# Avalon2.net
KiCad netlist of a schematic drawn in Altium Designer
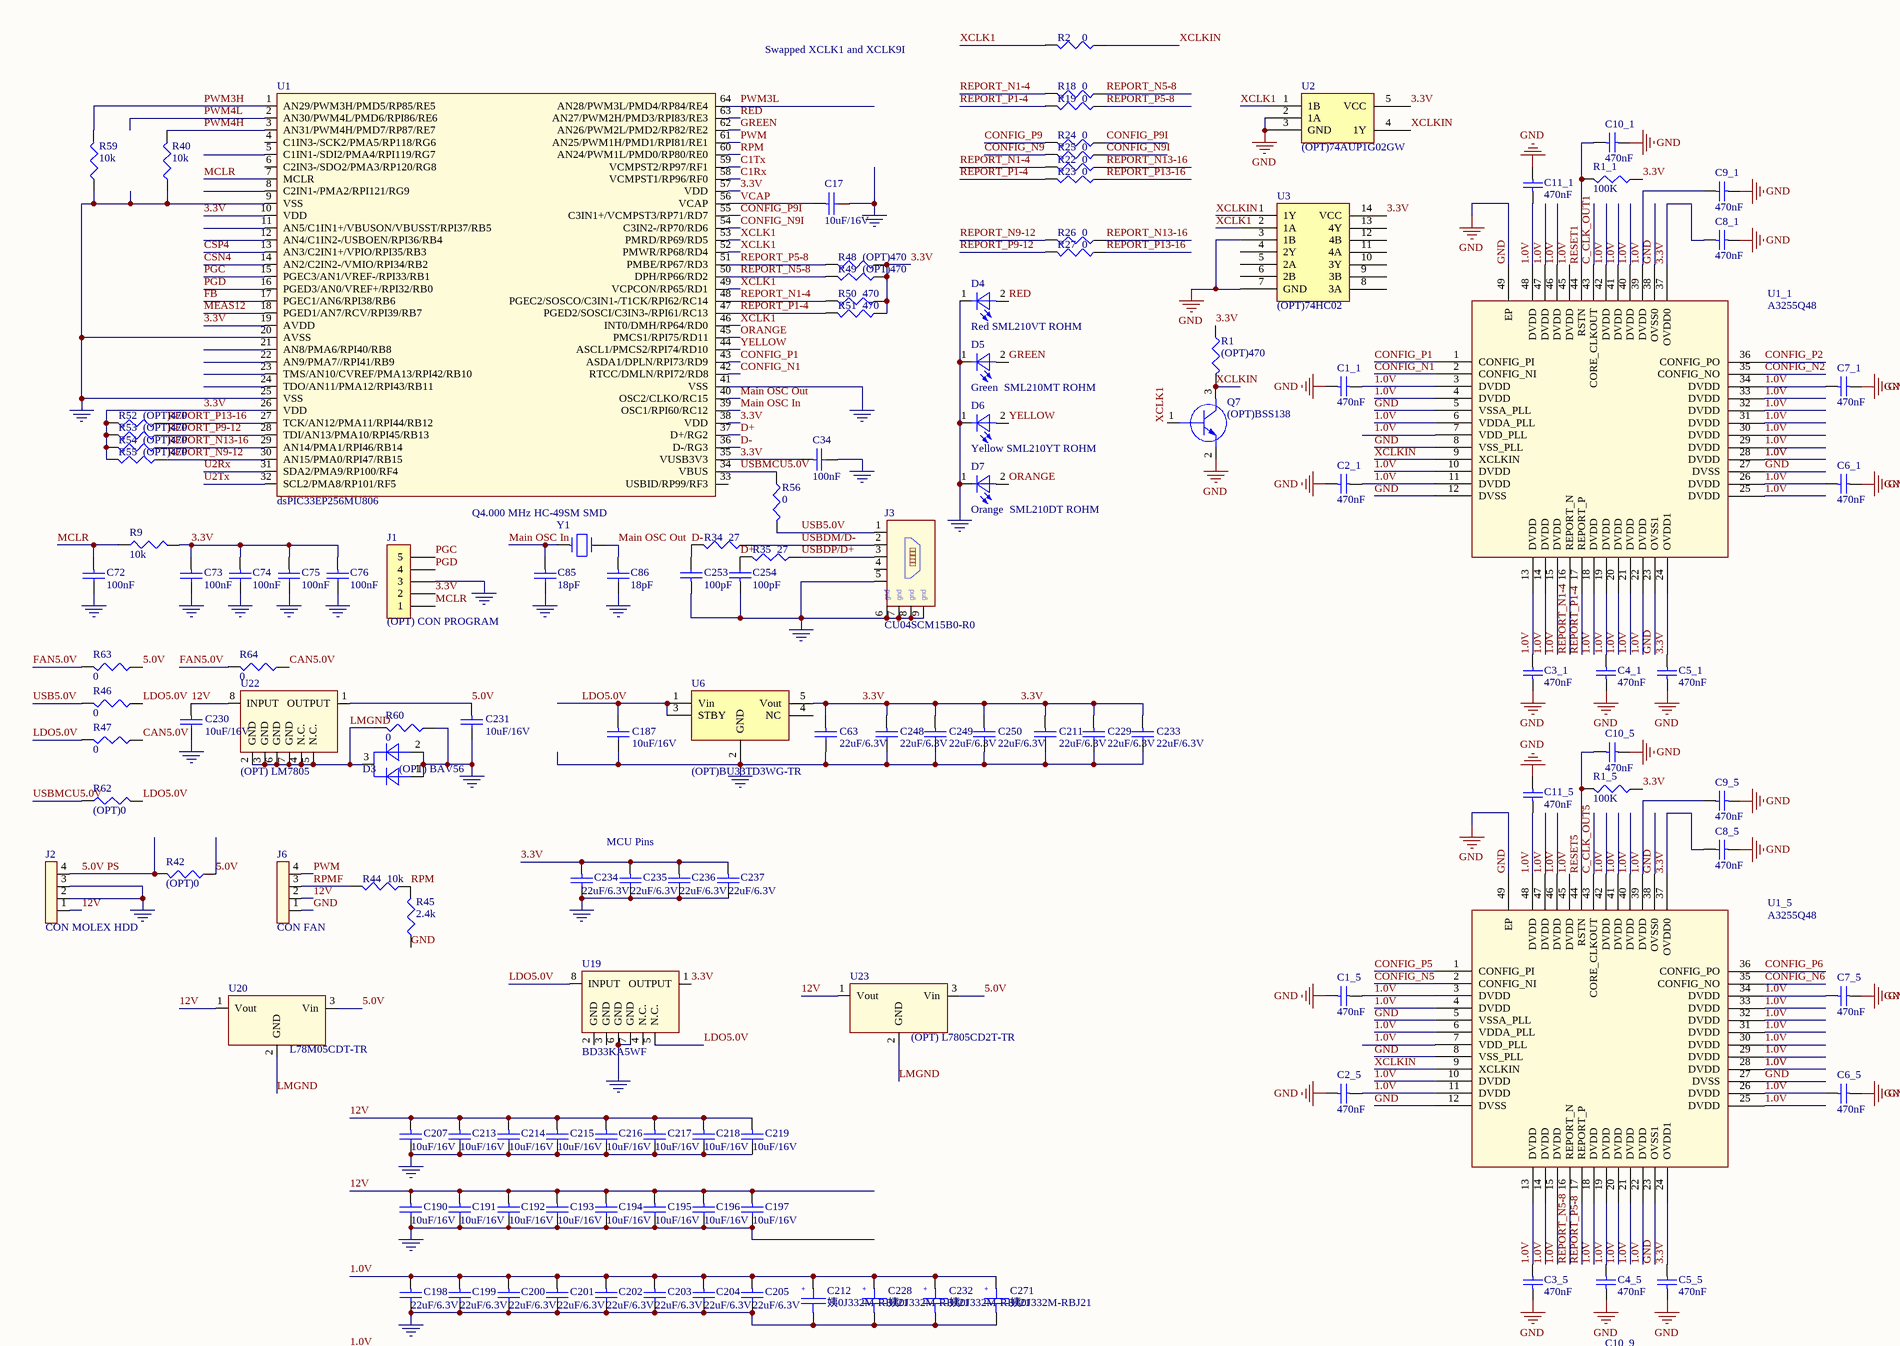
[diagram p0: Avalon2.SchDoc, top left]
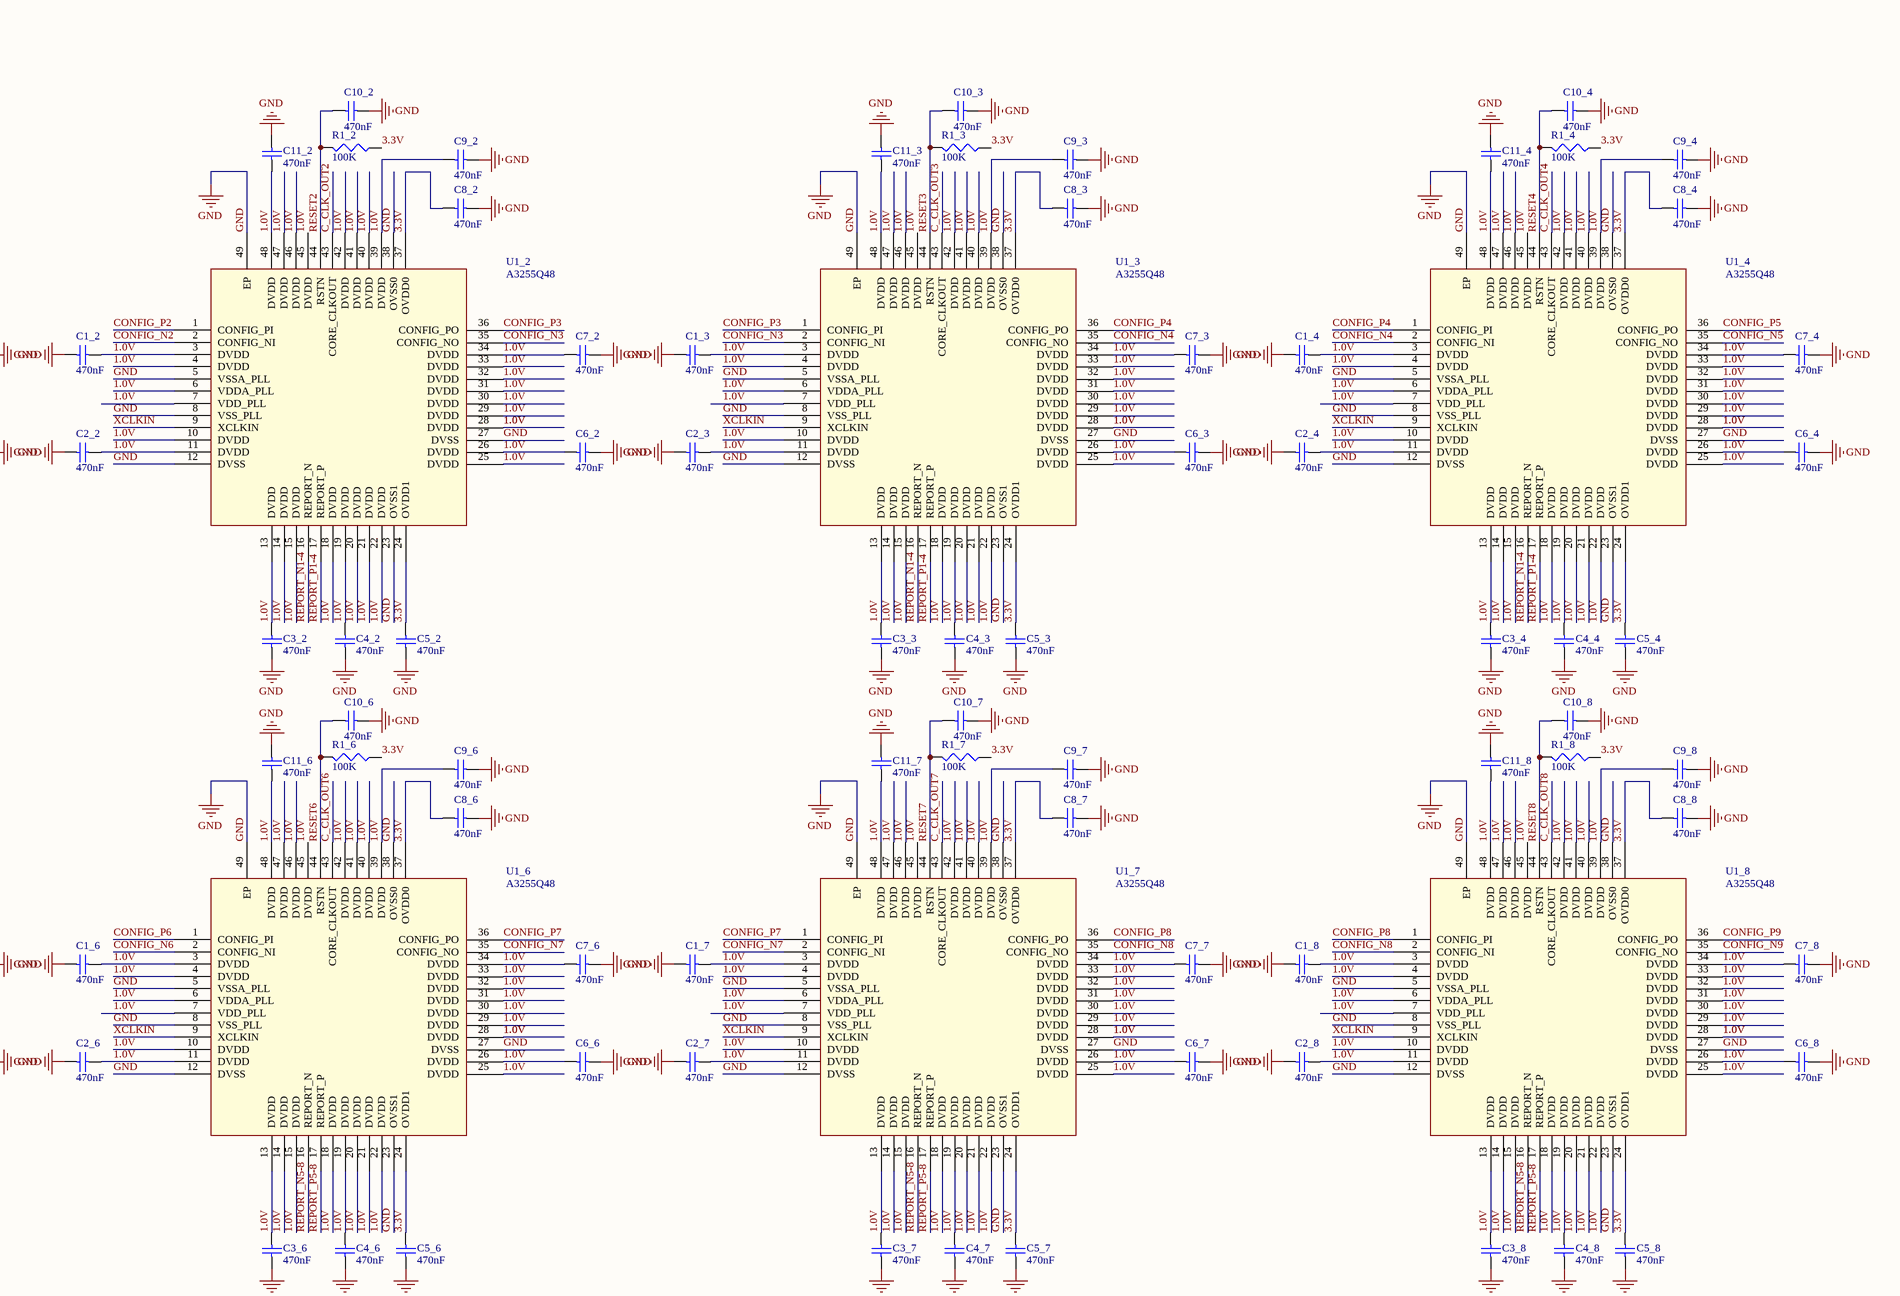
[diagram p1: Avalon2.SchDoc, top right]
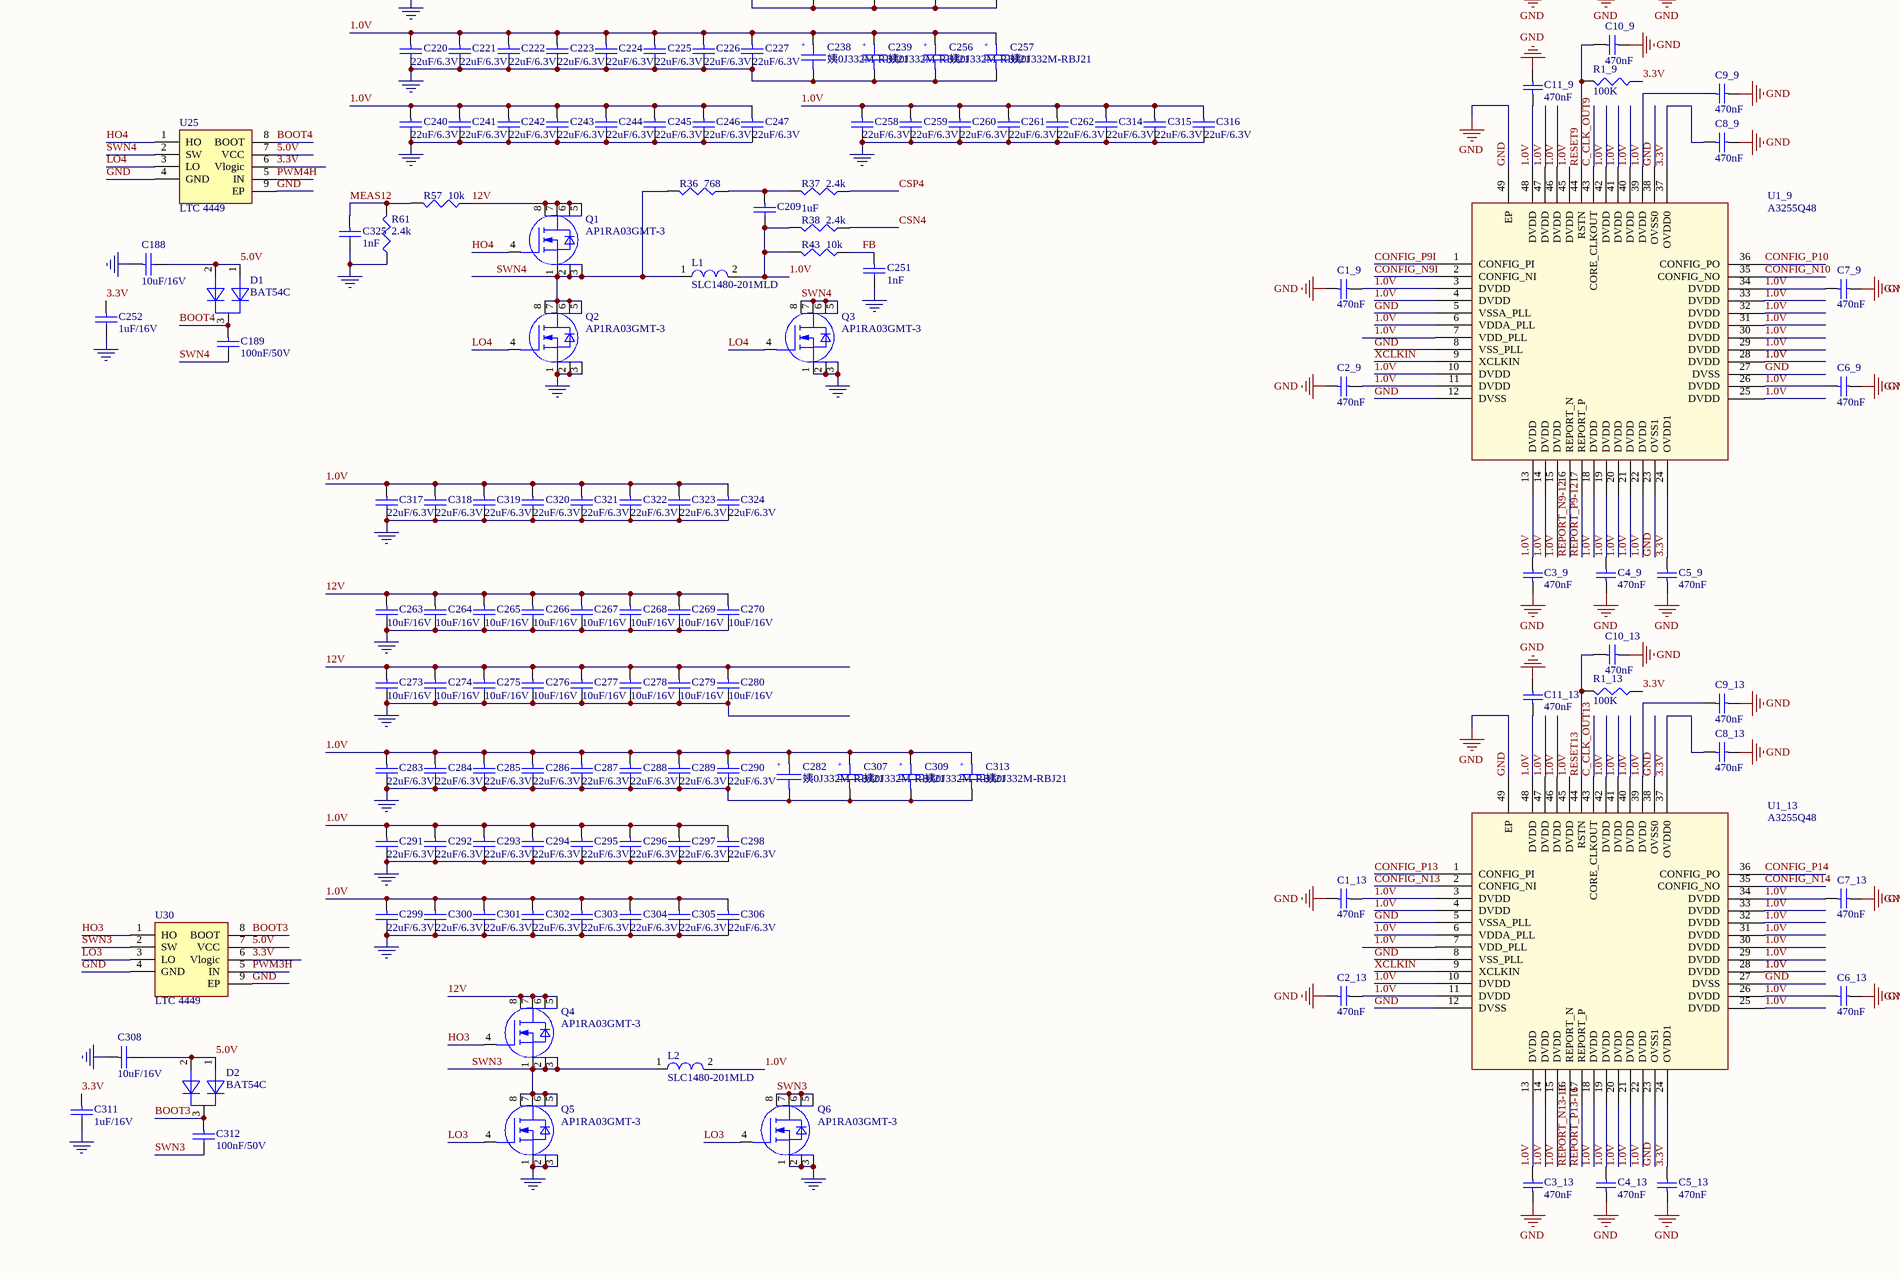
[diagram p2: Avalon2.SchDoc, bottom left]
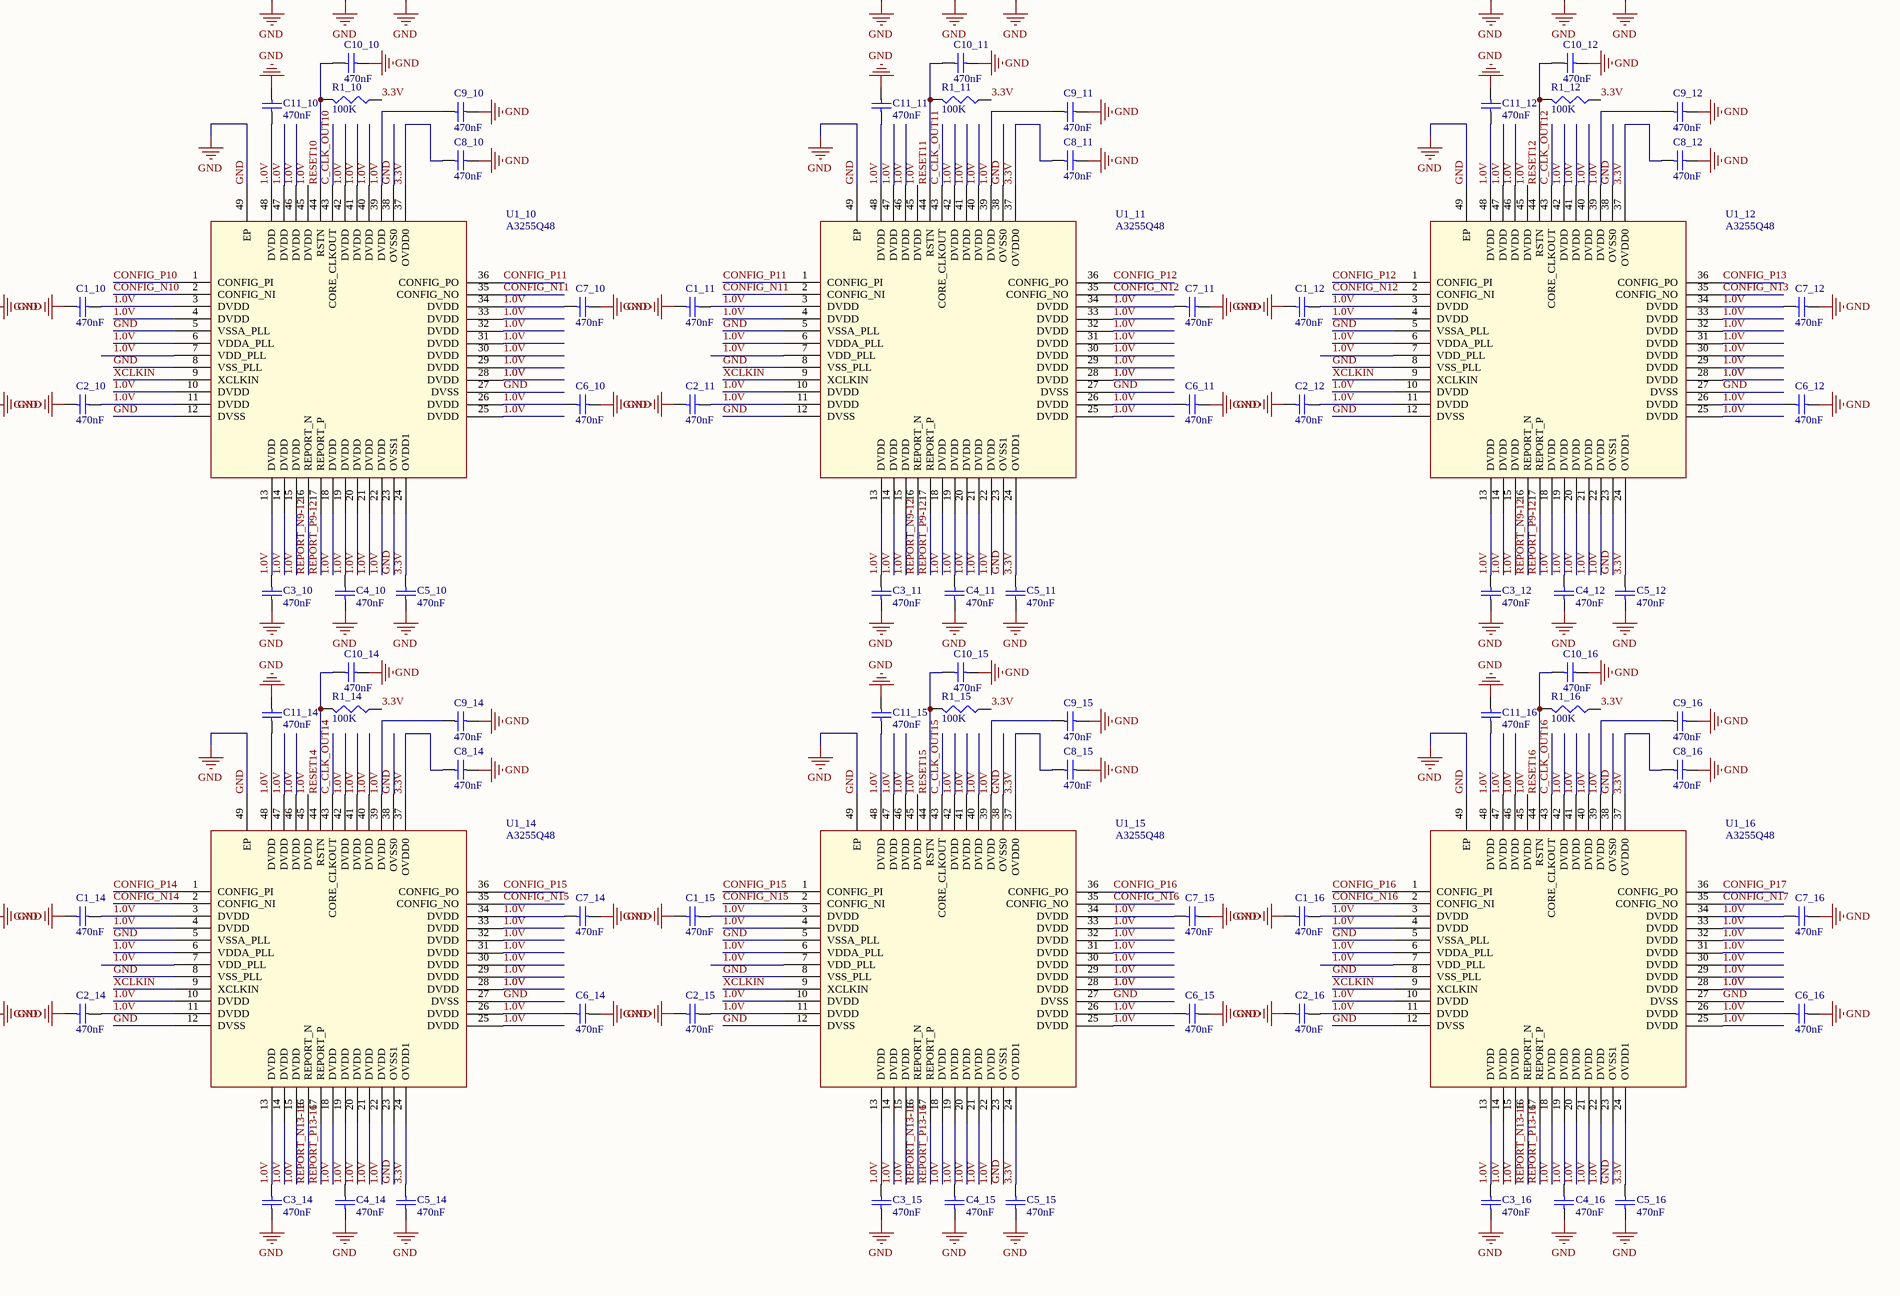
[diagram p3: Avalon2.SchDoc, bottom right]

(export (version "E")
  (design (tool "Eeschema 10.0.6"))
  (components
    (comp (ref "C1_1")
      (value "470nF")
      (footprint "SMD_0603_CAPC1608X80N")
      (description "Capacitor (Semiconductor SIM Model)")
      (fields (field (name "PUBLISHER") "Altium Limited"))
      (libsource (lib "Miscellaneous Devices") (part "Cap Semi"))
    )
    (comp (ref "C1_2")
      (value "470nF")
      (footprint "SMD_0603_CAPC1608X80N")
      (description "Capacitor (Semiconductor SIM Model)")
      (fields (field (name "PUBLISHER") "Altium Limited"))
      (libsource (lib "Miscellaneous Devices") (part "Cap Semi"))
    )
    (comp (ref "C1_3")
      (value "470nF")
      (footprint "SMD_0603_CAPC1608X80N")
      (description "Capacitor (Semiconductor SIM Model)")
      (fields (field (name "PUBLISHER") "Altium Limited"))
      (libsource (lib "Miscellaneous Devices") (part "Cap Semi"))
    )
    (comp (ref "C1_4")
      (value "470nF")
      (footprint "SMD_0603_CAPC1608X80N")
      (description "Capacitor (Semiconductor SIM Model)")
      (fields (field (name "PUBLISHER") "Altium Limited"))
      (libsource (lib "Miscellaneous Devices") (part "Cap Semi"))
    )
    (comp (ref "C1_5")
      (value "470nF")
      (footprint "SMD_0603_CAPC1608X80N")
      (description "Capacitor (Semiconductor SIM Model)")
      (fields (field (name "PUBLISHER") "Altium Limited"))
      (libsource (lib "Miscellaneous Devices") (part "Cap Semi"))
    )
    (comp (ref "C1_6")
      (value "470nF")
      (footprint "SMD_0603_CAPC1608X80N")
      (description "Capacitor (Semiconductor SIM Model)")
      (fields (field (name "PUBLISHER") "Altium Limited"))
      (libsource (lib "Miscellaneous Devices") (part "Cap Semi"))
    )
    (comp (ref "C1_7")
      (value "470nF")
      (footprint "SMD_0603_CAPC1608X80N")
      (description "Capacitor (Semiconductor SIM Model)")
      (fields (field (name "PUBLISHER") "Altium Limited"))
      (libsource (lib "Miscellaneous Devices") (part "Cap Semi"))
    )
    (comp (ref "C1_8")
      (value "470nF")
      (footprint "SMD_0603_CAPC1608X80N")
      (description "Capacitor (Semiconductor SIM Model)")
      (fields (field (name "PUBLISHER") "Altium Limited"))
      (libsource (lib "Miscellaneous Devices") (part "Cap Semi"))
    )
    (comp (ref "C1_9")
      (value "470nF")
      (footprint "SMD_0603_CAPC1608X80N")
      (description "Capacitor (Semiconductor SIM Model)")
      (fields (field (name "PUBLISHER") "Altium Limited"))
      (libsource (lib "Miscellaneous Devices") (part "Cap Semi"))
    )
    (comp (ref "C1_10")
      (value "470nF")
      (footprint "SMD_0603_CAPC1608X80N")
      (description "Capacitor (Semiconductor SIM Model)")
      (fields (field (name "PUBLISHER") "Altium Limited"))
      (libsource (lib "Miscellaneous Devices") (part "Cap Semi"))
    )
    (comp (ref "C1_11")
      (value "470nF")
      (footprint "SMD_0603_CAPC1608X80N")
      (description "Capacitor (Semiconductor SIM Model)")
      (fields (field (name "PUBLISHER") "Altium Limited"))
      (libsource (lib "Miscellaneous Devices") (part "Cap Semi"))
    )
    (comp (ref "C1_12")
      (value "470nF")
      (footprint "SMD_0603_CAPC1608X80N")
      (description "Capacitor (Semiconductor SIM Model)")
      (fields (field (name "PUBLISHER") "Altium Limited"))
      (libsource (lib "Miscellaneous Devices") (part "Cap Semi"))
    )
    (comp (ref "C1_13")
      (value "470nF")
      (footprint "SMD_0603_CAPC1608X80N")
      (description "Capacitor (Semiconductor SIM Model)")
      (fields (field (name "PUBLISHER") "Altium Limited"))
      (libsource (lib "Miscellaneous Devices") (part "Cap Semi"))
    )
    (comp (ref "C1_14")
      (value "470nF")
      (footprint "SMD_0603_CAPC1608X80N")
      (description "Capacitor (Semiconductor SIM Model)")
      (fields (field (name "PUBLISHER") "Altium Limited"))
      (libsource (lib "Miscellaneous Devices") (part "Cap Semi"))
    )
    (comp (ref "C1_15")
      (value "470nF")
      (footprint "SMD_0603_CAPC1608X80N")
      (description "Capacitor (Semiconductor SIM Model)")
      (fields (field (name "PUBLISHER") "Altium Limited"))
      (libsource (lib "Miscellaneous Devices") (part "Cap Semi"))
    )
    (comp (ref "C1_16")
      (value "470nF")
      (footprint "SMD_0603_CAPC1608X80N")
      (description "Capacitor (Semiconductor SIM Model)")
      (fields (field (name "PUBLISHER") "Altium Limited"))
      (libsource (lib "Miscellaneous Devices") (part "Cap Semi"))
    )
    (comp (ref "C2_1")
      (value "470nF")
      (footprint "SMD_0603_CAPC1608X80N")
      (description "Capacitor (Semiconductor SIM Model)")
      (fields (field (name "PUBLISHER") "Altium Limited"))
      (libsource (lib "Miscellaneous Devices") (part "Cap Semi"))
    )
    (comp (ref "C2_2")
      (value "470nF")
      (footprint "SMD_0603_CAPC1608X80N")
      (description "Capacitor (Semiconductor SIM Model)")
      (fields (field (name "PUBLISHER") "Altium Limited"))
      (libsource (lib "Miscellaneous Devices") (part "Cap Semi"))
    )
    (comp (ref "C2_3")
      (value "470nF")
      (footprint "SMD_0603_CAPC1608X80N")
      (description "Capacitor (Semiconductor SIM Model)")
      (fields (field (name "PUBLISHER") "Altium Limited"))
      (libsource (lib "Miscellaneous Devices") (part "Cap Semi"))
    )
    (comp (ref "C2_4")
      (value "470nF")
      (footprint "SMD_0603_CAPC1608X80N")
      (description "Capacitor (Semiconductor SIM Model)")
      (fields (field (name "PUBLISHER") "Altium Limited"))
      (libsource (lib "Miscellaneous Devices") (part "Cap Semi"))
    )
    (comp (ref "C2_5")
      (value "470nF")
      (footprint "SMD_0603_CAPC1608X80N")
      (description "Capacitor (Semiconductor SIM Model)")
      (fields (field (name "PUBLISHER") "Altium Limited"))
      (libsource (lib "Miscellaneous Devices") (part "Cap Semi"))
    )
    (comp (ref "C2_6")
      (value "470nF")
      (footprint "SMD_0603_CAPC1608X80N")
      (description "Capacitor (Semiconductor SIM Model)")
      (fields (field (name "PUBLISHER") "Altium Limited"))
      (libsource (lib "Miscellaneous Devices") (part "Cap Semi"))
    )
    (comp (ref "C2_7")
      (value "470nF")
      (footprint "SMD_0603_CAPC1608X80N")
      (description "Capacitor (Semiconductor SIM Model)")
      (fields (field (name "PUBLISHER") "Altium Limited"))
      (libsource (lib "Miscellaneous Devices") (part "Cap Semi"))
    )
    (comp (ref "C2_8")
      (value "470nF")
      (footprint "SMD_0603_CAPC1608X80N")
      (description "Capacitor (Semiconductor SIM Model)")
      (fields (field (name "PUBLISHER") "Altium Limited"))
      (libsource (lib "Miscellaneous Devices") (part "Cap Semi"))
    )
    (comp (ref "C2_9")
      (value "470nF")
      (footprint "SMD_0603_CAPC1608X80N")
      (description "Capacitor (Semiconductor SIM Model)")
      (fields (field (name "PUBLISHER") "Altium Limited"))
      (libsource (lib "Miscellaneous Devices") (part "Cap Semi"))
    )
    (comp (ref "C2_10")
      (value "470nF")
      (footprint "SMD_0603_CAPC1608X80N")
      (description "Capacitor (Semiconductor SIM Model)")
      (fields (field (name "PUBLISHER") "Altium Limited"))
      (libsource (lib "Miscellaneous Devices") (part "Cap Semi"))
    )
    (comp (ref "C2_11")
      (value "470nF")
      (footprint "SMD_0603_CAPC1608X80N")
      (description "Capacitor (Semiconductor SIM Model)")
      (fields (field (name "PUBLISHER") "Altium Limited"))
      (libsource (lib "Miscellaneous Devices") (part "Cap Semi"))
    )
    (comp (ref "C2_12")
      (value "470nF")
      (footprint "SMD_0603_CAPC1608X80N")
      (description "Capacitor (Semiconductor SIM Model)")
      (fields (field (name "PUBLISHER") "Altium Limited"))
      (libsource (lib "Miscellaneous Devices") (part "Cap Semi"))
    )
    (comp (ref "C2_13")
      (value "470nF")
      (footprint "SMD_0603_CAPC1608X80N")
      (description "Capacitor (Semiconductor SIM Model)")
      (fields (field (name "PUBLISHER") "Altium Limited"))
      (libsource (lib "Miscellaneous Devices") (part "Cap Semi"))
    )
    (comp (ref "C2_14")
      (value "470nF")
      (footprint "SMD_0603_CAPC1608X80N")
      (description "Capacitor (Semiconductor SIM Model)")
      (fields (field (name "PUBLISHER") "Altium Limited"))
      (libsource (lib "Miscellaneous Devices") (part "Cap Semi"))
    )
    (comp (ref "C2_15")
      (value "470nF")
      (footprint "SMD_0603_CAPC1608X80N")
      (description "Capacitor (Semiconductor SIM Model)")
      (fields (field (name "PUBLISHER") "Altium Limited"))
      (libsource (lib "Miscellaneous Devices") (part "Cap Semi"))
    )
    (comp (ref "C2_16")
      (value "470nF")
      (footprint "SMD_0603_CAPC1608X80N")
      (description "Capacitor (Semiconductor SIM Model)")
      (fields (field (name "PUBLISHER") "Altium Limited"))
      (libsource (lib "Miscellaneous Devices") (part "Cap Semi"))
    )
    (comp (ref "C3_1")
      (value "470nF")
      (footprint "SMD_0603_CAPC1608X80N")
      (description "Capacitor (Semiconductor SIM Model)")
      (fields (field (name "PUBLISHER") "Altium Limited"))
      (libsource (lib "Miscellaneous Devices") (part "Cap Semi"))
    )
    (comp (ref "C3_2")
      (value "470nF")
      (footprint "SMD_0603_CAPC1608X80N")
      (description "Capacitor (Semiconductor SIM Model)")
      (fields (field (name "PUBLISHER") "Altium Limited"))
      (libsource (lib "Miscellaneous Devices") (part "Cap Semi"))
    )
    (comp (ref "C3_3")
      (value "470nF")
      (footprint "SMD_0603_CAPC1608X80N")
      (description "Capacitor (Semiconductor SIM Model)")
      (fields (field (name "PUBLISHER") "Altium Limited"))
      (libsource (lib "Miscellaneous Devices") (part "Cap Semi"))
    )
    (comp (ref "C3_4")
      (value "470nF")
      (footprint "SMD_0603_CAPC1608X80N")
      (description "Capacitor (Semiconductor SIM Model)")
      (fields (field (name "PUBLISHER") "Altium Limited"))
      (libsource (lib "Miscellaneous Devices") (part "Cap Semi"))
    )
    (comp (ref "C3_5")
      (value "470nF")
      (footprint "SMD_0603_CAPC1608X80N")
      (description "Capacitor (Semiconductor SIM Model)")
      (fields (field (name "PUBLISHER") "Altium Limited"))
      (libsource (lib "Miscellaneous Devices") (part "Cap Semi"))
    )
    (comp (ref "C3_6")
      (value "470nF")
      (footprint "SMD_0603_CAPC1608X80N")
      (description "Capacitor (Semiconductor SIM Model)")
      (fields (field (name "PUBLISHER") "Altium Limited"))
      (libsource (lib "Miscellaneous Devices") (part "Cap Semi"))
    )
    (comp (ref "C3_7")
      (value "470nF")
      (footprint "SMD_0603_CAPC1608X80N")
      (description "Capacitor (Semiconductor SIM Model)")
      (fields (field (name "PUBLISHER") "Altium Limited"))
      (libsource (lib "Miscellaneous Devices") (part "Cap Semi"))
    )
    (comp (ref "C3_8")
      (value "470nF")
      (footprint "SMD_0603_CAPC1608X80N")
      (description "Capacitor (Semiconductor SIM Model)")
      (fields (field (name "PUBLISHER") "Altium Limited"))
      (libsource (lib "Miscellaneous Devices") (part "Cap Semi"))
    )
    (comp (ref "C3_9")
      (value "470nF")
      (footprint "SMD_0603_CAPC1608X80N")
      (description "Capacitor (Semiconductor SIM Model)")
      (fields (field (name "PUBLISHER") "Altium Limited"))
      (libsource (lib "Miscellaneous Devices") (part "Cap Semi"))
    )
    (comp (ref "C3_10")
      (value "470nF")
      (footprint "SMD_0603_CAPC1608X80N")
      (description "Capacitor (Semiconductor SIM Model)")
      (fields (field (name "PUBLISHER") "Altium Limited"))
      (libsource (lib "Miscellaneous Devices") (part "Cap Semi"))
    )
    (comp (ref "C3_11")
      (value "470nF")
      (footprint "SMD_0603_CAPC1608X80N")
      (description "Capacitor (Semiconductor SIM Model)")
      (fields (field (name "PUBLISHER") "Altium Limited"))
      (libsource (lib "Miscellaneous Devices") (part "Cap Semi"))
    )
    (comp (ref "C3_12")
      (value "470nF")
      (footprint "SMD_0603_CAPC1608X80N")
      (description "Capacitor (Semiconductor SIM Model)")
      (fields (field (name "PUBLISHER") "Altium Limited"))
      (libsource (lib "Miscellaneous Devices") (part "Cap Semi"))
    )
    (comp (ref "C3_13")
      (value "470nF")
      (footprint "SMD_0603_CAPC1608X80N")
      (description "Capacitor (Semiconductor SIM Model)")
      (fields (field (name "PUBLISHER") "Altium Limited"))
      (libsource (lib "Miscellaneous Devices") (part "Cap Semi"))
    )
    (comp (ref "C3_14")
      (value "470nF")
      (footprint "SMD_0603_CAPC1608X80N")
      (description "Capacitor (Semiconductor SIM Model)")
      (fields (field (name "PUBLISHER") "Altium Limited"))
      (libsource (lib "Miscellaneous Devices") (part "Cap Semi"))
    )
    (comp (ref "C3_15")
      (value "470nF")
      (footprint "SMD_0603_CAPC1608X80N")
      (description "Capacitor (Semiconductor SIM Model)")
      (fields (field (name "PUBLISHER") "Altium Limited"))
      (libsource (lib "Miscellaneous Devices") (part "Cap Semi"))
    )
    (comp (ref "C3_16")
      (value "470nF")
      (footprint "SMD_0603_CAPC1608X80N")
      (description "Capacitor (Semiconductor SIM Model)")
      (fields (field (name "PUBLISHER") "Altium Limited"))
      (libsource (lib "Miscellaneous Devices") (part "Cap Semi"))
    )
    (comp (ref "C4_1")
      (value "470nF")
      (footprint "SMD_0603_CAPC1608X80N")
      (description "Capacitor (Semiconductor SIM Model)")
      (fields (field (name "PUBLISHER") "Altium Limited"))
      (libsource (lib "Miscellaneous Devices") (part "Cap Semi"))
    )
    (comp (ref "C4_2")
      (value "470nF")
      (footprint "SMD_0603_CAPC1608X80N")
      (description "Capacitor (Semiconductor SIM Model)")
      (fields (field (name "PUBLISHER") "Altium Limited"))
      (libsource (lib "Miscellaneous Devices") (part "Cap Semi"))
    )
    (comp (ref "C4_3")
      (value "470nF")
      (footprint "SMD_0603_CAPC1608X80N")
      (description "Capacitor (Semiconductor SIM Model)")
      (fields (field (name "PUBLISHER") "Altium Limited"))
      (libsource (lib "Miscellaneous Devices") (part "Cap Semi"))
    )
    (comp (ref "C4_4")
      (value "470nF")
      (footprint "SMD_0603_CAPC1608X80N")
      (description "Capacitor (Semiconductor SIM Model)")
      (fields (field (name "PUBLISHER") "Altium Limited"))
      (libsource (lib "Miscellaneous Devices") (part "Cap Semi"))
    )
    (comp (ref "C4_5")
      (value "470nF")
      (footprint "SMD_0603_CAPC1608X80N")
      (description "Capacitor (Semiconductor SIM Model)")
      (fields (field (name "PUBLISHER") "Altium Limited"))
      (libsource (lib "Miscellaneous Devices") (part "Cap Semi"))
    )
    (comp (ref "C4_6")
      (value "470nF")
      (footprint "SMD_0603_CAPC1608X80N")
      (description "Capacitor (Semiconductor SIM Model)")
      (fields (field (name "PUBLISHER") "Altium Limited"))
      (libsource (lib "Miscellaneous Devices") (part "Cap Semi"))
    )
    (comp (ref "C4_7")
      (value "470nF")
      (footprint "SMD_0603_CAPC1608X80N")
      (description "Capacitor (Semiconductor SIM Model)")
      (fields (field (name "PUBLISHER") "Altium Limited"))
      (libsource (lib "Miscellaneous Devices") (part "Cap Semi"))
    )
    (comp (ref "C4_8")
      (value "470nF")
      (footprint "SMD_0603_CAPC1608X80N")
      (description "Capacitor (Semiconductor SIM Model)")
      (fields (field (name "PUBLISHER") "Altium Limited"))
      (libsource (lib "Miscellaneous Devices") (part "Cap Semi"))
    )
    (comp (ref "C4_9")
      (value "470nF")
      (footprint "SMD_0603_CAPC1608X80N")
      (description "Capacitor (Semiconductor SIM Model)")
      (fields (field (name "PUBLISHER") "Altium Limited"))
      (libsource (lib "Miscellaneous Devices") (part "Cap Semi"))
    )
    (comp (ref "C4_10")
      (value "470nF")
      (footprint "SMD_0603_CAPC1608X80N")
      (description "Capacitor (Semiconductor SIM Model)")
      (fields (field (name "PUBLISHER") "Altium Limited"))
      (libsource (lib "Miscellaneous Devices") (part "Cap Semi"))
    )
    (comp (ref "C4_11")
      (value "470nF")
      (footprint "SMD_0603_CAPC1608X80N")
      (description "Capacitor (Semiconductor SIM Model)")
      (fields (field (name "PUBLISHER") "Altium Limited"))
      (libsource (lib "Miscellaneous Devices") (part "Cap Semi"))
    )
    (comp (ref "C4_12")
      (value "470nF")
      (footprint "SMD_0603_CAPC1608X80N")
      (description "Capacitor (Semiconductor SIM Model)")
      (fields (field (name "PUBLISHER") "Altium Limited"))
      (libsource (lib "Miscellaneous Devices") (part "Cap Semi"))
    )
    (comp (ref "C4_13")
      (value "470nF")
      (footprint "SMD_0603_CAPC1608X80N")
      (description "Capacitor (Semiconductor SIM Model)")
      (fields (field (name "PUBLISHER") "Altium Limited"))
      (libsource (lib "Miscellaneous Devices") (part "Cap Semi"))
    )
    (comp (ref "C4_14")
      (value "470nF")
      (footprint "SMD_0603_CAPC1608X80N")
      (description "Capacitor (Semiconductor SIM Model)")
      (fields (field (name "PUBLISHER") "Altium Limited"))
      (libsource (lib "Miscellaneous Devices") (part "Cap Semi"))
    )
    (comp (ref "C4_15")
      (value "470nF")
      (footprint "SMD_0603_CAPC1608X80N")
      (description "Capacitor (Semiconductor SIM Model)")
      (fields (field (name "PUBLISHER") "Altium Limited"))
      (libsource (lib "Miscellaneous Devices") (part "Cap Semi"))
    )
    (comp (ref "C4_16")
      (value "470nF")
      (footprint "SMD_0603_CAPC1608X80N")
      (description "Capacitor (Semiconductor SIM Model)")
      (fields (field (name "PUBLISHER") "Altium Limited"))
      (libsource (lib "Miscellaneous Devices") (part "Cap Semi"))
    )
    (comp (ref "C5_1")
      (value "470nF")
      (footprint "SMD_0603_CAPC1608X80N")
      (description "Capacitor (Semiconductor SIM Model)")
      (fields (field (name "PUBLISHER") "Altium Limited"))
      (libsource (lib "Miscellaneous Devices") (part "Cap Semi"))
    )
    (comp (ref "C5_2")
      (value "470nF")
      (footprint "SMD_0603_CAPC1608X80N")
      (description "Capacitor (Semiconductor SIM Model)")
      (fields (field (name "PUBLISHER") "Altium Limited"))
      (libsource (lib "Miscellaneous Devices") (part "Cap Semi"))
    )
    (comp (ref "C5_3")
      (value "470nF")
      (footprint "SMD_0603_CAPC1608X80N")
      (description "Capacitor (Semiconductor SIM Model)")
      (fields (field (name "PUBLISHER") "Altium Limited"))
      (libsource (lib "Miscellaneous Devices") (part "Cap Semi"))
    )
    (comp (ref "C5_4")
      (value "470nF")
      (footprint "SMD_0603_CAPC1608X80N")
      (description "Capacitor (Semiconductor SIM Model)")
      (fields (field (name "PUBLISHER") "Altium Limited"))
      (libsource (lib "Miscellaneous Devices") (part "Cap Semi"))
    )
    (comp (ref "C5_5")
      (value "470nF")
      (footprint "SMD_0603_CAPC1608X80N")
      (description "Capacitor (Semiconductor SIM Model)")
      (fields (field (name "PUBLISHER") "Altium Limited"))
      (libsource (lib "Miscellaneous Devices") (part "Cap Semi"))
    )
    (comp (ref "C5_6")
      (value "470nF")
      (footprint "SMD_0603_CAPC1608X80N")
      (description "Capacitor (Semiconductor SIM Model)")
      (fields (field (name "PUBLISHER") "Altium Limited"))
      (libsource (lib "Miscellaneous Devices") (part "Cap Semi"))
    )
    (comp (ref "C5_7")
      (value "470nF")
      (footprint "SMD_0603_CAPC1608X80N")
      (description "Capacitor (Semiconductor SIM Model)")
      (fields (field (name "PUBLISHER") "Altium Limited"))
      (libsource (lib "Miscellaneous Devices") (part "Cap Semi"))
    )
    (comp (ref "C5_8")
      (value "470nF")
      (footprint "SMD_0603_CAPC1608X80N")
      (description "Capacitor (Semiconductor SIM Model)")
      (fields (field (name "PUBLISHER") "Altium Limited"))
      (libsource (lib "Miscellaneous Devices") (part "Cap Semi"))
    )
    (comp (ref "C5_9")
      (value "470nF")
      (footprint "SMD_0603_CAPC1608X80N")
      (description "Capacitor (Semiconductor SIM Model)")
      (fields (field (name "PUBLISHER") "Altium Limited"))
      (libsource (lib "Miscellaneous Devices") (part "Cap Semi"))
    )
    (comp (ref "C5_10")
      (value "470nF")
      (footprint "SMD_0603_CAPC1608X80N")
      (description "Capacitor (Semiconductor SIM Model)")
      (fields (field (name "PUBLISHER") "Altium Limited"))
      (libsource (lib "Miscellaneous Devices") (part "Cap Semi"))
    )
    (comp (ref "C5_11")
      (value "470nF")
      (footprint "SMD_0603_CAPC1608X80N")
      (description "Capacitor (Semiconductor SIM Model)")
      (fields (field (name "PUBLISHER") "Altium Limited"))
      (libsource (lib "Miscellaneous Devices") (part "Cap Semi"))
    )
    (comp (ref "C5_12")
      (value "470nF")
      (footprint "SMD_0603_CAPC1608X80N")
      (description "Capacitor (Semiconductor SIM Model)")
      (fields (field (name "PUBLISHER") "Altium Limited"))
      (libsource (lib "Miscellaneous Devices") (part "Cap Semi"))
    )
    (comp (ref "C5_13")
      (value "470nF")
      (footprint "SMD_0603_CAPC1608X80N")
      (description "Capacitor (Semiconductor SIM Model)")
      (fields (field (name "PUBLISHER") "Altium Limited"))
      (libsource (lib "Miscellaneous Devices") (part "Cap Semi"))
    )
    (comp (ref "C5_14")
      (value "470nF")
      (footprint "SMD_0603_CAPC1608X80N")
      (description "Capacitor (Semiconductor SIM Model)")
      (fields (field (name "PUBLISHER") "Altium Limited"))
      (libsource (lib "Miscellaneous Devices") (part "Cap Semi"))
    )
    (comp (ref "C5_15")
      (value "470nF")
      (footprint "SMD_0603_CAPC1608X80N")
      (description "Capacitor (Semiconductor SIM Model)")
      (fields (field (name "PUBLISHER") "Altium Limited"))
      (libsource (lib "Miscellaneous Devices") (part "Cap Semi"))
    )
    (comp (ref "C5_16")
      (value "470nF")
      (footprint "SMD_0603_CAPC1608X80N")
      (description "Capacitor (Semiconductor SIM Model)")
      (fields (field (name "PUBLISHER") "Altium Limited"))
      (libsource (lib "Miscellaneous Devices") (part "Cap Semi"))
    )
    (comp (ref "C6_1")
      (value "470nF")
      (footprint "SMD_0603_CAPC1608X80N")
      (description "Capacitor (Semiconductor SIM Model)")
      (fields (field (name "PUBLISHER") "Altium Limited"))
      (libsource (lib "Miscellaneous Devices") (part "Cap Semi"))
    )
    (comp (ref "C6_2")
      (value "470nF")
      (footprint "SMD_0603_CAPC1608X80N")
      (description "Capacitor (Semiconductor SIM Model)")
      (fields (field (name "PUBLISHER") "Altium Limited"))
      (libsource (lib "Miscellaneous Devices") (part "Cap Semi"))
    )
    (comp (ref "C6_3")
      (value "470nF")
      (footprint "SMD_0603_CAPC1608X80N")
      (description "Capacitor (Semiconductor SIM Model)")
      (fields (field (name "PUBLISHER") "Altium Limited"))
      (libsource (lib "Miscellaneous Devices") (part "Cap Semi"))
    )
    (comp (ref "C6_4")
      (value "470nF")
      (footprint "SMD_0603_CAPC1608X80N")
      (description "Capacitor (Semiconductor SIM Model)")
      (fields (field (name "PUBLISHER") "Altium Limited"))
      (libsource (lib "Miscellaneous Devices") (part "Cap Semi"))
    )
    (comp (ref "C6_5")
      (value "470nF")
      (footprint "SMD_0603_CAPC1608X80N")
      (description "Capacitor (Semiconductor SIM Model)")
      (fields (field (name "PUBLISHER") "Altium Limited"))
      (libsource (lib "Miscellaneous Devices") (part "Cap Semi"))
    )
    (comp (ref "C6_6")
      (value "470nF")
      (footprint "SMD_0603_CAPC1608X80N")
      (description "Capacitor (Semiconductor SIM Model)")
      (fields (field (name "PUBLISHER") "Altium Limited"))
      (libsource (lib "Miscellaneous Devices") (part "Cap Semi"))
    )
    (comp (ref "C6_7")
      (value "470nF")
      (footprint "SMD_0603_CAPC1608X80N")
      (description "Capacitor (Semiconductor SIM Model)")
      (fields (field (name "PUBLISHER") "Altium Limited"))
      (libsource (lib "Miscellaneous Devices") (part "Cap Semi"))
    )
    (comp (ref "C6_8")
      (value "470nF")
      (footprint "SMD_0603_CAPC1608X80N")
      (description "Capacitor (Semiconductor SIM Model)")
      (fields (field (name "PUBLISHER") "Altium Limited"))
      (libsource (lib "Miscellaneous Devices") (part "Cap Semi"))
    )
    (comp (ref "C6_9")
      (value "470nF")
      (footprint "SMD_0603_CAPC1608X80N")
      (description "Capacitor (Semiconductor SIM Model)")
      (fields (field (name "PUBLISHER") "Altium Limited"))
      (libsource (lib "Miscellaneous Devices") (part "Cap Semi"))
    )
    (comp (ref "C6_10")
      (value "470nF")
      (footprint "SMD_0603_CAPC1608X80N")
      (description "Capacitor (Semiconductor SIM Model)")
      (fields (field (name "PUBLISHER") "Altium Limited"))
      (libsource (lib "Miscellaneous Devices") (part "Cap Semi"))
    )
    (comp (ref "C6_11")
      (value "470nF")
      (footprint "SMD_0603_CAPC1608X80N")
      (description "Capacitor (Semiconductor SIM Model)")
      (fields (field (name "PUBLISHER") "Altium Limited"))
      (libsource (lib "Miscellaneous Devices") (part "Cap Semi"))
    )
    (comp (ref "C6_12")
      (value "470nF")
      (footprint "SMD_0603_CAPC1608X80N")
      (description "Capacitor (Semiconductor SIM Model)")
      (fields (field (name "PUBLISHER") "Altium Limited"))
      (libsource (lib "Miscellaneous Devices") (part "Cap Semi"))
    )
    (comp (ref "C6_13")
      (value "470nF")
      (footprint "SMD_0603_CAPC1608X80N")
      (description "Capacitor (Semiconductor SIM Model)")
      (fields (field (name "PUBLISHER") "Altium Limited"))
      (libsource (lib "Miscellaneous Devices") (part "Cap Semi"))
    )
    (comp (ref "C6_14")
      (value "470nF")
      (footprint "SMD_0603_CAPC1608X80N")
      (description "Capacitor (Semiconductor SIM Model)")
      (fields (field (name "PUBLISHER") "Altium Limited"))
      (libsource (lib "Miscellaneous Devices") (part "Cap Semi"))
    )
    (comp (ref "C6_15")
      (value "470nF")
      (footprint "SMD_0603_CAPC1608X80N")
      (description "Capacitor (Semiconductor SIM Model)")
      (fields (field (name "PUBLISHER") "Altium Limited"))
      (libsource (lib "Miscellaneous Devices") (part "Cap Semi"))
    )
    (comp (ref "C6_16")
      (value "470nF")
      (footprint "SMD_0603_CAPC1608X80N")
      (description "Capacitor (Semiconductor SIM Model)")
      (fields (field (name "PUBLISHER") "Altium Limited"))
      (libsource (lib "Miscellaneous Devices") (part "Cap Semi"))
    )
    (comp (ref "C7_1")
      (value "470nF")
      (footprint "SMD_0603_CAPC1608X80N")
      (description "Capacitor (Semiconductor SIM Model)")
      (fields (field (name "PUBLISHER") "Altium Limited"))
      (libsource (lib "Miscellaneous Devices") (part "Cap Semi"))
    )
    (comp (ref "C7_2")
      (value "470nF")
      (footprint "SMD_0603_CAPC1608X80N")
      (description "Capacitor (Semiconductor SIM Model)")
      (fields (field (name "PUBLISHER") "Altium Limited"))
      (libsource (lib "Miscellaneous Devices") (part "Cap Semi"))
    )
    (comp (ref "C7_3")
      (value "470nF")
      (footprint "SMD_0603_CAPC1608X80N")
      (description "Capacitor (Semiconductor SIM Model)")
      (fields (field (name "PUBLISHER") "Altium Limited"))
      (libsource (lib "Miscellaneous Devices") (part "Cap Semi"))
    )
    (comp (ref "C7_4")
      (value "470nF")
      (footprint "SMD_0603_CAPC1608X80N")
      (description "Capacitor (Semiconductor SIM Model)")
      (fields (field (name "PUBLISHER") "Altium Limited"))
      (libsource (lib "Miscellaneous Devices") (part "Cap Semi"))
    )
    (comp (ref "C7_5")
      (value "470nF")
      (footprint "SMD_0603_CAPC1608X80N")
      (description "Capacitor (Semiconductor SIM Model)")
      (fields (field (name "PUBLISHER") "Altium Limited"))
      (libsource (lib "Miscellaneous Devices") (part "Cap Semi"))
    )
    (comp (ref "C7_6")
      (value "470nF")
      (footprint "SMD_0603_CAPC1608X80N")
      (description "Capacitor (Semiconductor SIM Model)")
      (fields (field (name "PUBLISHER") "Altium Limited"))
      (libsource (lib "Miscellaneous Devices") (part "Cap Semi"))
    )
    (comp (ref "C7_7")
      (value "470nF")
      (footprint "SMD_0603_CAPC1608X80N")
      (description "Capacitor (Semiconductor SIM Model)")
      (fields (field (name "PUBLISHER") "Altium Limited"))
      (libsource (lib "Miscellaneous Devices") (part "Cap Semi"))
    )
    (comp (ref "C7_8")
      (value "470nF")
      (footprint "SMD_0603_CAPC1608X80N")
      (description "Capacitor (Semiconductor SIM Model)")
      (fields (field (name "PUBLISHER") "Altium Limited"))
      (libsource (lib "Miscellaneous Devices") (part "Cap Semi"))
    )
    (comp (ref "C7_9")
      (value "470nF")
      (footprint "SMD_0603_CAPC1608X80N")
      (description "Capacitor (Semiconductor SIM Model)")
      (fields (field (name "PUBLISHER") "Altium Limited"))
      (libsource (lib "Miscellaneous Devices") (part "Cap Semi"))
    )
    (comp (ref "C7_10")
      (value "470nF")
      (footprint "SMD_0603_CAPC1608X80N")
      (description "Capacitor (Semiconductor SIM Model)")
      (fields (field (name "PUBLISHER") "Altium Limited"))
      (libsource (lib "Miscellaneous Devices") (part "Cap Semi"))
    )
    (comp (ref "C7_11")
      (value "470nF")
      (footprint "SMD_0603_CAPC1608X80N")
      (description "Capacitor (Semiconductor SIM Model)")
      (fields (field (name "PUBLISHER") "Altium Limited"))
      (libsource (lib "Miscellaneous Devices") (part "Cap Semi"))
    )
    (comp (ref "C7_12")
      (value "470nF")
      (footprint "SMD_0603_CAPC1608X80N")
      (description "Capacitor (Semiconductor SIM Model)")
      (fields (field (name "PUBLISHER") "Altium Limited"))
      (libsource (lib "Miscellaneous Devices") (part "Cap Semi"))
    )
    (comp (ref "C7_13")
      (value "470nF")
      (footprint "SMD_0603_CAPC1608X80N")
      (description "Capacitor (Semiconductor SIM Model)")
      (fields (field (name "PUBLISHER") "Altium Limited"))
      (libsource (lib "Miscellaneous Devices") (part "Cap Semi"))
    )
    (comp (ref "C7_14")
      (value "470nF")
      (footprint "SMD_0603_CAPC1608X80N")
      (description "Capacitor (Semiconductor SIM Model)")
      (fields (field (name "PUBLISHER") "Altium Limited"))
      (libsource (lib "Miscellaneous Devices") (part "Cap Semi"))
    )
    (comp (ref "C7_15")
      (value "470nF")
      (footprint "SMD_0603_CAPC1608X80N")
      (description "Capacitor (Semiconductor SIM Model)")
      (fields (field (name "PUBLISHER") "Altium Limited"))
      (libsource (lib "Miscellaneous Devices") (part "Cap Semi"))
    )
    (comp (ref "C7_16")
      (value "470nF")
      (footprint "SMD_0603_CAPC1608X80N")
      (description "Capacitor (Semiconductor SIM Model)")
      (fields (field (name "PUBLISHER") "Altium Limited"))
      (libsource (lib "Miscellaneous Devices") (part "Cap Semi"))
    )
    (comp (ref "C8_1")
      (value "470nF")
      (footprint "SMD_0603_CAPC1608X80N")
      (description "Capacitor (Semiconductor SIM Model)")
      (fields (field (name "PUBLISHER") "Altium Limited"))
      (libsource (lib "Miscellaneous Devices") (part "Cap Semi"))
    )
    (comp (ref "C8_2")
      (value "470nF")
      (footprint "SMD_0603_CAPC1608X80N")
      (description "Capacitor (Semiconductor SIM Model)")
      (fields (field (name "PUBLISHER") "Altium Limited"))
      (libsource (lib "Miscellaneous Devices") (part "Cap Semi"))
    )
    (comp (ref "C8_3")
      (value "470nF")
      (footprint "SMD_0603_CAPC1608X80N")
      (description "Capacitor (Semiconductor SIM Model)")
      (fields (field (name "PUBLISHER") "Altium Limited"))
      (libsource (lib "Miscellaneous Devices") (part "Cap Semi"))
    )
    (comp (ref "C8_4")
      (value "470nF")
      (footprint "SMD_0603_CAPC1608X80N")
      (description "Capacitor (Semiconductor SIM Model)")
      (fields (field (name "PUBLISHER") "Altium Limited"))
      (libsource (lib "Miscellaneous Devices") (part "Cap Semi"))
    )
    (comp (ref "C8_5")
      (value "470nF")
      (footprint "SMD_0603_CAPC1608X80N")
      (description "Capacitor (Semiconductor SIM Model)")
      (fields (field (name "PUBLISHER") "Altium Limited"))
      (libsource (lib "Miscellaneous Devices") (part "Cap Semi"))
    )
    (comp (ref "C8_6")
      (value "470nF")
      (footprint "SMD_0603_CAPC1608X80N")
      (description "Capacitor (Semiconductor SIM Model)")
      (fields (field (name "PUBLISHER") "Altium Limited"))
      (libsource (lib "Miscellaneous Devices") (part "Cap Semi"))
    )
    (comp (ref "C8_7")
      (value "470nF")
      (footprint "SMD_0603_CAPC1608X80N")
      (description "Capacitor (Semiconductor SIM Model)")
      (fields (field (name "PUBLISHER") "Altium Limited"))
      (libsource (lib "Miscellaneous Devices") (part "Cap Semi"))
    )
    (comp (ref "C8_8")
      (value "470nF")
      (footprint "SMD_0603_CAPC1608X80N")
      (description "Capacitor (Semiconductor SIM Model)")
      (fields (field (name "PUBLISHER") "Altium Limited"))
      (libsource (lib "Miscellaneous Devices") (part "Cap Semi"))
    )
    (comp (ref "C8_9")
      (value "470nF")
      (footprint "SMD_0603_CAPC1608X80N")
      (description "Capacitor (Semiconductor SIM Model)")
      (fields (field (name "PUBLISHER") "Altium Limited"))
      (libsource (lib "Miscellaneous Devices") (part "Cap Semi"))
    )
    (comp (ref "C8_10")
      (value "470nF")
      (footprint "SMD_0603_CAPC1608X80N")
      (description "Capacitor (Semiconductor SIM Model)")
      (fields (field (name "PUBLISHER") "Altium Limited"))
      (libsource (lib "Miscellaneous Devices") (part "Cap Semi"))
    )
    (comp (ref "C8_11")
      (value "470nF")
      (footprint "SMD_0603_CAPC1608X80N")
      (description "Capacitor (Semiconductor SIM Model)")
      (fields (field (name "PUBLISHER") "Altium Limited"))
      (libsource (lib "Miscellaneous Devices") (part "Cap Semi"))
    )
    (comp (ref "C8_12")
      (value "470nF")
      (footprint "SMD_0603_CAPC1608X80N")
      (description "Capacitor (Semiconductor SIM Model)")
      (fields (field (name "PUBLISHER") "Altium Limited"))
      (libsource (lib "Miscellaneous Devices") (part "Cap Semi"))
    )
    (comp (ref "C8_13")
      (value "470nF")
      (footprint "SMD_0603_CAPC1608X80N")
      (description "Capacitor (Semiconductor SIM Model)")
      (fields (field (name "PUBLISHER") "Altium Limited"))
      (libsource (lib "Miscellaneous Devices") (part "Cap Semi"))
    )
    (comp (ref "C8_14")
      (value "470nF")
      (footprint "SMD_0603_CAPC1608X80N")
      (description "Capacitor (Semiconductor SIM Model)")
      (fields (field (name "PUBLISHER") "Altium Limited"))
      (libsource (lib "Miscellaneous Devices") (part "Cap Semi"))
    )
    (comp (ref "C8_15")
      (value "470nF")
      (footprint "SMD_0603_CAPC1608X80N")
      (description "Capacitor (Semiconductor SIM Model)")
      (fields (field (name "PUBLISHER") "Altium Limited"))
      (libsource (lib "Miscellaneous Devices") (part "Cap Semi"))
    )
    (comp (ref "C8_16")
      (value "470nF")
      (footprint "SMD_0603_CAPC1608X80N")
      (description "Capacitor (Semiconductor SIM Model)")
      (fields (field (name "PUBLISHER") "Altium Limited"))
      (libsource (lib "Miscellaneous Devices") (part "Cap Semi"))
    )
    (comp (ref "C9_1")
      (value "470nF")
      (footprint "SMD_0603_CAPC1608X80N")
      (description "Capacitor (Semiconductor SIM Model)")
      (fields (field (name "PUBLISHER") "Altium Limited"))
      (libsource (lib "Miscellaneous Devices") (part "Cap Semi"))
    )
    (comp (ref "C9_2")
      (value "470nF")
      (footprint "SMD_0603_CAPC1608X80N")
      (description "Capacitor (Semiconductor SIM Model)")
      (fields (field (name "PUBLISHER") "Altium Limited"))
      (libsource (lib "Miscellaneous Devices") (part "Cap Semi"))
    )
    (comp (ref "C9_3")
      (value "470nF")
      (footprint "SMD_0603_CAPC1608X80N")
      (description "Capacitor (Semiconductor SIM Model)")
      (fields (field (name "PUBLISHER") "Altium Limited"))
      (libsource (lib "Miscellaneous Devices") (part "Cap Semi"))
    )
    (comp (ref "C9_4")
      (value "470nF")
      (footprint "SMD_0603_CAPC1608X80N")
      (description "Capacitor (Semiconductor SIM Model)")
      (fields (field (name "PUBLISHER") "Altium Limited"))
      (libsource (lib "Miscellaneous Devices") (part "Cap Semi"))
    )
    (comp (ref "C9_5")
      (value "470nF")
      (footprint "SMD_0603_CAPC1608X80N")
      (description "Capacitor (Semiconductor SIM Model)")
      (fields (field (name "PUBLISHER") "Altium Limited"))
      (libsource (lib "Miscellaneous Devices") (part "Cap Semi"))
    )
    (comp (ref "C9_6")
      (value "470nF")
      (footprint "SMD_0603_CAPC1608X80N")
      (description "Capacitor (Semiconductor SIM Model)")
      (fields (field (name "PUBLISHER") "Altium Limited"))
      (libsource (lib "Miscellaneous Devices") (part "Cap Semi"))
    )
    (comp (ref "C9_7")
      (value "470nF")
      (footprint "SMD_0603_CAPC1608X80N")
      (description "Capacitor (Semiconductor SIM Model)")
      (fields (field (name "PUBLISHER") "Altium Limited"))
      (libsource (lib "Miscellaneous Devices") (part "Cap Semi"))
    )
    (comp (ref "C9_8")
      (value "470nF")
      (footprint "SMD_0603_CAPC1608X80N")
      (description "Capacitor (Semiconductor SIM Model)")
      (fields (field (name "PUBLISHER") "Altium Limited"))
      (libsource (lib "Miscellaneous Devices") (part "Cap Semi"))
    )
    (comp (ref "C9_9")
      (value "470nF")
      (footprint "SMD_0603_CAPC1608X80N")
      (description "Capacitor (Semiconductor SIM Model)")
      (fields (field (name "PUBLISHER") "Altium Limited"))
      (libsource (lib "Miscellaneous Devices") (part "Cap Semi"))
    )
    (comp (ref "C9_10")
      (value "470nF")
      (footprint "SMD_0603_CAPC1608X80N")
      (description "Capacitor (Semiconductor SIM Model)")
      (fields (field (name "PUBLISHER") "Altium Limited"))
      (libsource (lib "Miscellaneous Devices") (part "Cap Semi"))
    )
    (comp (ref "C9_11")
      (value "470nF")
      (footprint "SMD_0603_CAPC1608X80N")
      (description "Capacitor (Semiconductor SIM Model)")
      (fields (field (name "PUBLISHER") "Altium Limited"))
      (libsource (lib "Miscellaneous Devices") (part "Cap Semi"))
    )
    (comp (ref "C9_12")
      (value "470nF")
      (footprint "SMD_0603_CAPC1608X80N")
      (description "Capacitor (Semiconductor SIM Model)")
      (fields (field (name "PUBLISHER") "Altium Limited"))
      (libsource (lib "Miscellaneous Devices") (part "Cap Semi"))
    )
    (comp (ref "C9_13")
      (value "470nF")
      (footprint "SMD_0603_CAPC1608X80N")
      (description "Capacitor (Semiconductor SIM Model)")
      (fields (field (name "PUBLISHER") "Altium Limited"))
      (libsource (lib "Miscellaneous Devices") (part "Cap Semi"))
    )
    (comp (ref "C9_14")
      (value "470nF")
      (footprint "SMD_0603_CAPC1608X80N")
      (description "Capacitor (Semiconductor SIM Model)")
      (fields (field (name "PUBLISHER") "Altium Limited"))
      (libsource (lib "Miscellaneous Devices") (part "Cap Semi"))
    )
    (comp (ref "C9_15")
      (value "470nF")
      (footprint "SMD_0603_CAPC1608X80N")
      (description "Capacitor (Semiconductor SIM Model)")
      (fields (field (name "PUBLISHER") "Altium Limited"))
      (libsource (lib "Miscellaneous Devices") (part "Cap Semi"))
    )
    (comp (ref "C9_16")
      (value "470nF")
      (footprint "SMD_0603_CAPC1608X80N")
      (description "Capacitor (Semiconductor SIM Model)")
      (fields (field (name "PUBLISHER") "Altium Limited"))
      (libsource (lib "Miscellaneous Devices") (part "Cap Semi"))
    )
    (comp (ref "C10_1")
      (value "470nF")
      (footprint "SMD_0603_CAPC1608X80N")
      (description "Capacitor (Semiconductor SIM Model)")
      (fields (field (name "PUBLISHER") "Altium Limited"))
      (libsource (lib "Miscellaneous Devices") (part "Cap Semi"))
    )
    (comp (ref "C10_2")
      (value "470nF")
      (footprint "SMD_0603_CAPC1608X80N")
      (description "Capacitor (Semiconductor SIM Model)")
      (fields (field (name "PUBLISHER") "Altium Limited"))
      (libsource (lib "Miscellaneous Devices") (part "Cap Semi"))
    )
    (comp (ref "C10_3")
      (value "470nF")
      (footprint "SMD_0603_CAPC1608X80N")
      (description "Capacitor (Semiconductor SIM Model)")
      (fields (field (name "PUBLISHER") "Altium Limited"))
      (libsource (lib "Miscellaneous Devices") (part "Cap Semi"))
    )
    (comp (ref "C10_4")
      (value "470nF")
      (footprint "SMD_0603_CAPC1608X80N")
      (description "Capacitor (Semiconductor SIM Model)")
      (fields (field (name "PUBLISHER") "Altium Limited"))
      (libsource (lib "Miscellaneous Devices") (part "Cap Semi"))
    )
    (comp (ref "C10_5")
      (value "470nF")
      (footprint "SMD_0603_CAPC1608X80N")
      (description "Capacitor (Semiconductor SIM Model)")
      (fields (field (name "PUBLISHER") "Altium Limited"))
      (libsource (lib "Miscellaneous Devices") (part "Cap Semi"))
    )
    (comp (ref "C10_6")
      (value "470nF")
      (footprint "SMD_0603_CAPC1608X80N")
      (description "Capacitor (Semiconductor SIM Model)")
      (fields (field (name "PUBLISHER") "Altium Limited"))
      (libsource (lib "Miscellaneous Devices") (part "Cap Semi"))
    )
    (comp (ref "C10_7")
      (value "470nF")
      (footprint "SMD_0603_CAPC1608X80N")
      (description "Capacitor (Semiconductor SIM Model)")
      (fields (field (name "PUBLISHER") "Altium Limited"))
      (libsource (lib "Miscellaneous Devices") (part "Cap Semi"))
    )
    (comp (ref "C10_8")
      (value "470nF")
      (footprint "SMD_0603_CAPC1608X80N")
      (description "Capacitor (Semiconductor SIM Model)")
      (fields (field (name "PUBLISHER") "Altium Limited"))
      (libsource (lib "Miscellaneous Devices") (part "Cap Semi"))
    )
    (comp (ref "C10_9")
      (value "470nF")
      (footprint "SMD_0603_CAPC1608X80N")
      (description "Capacitor (Semiconductor SIM Model)")
      (fields (field (name "PUBLISHER") "Altium Limited"))
      (libsource (lib "Miscellaneous Devices") (part "Cap Semi"))
    )
    (comp (ref "C10_10")
      (value "470nF")
      (footprint "SMD_0603_CAPC1608X80N")
      (description "Capacitor (Semiconductor SIM Model)")
      (fields (field (name "PUBLISHER") "Altium Limited"))
      (libsource (lib "Miscellaneous Devices") (part "Cap Semi"))
    )
    (comp (ref "C10_11")
      (value "470nF")
      (footprint "SMD_0603_CAPC1608X80N")
      (description "Capacitor (Semiconductor SIM Model)")
      (fields (field (name "PUBLISHER") "Altium Limited"))
      (libsource (lib "Miscellaneous Devices") (part "Cap Semi"))
    )
    (comp (ref "C10_12")
      (value "470nF")
      (footprint "SMD_0603_CAPC1608X80N")
      (description "Capacitor (Semiconductor SIM Model)")
      (fields (field (name "PUBLISHER") "Altium Limited"))
      (libsource (lib "Miscellaneous Devices") (part "Cap Semi"))
    )
    (comp (ref "C10_13")
      (value "470nF")
      (footprint "SMD_0603_CAPC1608X80N")
      (description "Capacitor (Semiconductor SIM Model)")
      (fields (field (name "PUBLISHER") "Altium Limited"))
      (libsource (lib "Miscellaneous Devices") (part "Cap Semi"))
    )
    (comp (ref "C10_14")
      (value "470nF")
      (footprint "SMD_0603_CAPC1608X80N")
      (description "Capacitor (Semiconductor SIM Model)")
      (fields (field (name "PUBLISHER") "Altium Limited"))
      (libsource (lib "Miscellaneous Devices") (part "Cap Semi"))
    )
    (comp (ref "C10_15")
      (value "470nF")
      (footprint "SMD_0603_CAPC1608X80N")
      (description "Capacitor (Semiconductor SIM Model)")
      (fields (field (name "PUBLISHER") "Altium Limited"))
      (libsource (lib "Miscellaneous Devices") (part "Cap Semi"))
    )
    (comp (ref "C10_16")
      (value "470nF")
      (footprint "SMD_0603_CAPC1608X80N")
      (description "Capacitor (Semiconductor SIM Model)")
      (fields (field (name "PUBLISHER") "Altium Limited"))
      (libsource (lib "Miscellaneous Devices") (part "Cap Semi"))
    )
    (comp (ref "C11_1")
      (value "470nF")
      (footprint "SMD_0603_CAPC1608X80N")
      (description "Capacitor (Semiconductor SIM Model)")
      (fields (field (name "PUBLISHER") "Altium Limited"))
      (libsource (lib "Miscellaneous Devices") (part "Cap Semi"))
    )
    (comp (ref "C11_2")
      (value "470nF")
      (footprint "SMD_0603_CAPC1608X80N")
      (description "Capacitor (Semiconductor SIM Model)")
      (fields (field (name "PUBLISHER") "Altium Limited"))
      (libsource (lib "Miscellaneous Devices") (part "Cap Semi"))
    )
    (comp (ref "C11_3")
      (value "470nF")
      (footprint "SMD_0603_CAPC1608X80N")
      (description "Capacitor (Semiconductor SIM Model)")
      (fields (field (name "PUBLISHER") "Altium Limited"))
      (libsource (lib "Miscellaneous Devices") (part "Cap Semi"))
    )
    (comp (ref "C11_4")
      (value "470nF")
      (footprint "SMD_0603_CAPC1608X80N")
      (description "Capacitor (Semiconductor SIM Model)")
      (fields (field (name "PUBLISHER") "Altium Limited"))
      (libsource (lib "Miscellaneous Devices") (part "Cap Semi"))
    )
    (comp (ref "C11_5")
      (value "470nF")
      (footprint "SMD_0603_CAPC1608X80N")
      (description "Capacitor (Semiconductor SIM Model)")
      (fields (field (name "PUBLISHER") "Altium Limited"))
      (libsource (lib "Miscellaneous Devices") (part "Cap Semi"))
    )
    (comp (ref "C11_6")
      (value "470nF")
      (footprint "SMD_0603_CAPC1608X80N")
      (description "Capacitor (Semiconductor SIM Model)")
      (fields (field (name "PUBLISHER") "Altium Limited"))
      (libsource (lib "Miscellaneous Devices") (part "Cap Semi"))
    )
    (comp (ref "C11_7")
      (value "470nF")
      (footprint "SMD_0603_CAPC1608X80N")
      (description "Capacitor (Semiconductor SIM Model)")
      (fields (field (name "PUBLISHER") "Altium Limited"))
      (libsource (lib "Miscellaneous Devices") (part "Cap Semi"))
    )
    (comp (ref "C11_8")
      (value "470nF")
      (footprint "SMD_0603_CAPC1608X80N")
      (description "Capacitor (Semiconductor SIM Model)")
      (fields (field (name "PUBLISHER") "Altium Limited"))
      (libsource (lib "Miscellaneous Devices") (part "Cap Semi"))
    )
    (comp (ref "C11_9")
      (value "470nF")
      (footprint "SMD_0603_CAPC1608X80N")
      (description "Capacitor (Semiconductor SIM Model)")
      (fields (field (name "PUBLISHER") "Altium Limited"))
      (libsource (lib "Miscellaneous Devices") (part "Cap Semi"))
    )
    (comp (ref "C11_10")
      (value "470nF")
      (footprint "SMD_0603_CAPC1608X80N")
      (description "Capacitor (Semiconductor SIM Model)")
      (fields (field (name "PUBLISHER") "Altium Limited"))
      (libsource (lib "Miscellaneous Devices") (part "Cap Semi"))
    )
    (comp (ref "C11_11")
      (value "470nF")
      (footprint "SMD_0603_CAPC1608X80N")
      (description "Capacitor (Semiconductor SIM Model)")
      (fields (field (name "PUBLISHER") "Altium Limited"))
      (libsource (lib "Miscellaneous Devices") (part "Cap Semi"))
    )
    (comp (ref "C11_12")
      (value "470nF")
      (footprint "SMD_0603_CAPC1608X80N")
      (description "Capacitor (Semiconductor SIM Model)")
      (fields (field (name "PUBLISHER") "Altium Limited"))
      (libsource (lib "Miscellaneous Devices") (part "Cap Semi"))
    )
    (comp (ref "C11_13")
      (value "470nF")
      (footprint "SMD_0603_CAPC1608X80N")
      (description "Capacitor (Semiconductor SIM Model)")
      (fields (field (name "PUBLISHER") "Altium Limited"))
      (libsource (lib "Miscellaneous Devices") (part "Cap Semi"))
    )
    (comp (ref "C11_14")
      (value "470nF")
      (footprint "SMD_0603_CAPC1608X80N")
      (description "Capacitor (Semiconductor SIM Model)")
      (fields (field (name "PUBLISHER") "Altium Limited"))
      (libsource (lib "Miscellaneous Devices") (part "Cap Semi"))
    )
    (comp (ref "C11_15")
      (value "470nF")
      (footprint "SMD_0603_CAPC1608X80N")
      (description "Capacitor (Semiconductor SIM Model)")
      (fields (field (name "PUBLISHER") "Altium Limited"))
      (libsource (lib "Miscellaneous Devices") (part "Cap Semi"))
    )
    (comp (ref "C11_16")
      (value "470nF")
      (footprint "SMD_0603_CAPC1608X80N")
      (description "Capacitor (Semiconductor SIM Model)")
      (fields (field (name "PUBLISHER") "Altium Limited"))
      (libsource (lib "Miscellaneous Devices") (part "Cap Semi"))
    )
    (comp (ref "C17")
      (value "10uF/16V")
      (footprint "SMD_0805_CAPC2012X145N")
      (description "Capacitor")
      (libsource (lib "*") (part "CAP"))
    )
    (comp (ref "C34")
      (value "100nF")
      (footprint "SMD_0603_CAPC1608X80N")
      (description "Capacitor")
      (libsource (lib "*") (part "CAP"))
    )
    (comp (ref "C63")
      (value "22uF/6.3V")
      (footprint "SMD_0805_CAPC2012X145N")
      (description "Capacitor")
      (libsource (lib "*") (part "CAP"))
    )
    (comp (ref "C72")
      (value "100nF")
      (footprint "SMD_0603_CAPC1608X80N")
      (description "Capacitor")
      (libsource (lib "*") (part "CAP"))
    )
    (comp (ref "C73")
      (value "100nF")
      (footprint "SMD_0603_CAPC1608X80N")
      (description "Capacitor")
      (libsource (lib "*") (part "CAP"))
    )
    (comp (ref "C74")
      (value "100nF")
      (footprint "SMD_0603_CAPC1608X80N")
      (description "Capacitor")
      (libsource (lib "*") (part "CAP"))
    )
    (comp (ref "C75")
      (value "100nF")
      (footprint "SMD_0603_CAPC1608X80N")
      (description "Capacitor")
      (libsource (lib "*") (part "CAP"))
    )
    (comp (ref "C76")
      (value "100nF")
      (footprint "SMD_0603_CAPC1608X80N")
      (description "Capacitor")
      (libsource (lib "*") (part "CAP"))
    )
    (comp (ref "C85")
      (value "18pF")
      (footprint "SMD_0603_CAPC1608X80N")
      (description "Capacitor")
      (libsource (lib "*") (part "CAP"))
    )
    (comp (ref "C86")
      (value "18pF")
      (footprint "SMD_0603_CAPC1608X80N")
      (description "Capacitor")
      (libsource (lib "*") (part "CAP"))
    )
    (comp (ref "C187")
      (value "10uF/16V")
      (footprint "SMD_0805_CAPC2012X145N")
      (description "Capacitor")
      (libsource (lib "*") (part "CAP"))
    )
    (comp (ref "C188")
      (value "10uF/16V")
      (footprint "SMD_0805_CAPC2012X145N")
      (description "Capacitor")
      (libsource (lib "*") (part "CAP"))
    )
    (comp (ref "C189")
      (value "100nF/50V")
      (footprint "SMD_0805_CAPC2012X145N")
      (description "Capacitor")
      (libsource (lib "*") (part "CAP"))
    )
    (comp (ref "C190")
      (value "10uF/16V")
      (footprint "SMD_0805_CAPC2012X145N")
      (description "Capacitor")
      (libsource (lib "*") (part "CAP"))
    )
    (comp (ref "C191")
      (value "10uF/16V")
      (footprint "SMD_0805_CAPC2012X145N")
      (description "Capacitor")
      (libsource (lib "*") (part "CAP"))
    )
    (comp (ref "C192")
      (value "10uF/16V")
      (footprint "SMD_0805_CAPC2012X145N")
      (description "Capacitor")
      (libsource (lib "*") (part "CAP"))
    )
    (comp (ref "C193")
      (value "10uF/16V")
      (footprint "SMD_0805_CAPC2012X145N")
      (description "Capacitor")
      (libsource (lib "*") (part "CAP"))
    )
    (comp (ref "C194")
      (value "10uF/16V")
      (footprint "SMD_0805_CAPC2012X145N")
      (description "Capacitor")
      (libsource (lib "*") (part "CAP"))
    )
    (comp (ref "C195")
      (value "10uF/16V")
      (footprint "SMD_0805_CAPC2012X145N")
      (description "Capacitor")
      (libsource (lib "*") (part "CAP"))
    )
    (comp (ref "C196")
      (value "10uF/16V")
      (footprint "SMD_0805_CAPC2012X145N")
      (description "Capacitor")
      (libsource (lib "*") (part "CAP"))
    )
    (comp (ref "C197")
      (value "10uF/16V")
      (footprint "SMD_0805_CAPC2012X145N")
      (description "Capacitor")
      (libsource (lib "*") (part "CAP"))
    )
    (comp (ref "C198")
      (value "22uF/6.3V")
      (footprint "SMD_0805_CAPC2012X145N")
      (description "Capacitor")
      (libsource (lib "*") (part "CAP"))
    )
    (comp (ref "C199")
      (value "22uF/6.3V")
      (footprint "SMD_0805_CAPC2012X145N")
      (description "Capacitor")
      (libsource (lib "*") (part "CAP"))
    )
    (comp (ref "C200")
      (value "22uF/6.3V")
      (footprint "SMD_0805_CAPC2012X145N")
      (description "Capacitor")
      (libsource (lib "*") (part "CAP"))
    )
    (comp (ref "C201")
      (value "22uF/6.3V")
      (footprint "SMD_0805_CAPC2012X145N")
      (description "Capacitor")
      (libsource (lib "*") (part "CAP"))
    )
    (comp (ref "C202")
      (value "22uF/6.3V")
      (footprint "SMD_0805_CAPC2012X145N")
      (description "Capacitor")
      (libsource (lib "*") (part "CAP"))
    )
    (comp (ref "C203")
      (value "22uF/6.3V")
      (footprint "SMD_0805_CAPC2012X145N")
      (description "Capacitor")
      (libsource (lib "*") (part "CAP"))
    )
    (comp (ref "C204")
      (value "22uF/6.3V")
      (footprint "SMD_0805_CAPC2012X145N")
      (description "Capacitor")
      (libsource (lib "*") (part "CAP"))
    )
    (comp (ref "C205")
      (value "22uF/6.3V")
      (footprint "SMD_0805_CAPC2012X145N")
      (description "Capacitor")
      (libsource (lib "*") (part "CAP"))
    )
    (comp (ref "C207")
      (value "10uF/16V")
      (footprint "SMD_0805_CAPC2012X145N")
      (description "Capacitor")
      (libsource (lib "*") (part "CAP"))
    )
    (comp (ref "C209")
      (value "1uF")
      (footprint "SMD_0805_CAPC2012X145N")
      (description "Capacitor")
      (libsource (lib "*") (part "CAP"))
    )
    (comp (ref "C211")
      (value "22uF/6.3V")
      (footprint "SMD_0805_CAPC2012X145N")
      (description "Capacitor")
      (libsource (lib "*") (part "CAP"))
    )
    (comp (ref "C212")
      (value "姨0J332M-RBJ21")
      (footprint "PTH_CAPPR500-1300X2250")
      (libsource (lib "EPIQ_DND_CIS_Library") (part "C_POL"))
    )
    (comp (ref "C213")
      (value "10uF/16V")
      (footprint "SMD_0805_CAPC2012X145N")
      (description "Capacitor")
      (libsource (lib "*") (part "CAP"))
    )
    (comp (ref "C214")
      (value "10uF/16V")
      (footprint "SMD_0805_CAPC2012X145N")
      (description "Capacitor")
      (libsource (lib "*") (part "CAP"))
    )
    (comp (ref "C215")
      (value "10uF/16V")
      (footprint "SMD_0805_CAPC2012X145N")
      (description "Capacitor")
      (libsource (lib "*") (part "CAP"))
    )
    (comp (ref "C216")
      (value "10uF/16V")
      (footprint "SMD_0805_CAPC2012X145N")
      (description "Capacitor")
      (libsource (lib "*") (part "CAP"))
    )
    (comp (ref "C217")
      (value "10uF/16V")
      (footprint "SMD_0805_CAPC2012X145N")
      (description "Capacitor")
      (libsource (lib "*") (part "CAP"))
    )
    (comp (ref "C218")
      (value "10uF/16V")
      (footprint "SMD_0805_CAPC2012X145N")
      (description "Capacitor")
      (libsource (lib "*") (part "CAP"))
    )
    (comp (ref "C219")
      (value "10uF/16V")
      (footprint "SMD_0805_CAPC2012X145N")
      (description "Capacitor")
      (libsource (lib "*") (part "CAP"))
    )
    (comp (ref "C220")
      (value "22uF/6.3V")
      (footprint "SMD_0805_CAPC2012X145N")
      (description "Capacitor")
      (libsource (lib "*") (part "CAP"))
    )
    (comp (ref "C221")
      (value "22uF/6.3V")
      (footprint "SMD_0805_CAPC2012X145N")
      (description "Capacitor")
      (libsource (lib "*") (part "CAP"))
    )
    (comp (ref "C222")
      (value "22uF/6.3V")
      (footprint "SMD_0805_CAPC2012X145N")
      (description "Capacitor")
      (libsource (lib "*") (part "CAP"))
    )
    (comp (ref "C223")
      (value "22uF/6.3V")
      (footprint "SMD_0805_CAPC2012X145N")
      (description "Capacitor")
      (libsource (lib "*") (part "CAP"))
    )
    (comp (ref "C224")
      (value "22uF/6.3V")
      (footprint "SMD_0805_CAPC2012X145N")
      (description "Capacitor")
      (libsource (lib "*") (part "CAP"))
    )
    (comp (ref "C225")
      (value "22uF/6.3V")
      (footprint "SMD_0805_CAPC2012X145N")
      (description "Capacitor")
      (libsource (lib "*") (part "CAP"))
    )
    (comp (ref "C226")
      (value "22uF/6.3V")
      (footprint "SMD_0805_CAPC2012X145N")
      (description "Capacitor")
      (libsource (lib "*") (part "CAP"))
    )
    (comp (ref "C227")
      (value "22uF/6.3V")
      (footprint "SMD_0805_CAPC2012X145N")
      (description "Capacitor")
      (libsource (lib "*") (part "CAP"))
    )
    (comp (ref "C228")
      (value "姨0J332M-RBJ21")
      (footprint "PTH_CAPPR500-1300X2250")
      (libsource (lib "EPIQ_DND_CIS_Library") (part "C_POL"))
    )
    (comp (ref "C229")
      (value "22uF/6.3V")
      (footprint "SMD_0805_CAPC2012X145N")
      (description "Capacitor")
      (libsource (lib "*") (part "CAP"))
    )
    (comp (ref "C230")
      (value "10uF/16V")
      (footprint "SMD_0805_CAPC2012X145N")
      (description "Capacitor")
      (libsource (lib "*") (part "CAP"))
    )
    (comp (ref "C231")
      (value "10uF/16V")
      (footprint "SMD_0805_CAPC2012X145N")
      (description "Capacitor")
      (libsource (lib "*") (part "CAP"))
    )
    (comp (ref "C232")
      (value "姨0J332M-RBJ21")
      (footprint "PTH_CAPPR500-1300X2250")
      (libsource (lib "EPIQ_DND_CIS_Library") (part "C_POL"))
    )
    (comp (ref "C233")
      (value "22uF/6.3V")
      (footprint "SMD_0805_CAPC2012X145N")
      (description "Capacitor")
      (libsource (lib "*") (part "CAP"))
    )
    (comp (ref "C234")
      (value "22uF/6.3V")
      (footprint "SMD_0805_CAPC2012X145N")
      (description "Capacitor")
      (libsource (lib "*") (part "CAP"))
    )
    (comp (ref "C235")
      (value "22uF/6.3V")
      (footprint "SMD_0805_CAPC2012X145N")
      (description "Capacitor")
      (libsource (lib "*") (part "CAP"))
    )
    (comp (ref "C236")
      (value "22uF/6.3V")
      (footprint "SMD_0805_CAPC2012X145N")
      (description "Capacitor")
      (libsource (lib "*") (part "CAP"))
    )
    (comp (ref "C237")
      (value "22uF/6.3V")
      (footprint "SMD_0805_CAPC2012X145N")
      (description "Capacitor")
      (libsource (lib "*") (part "CAP"))
    )
    (comp (ref "C238")
      (value "姨0J332M-RBJ21")
      (footprint "PTH_CAPPR500-1300X2250")
      (libsource (lib "EPIQ_DND_CIS_Library") (part "C_POL"))
    )
    (comp (ref "C239")
      (value "姨0J332M-RBJ21")
      (footprint "PTH_CAPPR500-1300X2250")
      (libsource (lib "EPIQ_DND_CIS_Library") (part "C_POL"))
    )
    (comp (ref "C240")
      (value "22uF/6.3V")
      (footprint "SMD_0805_CAPC2012X145N")
      (description "Capacitor")
      (libsource (lib "*") (part "CAP"))
    )
    (comp (ref "C241")
      (value "22uF/6.3V")
      (footprint "SMD_0805_CAPC2012X145N")
      (description "Capacitor")
      (libsource (lib "*") (part "CAP"))
    )
    (comp (ref "C242")
      (value "22uF/6.3V")
      (footprint "SMD_0805_CAPC2012X145N")
      (description "Capacitor")
      (libsource (lib "*") (part "CAP"))
    )
    (comp (ref "C243")
      (value "22uF/6.3V")
      (footprint "SMD_0805_CAPC2012X145N")
      (description "Capacitor")
      (libsource (lib "*") (part "CAP"))
    )
    (comp (ref "C244")
      (value "22uF/6.3V")
      (footprint "SMD_0805_CAPC2012X145N")
      (description "Capacitor")
      (libsource (lib "*") (part "CAP"))
    )
    (comp (ref "C245")
      (value "22uF/6.3V")
      (footprint "SMD_0805_CAPC2012X145N")
      (description "Capacitor")
      (libsource (lib "*") (part "CAP"))
    )
    (comp (ref "C246")
      (value "22uF/6.3V")
      (footprint "SMD_0805_CAPC2012X145N")
      (description "Capacitor")
      (libsource (lib "*") (part "CAP"))
    )
    (comp (ref "C247")
      (value "22uF/6.3V")
      (footprint "SMD_0805_CAPC2012X145N")
      (description "Capacitor")
      (libsource (lib "*") (part "CAP"))
    )
    (comp (ref "C248")
      (value "22uF/6.3V")
      (footprint "SMD_0805_CAPC2012X145N")
      (description "Capacitor")
      (libsource (lib "*") (part "CAP"))
    )
    (comp (ref "C249")
      (value "22uF/6.3V")
      (footprint "SMD_0805_CAPC2012X145N")
      (description "Capacitor")
      (libsource (lib "*") (part "CAP"))
    )
    (comp (ref "C250")
      (value "22uF/6.3V")
      (footprint "SMD_0805_CAPC2012X145N")
      (description "Capacitor")
      (libsource (lib "*") (part "CAP"))
    )
    (comp (ref "C251")
      (value "1nF")
      (footprint "SMD_0603_CAPC1608X80N")
      (description "Capacitor")
      (libsource (lib "*") (part "CAP"))
    )
    (comp (ref "C252")
      (value "1uF/16V")
      (footprint "SMD_0805_CAPC2012X145N")
      (description "Capacitor")
      (libsource (lib "*") (part "CAP"))
    )
    (comp (ref "C253")
      (value "100pF")
      (footprint "SMD_0603_CAPC1608X80N")
      (description "Capacitor")
      (libsource (lib "*") (part "CAP"))
    )
    (comp (ref "C254")
      (value "100pF")
      (footprint "SMD_0603_CAPC1608X80N")
      (description "Capacitor")
      (libsource (lib "*") (part "CAP"))
    )
    (comp (ref "C256")
      (value "姨0J332M-RBJ21")
      (footprint "PTH_CAPPR500-1300X2250")
      (libsource (lib "EPIQ_DND_CIS_Library") (part "C_POL"))
    )
    (comp (ref "C257")
      (value "姨0J332M-RBJ21")
      (footprint "PTH_CAPPR500-1300X2250")
      (libsource (lib "EPIQ_DND_CIS_Library") (part "C_POL"))
    )
    (comp (ref "C258")
      (value "22uF/6.3V")
      (footprint "SMD_0805_CAPC2012X145N")
      (description "Capacitor")
      (libsource (lib "*") (part "CAP"))
    )
    (comp (ref "C259")
      (value "22uF/6.3V")
      (footprint "SMD_0805_CAPC2012X145N")
      (description "Capacitor")
      (libsource (lib "*") (part "CAP"))
    )
    (comp (ref "C260")
      (value "22uF/6.3V")
      (footprint "SMD_0805_CAPC2012X145N")
      (description "Capacitor")
      (libsource (lib "*") (part "CAP"))
    )
    (comp (ref "C261")
      (value "22uF/6.3V")
      (footprint "SMD_0805_CAPC2012X145N")
      (description "Capacitor")
      (libsource (lib "*") (part "CAP"))
    )
    (comp (ref "C262")
      (value "22uF/6.3V")
      (footprint "SMD_0805_CAPC2012X145N")
      (description "Capacitor")
      (libsource (lib "*") (part "CAP"))
    )
    (comp (ref "C263")
      (value "10uF/16V")
      (footprint "SMD_0805_CAPC2012X145N")
      (description "Capacitor")
      (libsource (lib "*") (part "CAP"))
    )
    (comp (ref "C264")
      (value "10uF/16V")
      (footprint "SMD_0805_CAPC2012X145N")
      (description "Capacitor")
      (libsource (lib "*") (part "CAP"))
    )
    (comp (ref "C265")
      (value "10uF/16V")
      (footprint "SMD_0805_CAPC2012X145N")
      (description "Capacitor")
      (libsource (lib "*") (part "CAP"))
    )
    (comp (ref "C266")
      (value "10uF/16V")
      (footprint "SMD_0805_CAPC2012X145N")
      (description "Capacitor")
      (libsource (lib "*") (part "CAP"))
    )
    (comp (ref "C267")
      (value "10uF/16V")
      (footprint "SMD_0805_CAPC2012X145N")
      (description "Capacitor")
      (libsource (lib "*") (part "CAP"))
    )
    (comp (ref "C268")
      (value "10uF/16V")
      (footprint "SMD_0805_CAPC2012X145N")
      (description "Capacitor")
      (libsource (lib "*") (part "CAP"))
    )
    (comp (ref "C269")
      (value "10uF/16V")
      (footprint "SMD_0805_CAPC2012X145N")
      (description "Capacitor")
      (libsource (lib "*") (part "CAP"))
    )
    (comp (ref "C270")
      (value "10uF/16V")
      (footprint "SMD_0805_CAPC2012X145N")
      (description "Capacitor")
      (libsource (lib "*") (part "CAP"))
    )
    (comp (ref "C271")
      (value "姨0J332M-RBJ21")
      (footprint "PTH_CAPPR500-1300X2250")
      (libsource (lib "EPIQ_DND_CIS_Library") (part "C_POL"))
    )
    (comp (ref "C273")
      (value "10uF/16V")
      (footprint "SMD_0805_CAPC2012X145N")
      (description "Capacitor")
      (libsource (lib "*") (part "CAP"))
    )
    (comp (ref "C274")
      (value "10uF/16V")
      (footprint "SMD_0805_CAPC2012X145N")
      (description "Capacitor")
      (libsource (lib "*") (part "CAP"))
    )
    (comp (ref "C275")
      (value "10uF/16V")
      (footprint "SMD_0805_CAPC2012X145N")
      (description "Capacitor")
      (libsource (lib "*") (part "CAP"))
    )
    (comp (ref "C276")
      (value "10uF/16V")
      (footprint "SMD_0805_CAPC2012X145N")
      (description "Capacitor")
      (libsource (lib "*") (part "CAP"))
    )
    (comp (ref "C277")
      (value "10uF/16V")
      (footprint "SMD_0805_CAPC2012X145N")
      (description "Capacitor")
      (libsource (lib "*") (part "CAP"))
    )
    (comp (ref "C278")
      (value "10uF/16V")
      (footprint "SMD_0805_CAPC2012X145N")
      (description "Capacitor")
      (libsource (lib "*") (part "CAP"))
    )
    (comp (ref "C279")
      (value "10uF/16V")
      (footprint "SMD_0805_CAPC2012X145N")
      (description "Capacitor")
      (libsource (lib "*") (part "CAP"))
    )
    (comp (ref "C280")
      (value "10uF/16V")
      (footprint "SMD_0805_CAPC2012X145N")
      (description "Capacitor")
      (libsource (lib "*") (part "CAP"))
    )
    (comp (ref "C282")
      (value "姨0J332M-RBJ21")
      (footprint "PTH_CAPPR500-1300X2250")
      (libsource (lib "EPIQ_DND_CIS_Library") (part "C_POL"))
    )
    (comp (ref "C283")
      (value "22uF/6.3V")
      (footprint "SMD_0805_CAPC2012X145N")
      (description "Capacitor")
      (libsource (lib "*") (part "CAP"))
    )
    (comp (ref "C284")
      (value "22uF/6.3V")
      (footprint "SMD_0805_CAPC2012X145N")
      (description "Capacitor")
      (libsource (lib "*") (part "CAP"))
    )
    (comp (ref "C285")
      (value "22uF/6.3V")
      (footprint "SMD_0805_CAPC2012X145N")
      (description "Capacitor")
      (libsource (lib "*") (part "CAP"))
    )
    (comp (ref "C286")
      (value "22uF/6.3V")
      (footprint "SMD_0805_CAPC2012X145N")
      (description "Capacitor")
      (libsource (lib "*") (part "CAP"))
    )
    (comp (ref "C287")
      (value "22uF/6.3V")
      (footprint "SMD_0805_CAPC2012X145N")
      (description "Capacitor")
      (libsource (lib "*") (part "CAP"))
    )
    (comp (ref "C288")
      (value "22uF/6.3V")
      (footprint "SMD_0805_CAPC2012X145N")
      (description "Capacitor")
      (libsource (lib "*") (part "CAP"))
    )
    (comp (ref "C289")
      (value "22uF/6.3V")
      (footprint "SMD_0805_CAPC2012X145N")
      (description "Capacitor")
      (libsource (lib "*") (part "CAP"))
    )
    (comp (ref "C290")
      (value "22uF/6.3V")
      (footprint "SMD_0805_CAPC2012X145N")
      (description "Capacitor")
      (libsource (lib "*") (part "CAP"))
    )
    (comp (ref "C291")
      (value "22uF/6.3V")
      (footprint "SMD_0805_CAPC2012X145N")
      (description "Capacitor")
      (libsource (lib "*") (part "CAP"))
    )
    (comp (ref "C292")
      (value "22uF/6.3V")
      (footprint "SMD_0805_CAPC2012X145N")
      (description "Capacitor")
      (libsource (lib "*") (part "CAP"))
    )
    (comp (ref "C293")
      (value "22uF/6.3V")
      (footprint "SMD_0805_CAPC2012X145N")
      (description "Capacitor")
      (libsource (lib "*") (part "CAP"))
    )
    (comp (ref "C294")
      (value "22uF/6.3V")
      (footprint "SMD_0805_CAPC2012X145N")
      (description "Capacitor")
      (libsource (lib "*") (part "CAP"))
    )
    (comp (ref "C295")
      (value "22uF/6.3V")
      (footprint "SMD_0805_CAPC2012X145N")
      (description "Capacitor")
      (libsource (lib "*") (part "CAP"))
    )
    (comp (ref "C296")
      (value "22uF/6.3V")
      (footprint "SMD_0805_CAPC2012X145N")
      (description "Capacitor")
      (libsource (lib "*") (part "CAP"))
    )
    (comp (ref "C297")
      (value "22uF/6.3V")
      (footprint "SMD_0805_CAPC2012X145N")
      (description "Capacitor")
      (libsource (lib "*") (part "CAP"))
    )
    (comp (ref "C298")
      (value "22uF/6.3V")
      (footprint "SMD_0805_CAPC2012X145N")
      (description "Capacitor")
      (libsource (lib "*") (part "CAP"))
    )
    (comp (ref "C299")
      (value "22uF/6.3V")
      (footprint "SMD_0805_CAPC2012X145N")
      (description "Capacitor")
      (libsource (lib "*") (part "CAP"))
    )
    (comp (ref "C300")
      (value "22uF/6.3V")
      (footprint "SMD_0805_CAPC2012X145N")
      (description "Capacitor")
      (libsource (lib "*") (part "CAP"))
    )
    (comp (ref "C301")
      (value "22uF/6.3V")
      (footprint "SMD_0805_CAPC2012X145N")
      (description "Capacitor")
      (libsource (lib "*") (part "CAP"))
    )
    (comp (ref "C302")
      (value "22uF/6.3V")
      (footprint "SMD_0805_CAPC2012X145N")
      (description "Capacitor")
      (libsource (lib "*") (part "CAP"))
    )
    (comp (ref "C303")
      (value "22uF/6.3V")
      (footprint "SMD_0805_CAPC2012X145N")
      (description "Capacitor")
      (libsource (lib "*") (part "CAP"))
    )
    (comp (ref "C304")
      (value "22uF/6.3V")
      (footprint "SMD_0805_CAPC2012X145N")
      (description "Capacitor")
      (libsource (lib "*") (part "CAP"))
    )
    (comp (ref "C305")
      (value "22uF/6.3V")
      (footprint "SMD_0805_CAPC2012X145N")
      (description "Capacitor")
      (libsource (lib "*") (part "CAP"))
    )
    (comp (ref "C306")
      (value "22uF/6.3V")
      (footprint "SMD_0805_CAPC2012X145N")
      (description "Capacitor")
      (libsource (lib "*") (part "CAP"))
    )
    (comp (ref "C307")
      (value "姨0J332M-RBJ21")
      (footprint "PTH_CAPPR500-1300X2250")
      (libsource (lib "EPIQ_DND_CIS_Library") (part "C_POL"))
    )
    (comp (ref "C308")
      (value "10uF/16V")
      (footprint "SMD_0805_CAPC2012X145N")
      (description "Capacitor")
      (libsource (lib "*") (part "CAP"))
    )
    (comp (ref "C309")
      (value "姨0J332M-RBJ21")
      (footprint "PTH_CAPPR500-1300X2250")
      (libsource (lib "EPIQ_DND_CIS_Library") (part "C_POL"))
    )
    (comp (ref "C311")
      (value "1uF/16V")
      (footprint "SMD_0805_CAPC2012X145N")
      (description "Capacitor")
      (libsource (lib "*") (part "CAP"))
    )
    (comp (ref "C312")
      (value "100nF/50V")
      (footprint "SMD_0805_CAPC2012X145N")
      (description "Capacitor")
      (libsource (lib "*") (part "CAP"))
    )
    (comp (ref "C313")
      (value "姨0J332M-RBJ21")
      (footprint "PTH_CAPPR500-1300X2250")
      (libsource (lib "EPIQ_DND_CIS_Library") (part "C_POL"))
    )
    (comp (ref "C314")
      (value "22uF/6.3V")
      (footprint "SMD_0805_CAPC2012X145N")
      (description "Capacitor")
      (libsource (lib "*") (part "CAP"))
    )
    (comp (ref "C315")
      (value "22uF/6.3V")
      (footprint "SMD_0805_CAPC2012X145N")
      (description "Capacitor")
      (libsource (lib "*") (part "CAP"))
    )
    (comp (ref "C316")
      (value "22uF/6.3V")
      (footprint "SMD_0805_CAPC2012X145N")
      (description "Capacitor")
      (libsource (lib "*") (part "CAP"))
    )
    (comp (ref "C317")
      (value "22uF/6.3V")
      (footprint "SMD_0805_CAPC2012X145N")
      (description "Capacitor")
      (libsource (lib "*") (part "CAP"))
    )
    (comp (ref "C318")
      (value "22uF/6.3V")
      (footprint "SMD_0805_CAPC2012X145N")
      (description "Capacitor")
      (libsource (lib "*") (part "CAP"))
    )
    (comp (ref "C319")
      (value "22uF/6.3V")
      (footprint "SMD_0805_CAPC2012X145N")
      (description "Capacitor")
      (libsource (lib "*") (part "CAP"))
    )
    (comp (ref "C320")
      (value "22uF/6.3V")
      (footprint "SMD_0805_CAPC2012X145N")
      (description "Capacitor")
      (libsource (lib "*") (part "CAP"))
    )
    (comp (ref "C321")
      (value "22uF/6.3V")
      (footprint "SMD_0805_CAPC2012X145N")
      (description "Capacitor")
      (libsource (lib "*") (part "CAP"))
    )
    (comp (ref "C322")
      (value "22uF/6.3V")
      (footprint "SMD_0805_CAPC2012X145N")
      (description "Capacitor")
      (libsource (lib "*") (part "CAP"))
    )
    (comp (ref "C323")
      (value "22uF/6.3V")
      (footprint "SMD_0805_CAPC2012X145N")
      (description "Capacitor")
      (libsource (lib "*") (part "CAP"))
    )
    (comp (ref "C324")
      (value "22uF/6.3V")
      (footprint "SMD_0805_CAPC2012X145N")
      (description "Capacitor")
      (libsource (lib "*") (part "CAP"))
    )
    (comp (ref "C325")
      (value "1nF")
      (footprint "SMD_0603_CAPC1608X80N")
      (description "Capacitor")
      (libsource (lib "*") (part "CAP"))
    )
    (comp (ref "D1")
      (value "BAT54C")
      (footprint "SMD_SOT23_SOT95P240X120-3N")
      (libsource (lib "EPIQ_DND_CIS_Library") (part "D_DUAL_A1A2CC3"))
    )
    (comp (ref "D2")
      (value "BAT54C")
      (footprint "SMD_SOT23_SOT95P240X120-3N")
      (libsource (lib "EPIQ_DND_CIS_Library") (part "D_DUAL_A1A2CC3"))
    )
    (comp (ref "D3")
      (value "(OPT) BAV56")
      (footprint "SMD_SOT23_SOT95P240X120-3N")
      (libsource (lib "EPIQ_DND_CIS_Library") (part "D_DUAL_A1A2CC3"))
    )
    (comp (ref "D4")
      (value "Red SML210VT ROHM")
      (footprint "SMD_0805_LED2012X100N")
      (libsource (lib "EPIQ_DND_CIS_Library") (part "LED_2"))
    )
    (comp (ref "D5")
      (value "Green 	SML210MT ROHM")
      (footprint "SMD_0805_LED2012X100N")
      (libsource (lib "EPIQ_DND_CIS_Library") (part "LED_2"))
    )
    (comp (ref "D6")
      (value "Yellow SML210YT ROHM")
      (footprint "SMD_0805_LED2012X100N")
      (libsource (lib "EPIQ_DND_CIS_Library") (part "LED_2"))
    )
    (comp (ref "D7")
      (value "Orange 	SML210DT ROHM")
      (footprint "SMD_0805_LED2012X100N")
      (libsource (lib "EPIQ_DND_CIS_Library") (part "LED_2"))
    )
    (comp (ref "J1")
      (value "(OPT) CON PROGRAM")
      (footprint "SIP5 PGM TOP")
      (description "Connector")
      (libsource (lib "Miscellaneous Devices") (part "CON5"))
    )
    (comp (ref "J2")
      (value "CON MOLEX HDD")
      (footprint "MOLEX_PWR_4P - AVALON")
      (libsource (lib "EPIQ_DND_CIS_Library") (part "CON_4PINS"))
    )
    (comp (ref "J3")
      (value "CU04SCM15B0-R0")
      (footprint "SMD_CON-CVILUX-CU04-SCM15B0")
      (libsource (lib "EPIQ_DND_CIS_Library") (part "CON_USB_MINI_1"))
    )
    (comp (ref "J6")
      (value "CON FAN")
      (footprint "PTH_CON_PANCON-MPSS100-04D")
      (libsource (lib "EPIQ_DND_CIS_Library") (part "CON_4PINS"))
    )
    (comp (ref "L1")
      (value "SLC1480-201MLD")
      (footprint "SMD_INDM12501250X800A - Coilcraft SLC1480")
      (libsource (lib "EPIQ_DND_CIS_Library") (part "L"))
    )
    (comp (ref "L2")
      (value "SLC1480-201MLD")
      (footprint "SMD_INDM12501250X800A - Coilcraft SLC1480")
      (libsource (lib "EPIQ_DND_CIS_Library") (part "L"))
    )
    (comp (ref "Q1")
      (value "AP1RA03GMT-3")
      (footprint "SMD_SON127P615X520X100-8N")
      (libsource (lib "EPIQ_DND_CIS_Library") (part "MOS_N_D1_S1S2S3G4D5D6D7D8"))
    )
    (comp (ref "Q2")
      (value "AP1RA03GMT-3")
      (footprint "SMD_SON127P615X520X100-8N")
      (libsource (lib "EPIQ_DND_CIS_Library") (part "MOS_N_D1_S1S2S3G4D5D6D7D8"))
    )
    (comp (ref "Q3")
      (value "AP1RA03GMT-3")
      (footprint "SMD_SON127P615X520X100-8N")
      (libsource (lib "EPIQ_DND_CIS_Library") (part "MOS_N_D1_S1S2S3G4D5D6D7D8"))
    )
    (comp (ref "Q4")
      (value "AP1RA03GMT-3")
      (footprint "SMD_SON127P615X520X100-8N")
      (libsource (lib "EPIQ_DND_CIS_Library") (part "MOS_N_D1_S1S2S3G4D5D6D7D8"))
    )
    (comp (ref "Q5")
      (value "AP1RA03GMT-3")
      (footprint "SMD_SON127P615X520X100-8N")
      (libsource (lib "EPIQ_DND_CIS_Library") (part "MOS_N_D1_S1S2S3G4D5D6D7D8"))
    )
    (comp (ref "Q6")
      (value "AP1RA03GMT-3")
      (footprint "SMD_SON127P615X520X100-8N")
      (libsource (lib "EPIQ_DND_CIS_Library") (part "MOS_N_D1_S1S2S3G4D5D6D7D8"))
    )
    (comp (ref "Q7")
      (value "(OPT)BSS138")
      (footprint "SMD_SOT23_SOT95P240X120-3N")
      (libsource (lib "EPIQ_DND_CIS_Library") (part "BJT_NPN_B1E2C3"))
    )
    (comp (ref "R1")
      (value "(OPT)470")
      (footprint "SMD_0603_RESC1608X55N")
      (description "Resistor")
      (fields (field (name "PUBLISHER") "Altium Limited"))
      (libsource (lib "Miscellaneous Devices") (part "Res3"))
    )
    (comp (ref "R1_1")
      (value "100K")
      (footprint "SMD_0603_RESC1608X55N")
      (description "Resistor")
      (fields (field (name "PUBLISHER") "Altium Limited"))
      (libsource (lib "Miscellaneous Devices") (part "Res3"))
    )
    (comp (ref "R1_2")
      (value "100K")
      (footprint "SMD_0603_RESC1608X55N")
      (description "Resistor")
      (fields (field (name "PUBLISHER") "Altium Limited"))
      (libsource (lib "Miscellaneous Devices") (part "Res3"))
    )
    (comp (ref "R1_3")
      (value "100K")
      (footprint "SMD_0603_RESC1608X55N")
      (description "Resistor")
      (fields (field (name "PUBLISHER") "Altium Limited"))
      (libsource (lib "Miscellaneous Devices") (part "Res3"))
    )
    (comp (ref "R1_4")
      (value "100K")
      (footprint "SMD_0603_RESC1608X55N")
      (description "Resistor")
      (fields (field (name "PUBLISHER") "Altium Limited"))
      (libsource (lib "Miscellaneous Devices") (part "Res3"))
    )
    (comp (ref "R1_5")
      (value "100K")
      (footprint "SMD_0603_RESC1608X55N")
      (description "Resistor")
      (fields (field (name "PUBLISHER") "Altium Limited"))
      (libsource (lib "Miscellaneous Devices") (part "Res3"))
    )
    (comp (ref "R1_6")
      (value "100K")
      (footprint "SMD_0603_RESC1608X55N")
      (description "Resistor")
      (fields (field (name "PUBLISHER") "Altium Limited"))
      (libsource (lib "Miscellaneous Devices") (part "Res3"))
    )
    (comp (ref "R1_7")
      (value "100K")
      (footprint "SMD_0603_RESC1608X55N")
      (description "Resistor")
      (fields (field (name "PUBLISHER") "Altium Limited"))
      (libsource (lib "Miscellaneous Devices") (part "Res3"))
    )
    (comp (ref "R1_8")
      (value "100K")
      (footprint "SMD_0603_RESC1608X55N")
      (description "Resistor")
      (fields (field (name "PUBLISHER") "Altium Limited"))
      (libsource (lib "Miscellaneous Devices") (part "Res3"))
    )
    (comp (ref "R1_9")
      (value "100K")
      (footprint "SMD_0603_RESC1608X55N")
      (description "Resistor")
      (fields (field (name "PUBLISHER") "Altium Limited"))
      (libsource (lib "Miscellaneous Devices") (part "Res3"))
    )
    (comp (ref "R1_10")
      (value "100K")
      (footprint "SMD_0603_RESC1608X55N")
      (description "Resistor")
      (fields (field (name "PUBLISHER") "Altium Limited"))
      (libsource (lib "Miscellaneous Devices") (part "Res3"))
    )
    (comp (ref "R1_11")
      (value "100K")
      (footprint "SMD_0603_RESC1608X55N")
      (description "Resistor")
      (fields (field (name "PUBLISHER") "Altium Limited"))
      (libsource (lib "Miscellaneous Devices") (part "Res3"))
    )
    (comp (ref "R1_12")
      (value "100K")
      (footprint "SMD_0603_RESC1608X55N")
      (description "Resistor")
      (fields (field (name "PUBLISHER") "Altium Limited"))
      (libsource (lib "Miscellaneous Devices") (part "Res3"))
    )
    (comp (ref "R1_13")
      (value "100K")
      (footprint "SMD_0603_RESC1608X55N")
      (description "Resistor")
      (fields (field (name "PUBLISHER") "Altium Limited"))
      (libsource (lib "Miscellaneous Devices") (part "Res3"))
    )
    (comp (ref "R1_14")
      (value "100K")
      (footprint "SMD_0603_RESC1608X55N")
      (description "Resistor")
      (fields (field (name "PUBLISHER") "Altium Limited"))
      (libsource (lib "Miscellaneous Devices") (part "Res3"))
    )
    (comp (ref "R1_15")
      (value "100K")
      (footprint "SMD_0603_RESC1608X55N")
      (description "Resistor")
      (fields (field (name "PUBLISHER") "Altium Limited"))
      (libsource (lib "Miscellaneous Devices") (part "Res3"))
    )
    (comp (ref "R1_16")
      (value "100K")
      (footprint "SMD_0603_RESC1608X55N")
      (description "Resistor")
      (fields (field (name "PUBLISHER") "Altium Limited"))
      (libsource (lib "Miscellaneous Devices") (part "Res3"))
    )
    (comp (ref "R2")
      (value "0")
      (footprint "SMD_0603_RESC1608X55N")
      (description "Resistor")
      (fields (field (name "PUBLISHER") "Altium Limited"))
      (libsource (lib "Miscellaneous Devices") (part "Res3"))
    )
    (comp (ref "R9")
      (value "10k")
      (footprint "SMD_0603_RESC1608X55N")
      (description "Resistor")
      (fields (field (name "PUBLISHER") "Altium Limited"))
      (libsource (lib "Miscellaneous Devices") (part "Res3"))
    )
    (comp (ref "R18")
      (value "0")
      (footprint "SMD_0603_RESC1608X55N")
      (description "Resistor")
      (fields (field (name "PUBLISHER") "Altium Limited"))
      (libsource (lib "Miscellaneous Devices") (part "Res3"))
    )
    (comp (ref "R19")
      (value "0")
      (footprint "SMD_0603_RESC1608X55N")
      (description "Resistor")
      (fields (field (name "PUBLISHER") "Altium Limited"))
      (libsource (lib "Miscellaneous Devices") (part "Res3"))
    )
    (comp (ref "R22")
      (value "0")
      (footprint "SMD_0603_RESC1608X55N")
      (description "Resistor")
      (fields (field (name "PUBLISHER") "Altium Limited"))
      (libsource (lib "Miscellaneous Devices") (part "Res3"))
    )
    (comp (ref "R23")
      (value "0")
      (footprint "SMD_0603_RESC1608X55N")
      (description "Resistor")
      (fields (field (name "PUBLISHER") "Altium Limited"))
      (libsource (lib "Miscellaneous Devices") (part "Res3"))
    )
    (comp (ref "R24")
      (value "0")
      (footprint "SMD_0603_RESC1608X55N")
      (description "Resistor")
      (fields (field (name "PUBLISHER") "Altium Limited"))
      (libsource (lib "Miscellaneous Devices") (part "Res3"))
    )
    (comp (ref "R25")
      (value "0")
      (footprint "SMD_0603_RESC1608X55N")
      (description "Resistor")
      (fields (field (name "PUBLISHER") "Altium Limited"))
      (libsource (lib "Miscellaneous Devices") (part "Res3"))
    )
    (comp (ref "R26")
      (value "0")
      (footprint "SMD_0603_RESC1608X55N")
      (description "Resistor")
      (fields (field (name "PUBLISHER") "Altium Limited"))
      (libsource (lib "Miscellaneous Devices") (part "Res3"))
    )
    (comp (ref "R27")
      (value "0")
      (footprint "SMD_0603_RESC1608X55N")
      (description "Resistor")
      (fields (field (name "PUBLISHER") "Altium Limited"))
      (libsource (lib "Miscellaneous Devices") (part "Res3"))
    )
    (comp (ref "R34")
      (value "27")
      (footprint "SMD_0603_RESC1608X55N")
      (description "Resistor")
      (fields (field (name "PUBLISHER") "Altium Limited"))
      (libsource (lib "Miscellaneous Devices") (part "Res3"))
    )
    (comp (ref "R35")
      (value "27")
      (footprint "SMD_0603_RESC1608X55N")
      (description "Resistor")
      (fields (field (name "PUBLISHER") "Altium Limited"))
      (libsource (lib "Miscellaneous Devices") (part "Res3"))
    )
    (comp (ref "R36")
      (value "768")
      (footprint "SMD_0603_RESC1608X55N")
      (description "Resistor")
      (fields (field (name "PUBLISHER") "Altium Limited"))
      (libsource (lib "Miscellaneous Devices") (part "Res3"))
    )
    (comp (ref "R37")
      (value "2.4k")
      (footprint "SMD_0603_RESC1608X55N")
      (description "Resistor")
      (fields (field (name "PUBLISHER") "Altium Limited"))
      (libsource (lib "Miscellaneous Devices") (part "Res3"))
    )
    (comp (ref "R38")
      (value "2.4k")
      (footprint "SMD_0603_RESC1608X55N")
      (description "Resistor")
      (fields (field (name "PUBLISHER") "Altium Limited"))
      (libsource (lib "Miscellaneous Devices") (part "Res3"))
    )
    (comp (ref "R40")
      (value "10k")
      (footprint "SMD_0603_RESC1608X55N")
      (description "Resistor")
      (fields (field (name "PUBLISHER") "Altium Limited"))
      (libsource (lib "Miscellaneous Devices") (part "Res3"))
    )
    (comp (ref "R42")
      (value "(OPT)0")
      (footprint "SMD_0603_RESC1608X55N")
      (description "Resistor")
      (fields (field (name "PUBLISHER") "Altium Limited"))
      (libsource (lib "Miscellaneous Devices") (part "Res3"))
    )
    (comp (ref "R43")
      (value "10k")
      (footprint "SMD_0603_RESC1608X55N")
      (description "Resistor")
      (fields (field (name "PUBLISHER") "Altium Limited"))
      (libsource (lib "Miscellaneous Devices") (part "Res3"))
    )
    (comp (ref "R44")
      (value "10k")
      (footprint "SMD_0603_RESC1608X55N")
      (description "Resistor")
      (fields (field (name "PUBLISHER") "Altium Limited"))
      (libsource (lib "Miscellaneous Devices") (part "Res3"))
    )
    (comp (ref "R45")
      (value "2.4k")
      (footprint "SMD_0603_RESC1608X55N")
      (description "Resistor")
      (fields (field (name "PUBLISHER") "Altium Limited"))
      (libsource (lib "Miscellaneous Devices") (part "Res3"))
    )
    (comp (ref "R46")
      (value "0")
      (footprint "SMD_1206_RESC3216X180N")
      (description "Resistor")
      (fields (field (name "PUBLISHER") "Altium Limited"))
      (libsource (lib "Miscellaneous Devices") (part "Res3"))
    )
    (comp (ref "R47")
      (value "0")
      (footprint "SMD_1206_RESC3216X180N")
      (description "Resistor")
      (fields (field (name "PUBLISHER") "Altium Limited"))
      (libsource (lib "Miscellaneous Devices") (part "Res3"))
    )
    (comp (ref "R48")
      (value "(OPT)470")
      (footprint "SMD_0603_RESC1608X55N")
      (description "Resistor")
      (fields (field (name "PUBLISHER") "Altium Limited"))
      (libsource (lib "Miscellaneous Devices") (part "Res3"))
    )
    (comp (ref "R49")
      (value "(OPT)470")
      (footprint "SMD_0603_RESC1608X55N")
      (description "Resistor")
      (fields (field (name "PUBLISHER") "Altium Limited"))
      (libsource (lib "Miscellaneous Devices") (part "Res3"))
    )
    (comp (ref "R50")
      (value "470")
      (footprint "SMD_0603_RESC1608X55N")
      (description "Resistor")
      (fields (field (name "PUBLISHER") "Altium Limited"))
      (libsource (lib "Miscellaneous Devices") (part "Res3"))
    )
    (comp (ref "R51")
      (value "470")
      (footprint "SMD_0603_RESC1608X55N")
      (description "Resistor")
      (fields (field (name "PUBLISHER") "Altium Limited"))
      (libsource (lib "Miscellaneous Devices") (part "Res3"))
    )
    (comp (ref "R52")
      (value "(OPT)470")
      (footprint "SMD_0603_RESC1608X55N")
      (description "Resistor")
      (fields (field (name "PUBLISHER") "Altium Limited"))
      (libsource (lib "Miscellaneous Devices") (part "Res3"))
    )
    (comp (ref "R53")
      (value "(OPT)470")
      (footprint "SMD_0603_RESC1608X55N")
      (description "Resistor")
      (fields (field (name "PUBLISHER") "Altium Limited"))
      (libsource (lib "Miscellaneous Devices") (part "Res3"))
    )
    (comp (ref "R54")
      (value "(OPT)470")
      (footprint "SMD_0603_RESC1608X55N")
      (description "Resistor")
      (fields (field (name "PUBLISHER") "Altium Limited"))
      (libsource (lib "Miscellaneous Devices") (part "Res3"))
    )
    (comp (ref "R55")
      (value "(OPT)470")
      (footprint "SMD_0603_RESC1608X55N")
      (description "Resistor")
      (fields (field (name "PUBLISHER") "Altium Limited"))
      (libsource (lib "Miscellaneous Devices") (part "Res3"))
    )
    (comp (ref "R56")
      (value "0")
      (footprint "SMD_0603_RESC1608X55N")
      (description "Resistor")
      (fields (field (name "PUBLISHER") "Altium Limited"))
      (libsource (lib "Miscellaneous Devices") (part "Res3"))
    )
    (comp (ref "R57")
      (value "10k")
      (footprint "SMD_0603_RESC1608X55N")
      (description "Resistor")
      (fields (field (name "PUBLISHER") "Altium Limited"))
      (libsource (lib "Miscellaneous Devices") (part "Res3"))
    )
    (comp (ref "R59")
      (value "10k")
      (footprint "SMD_0603_RESC1608X55N")
      (description "Resistor")
      (fields (field (name "PUBLISHER") "Altium Limited"))
      (libsource (lib "Miscellaneous Devices") (part "Res3"))
    )
    (comp (ref "R60")
      (value "0")
      (footprint "SMD_1206_RESC3216X180N")
      (description "Resistor")
      (fields (field (name "PUBLISHER") "Altium Limited"))
      (libsource (lib "Miscellaneous Devices") (part "Res3"))
    )
    (comp (ref "R61")
      (value "2.4k")
      (footprint "SMD_0603_RESC1608X55N")
      (description "Resistor")
      (fields (field (name "PUBLISHER") "Altium Limited"))
      (libsource (lib "Miscellaneous Devices") (part "Res3"))
    )
    (comp (ref "R62")
      (value "(OPT)0")
      (footprint "SMD_0603_RESC1608X55N")
      (description "Resistor")
      (fields (field (name "PUBLISHER") "Altium Limited"))
      (libsource (lib "Miscellaneous Devices") (part "Res3"))
    )
    (comp (ref "R63")
      (value "0")
      (footprint "SMD_0603_RESC1608X55N")
      (description "Resistor")
      (fields (field (name "PUBLISHER") "Altium Limited"))
      (libsource (lib "Miscellaneous Devices") (part "Res3"))
    )
    (comp (ref "R64")
      (value "0")
      (footprint "SMD_0603_RESC1608X55N")
      (description "Resistor")
      (fields (field (name "PUBLISHER") "Altium Limited"))
      (libsource (lib "Miscellaneous Devices") (part "Res3"))
    )
    (comp (ref "U1")
      (value "dsPIC33EP256MU806")
      (footprint "SMD_QFP50P1200X1200X120-64N")
      (libsource (lib "MCU") (part "dsPIC33EP256MU806"))
    )
    (comp (ref "U1_1")
      (value "A3255Q48")
      (footprint "SMD_QFN50P700X700X90-49N")
      (description "Avalon2 SHA256")
      (libsource (lib "DevicesA10") (part "A3255Q48"))
    )
    (comp (ref "U1_2")
      (value "A3255Q48")
      (footprint "SMD_QFN50P700X700X90-49N")
      (description "Avalon2 SHA256")
      (libsource (lib "DevicesA10") (part "A3255Q48"))
    )
    (comp (ref "U1_3")
      (value "A3255Q48")
      (footprint "SMD_QFN50P700X700X90-49N")
      (description "Avalon2 SHA256")
      (libsource (lib "DevicesA10") (part "A3255Q48"))
    )
    (comp (ref "U1_4")
      (value "A3255Q48")
      (footprint "SMD_QFN50P700X700X90-49N")
      (description "Avalon2 SHA256")
      (libsource (lib "DevicesA10") (part "A3255Q48"))
    )
    (comp (ref "U1_5")
      (value "A3255Q48")
      (footprint "SMD_QFN50P700X700X90-49N")
      (description "Avalon2 SHA256")
      (libsource (lib "DevicesA10") (part "A3255Q48"))
    )
    (comp (ref "U1_6")
      (value "A3255Q48")
      (footprint "SMD_QFN50P700X700X90-49N")
      (description "Avalon2 SHA256")
      (libsource (lib "DevicesA10") (part "A3255Q48"))
    )
    (comp (ref "U1_7")
      (value "A3255Q48")
      (footprint "SMD_QFN50P700X700X90-49N")
      (description "Avalon2 SHA256")
      (libsource (lib "DevicesA10") (part "A3255Q48"))
    )
    (comp (ref "U1_8")
      (value "A3255Q48")
      (footprint "SMD_QFN50P700X700X90-49N")
      (description "Avalon2 SHA256")
      (libsource (lib "DevicesA10") (part "A3255Q48"))
    )
    (comp (ref "U1_9")
      (value "A3255Q48")
      (footprint "SMD_QFN50P700X700X90-49N")
      (description "Avalon2 SHA256")
      (libsource (lib "DevicesA10") (part "A3255Q48"))
    )
    (comp (ref "U1_10")
      (value "A3255Q48")
      (footprint "SMD_QFN50P700X700X90-49N")
      (description "Avalon2 SHA256")
      (libsource (lib "DevicesA10") (part "A3255Q48"))
    )
    (comp (ref "U1_11")
      (value "A3255Q48")
      (footprint "SMD_QFN50P700X700X90-49N")
      (description "Avalon2 SHA256")
      (libsource (lib "DevicesA10") (part "A3255Q48"))
    )
    (comp (ref "U1_12")
      (value "A3255Q48")
      (footprint "SMD_QFN50P700X700X90-49N")
      (description "Avalon2 SHA256")
      (libsource (lib "DevicesA10") (part "A3255Q48"))
    )
    (comp (ref "U1_13")
      (value "A3255Q48")
      (footprint "SMD_QFN50P700X700X90-49N")
      (description "Avalon2 SHA256")
      (libsource (lib "DevicesA10") (part "A3255Q48"))
    )
    (comp (ref "U1_14")
      (value "A3255Q48")
      (footprint "SMD_QFN50P700X700X90-49N")
      (description "Avalon2 SHA256")
      (libsource (lib "DevicesA10") (part "A3255Q48"))
    )
    (comp (ref "U1_15")
      (value "A3255Q48")
      (footprint "SMD_QFN50P700X700X90-49N")
      (description "Avalon2 SHA256")
      (libsource (lib "DevicesA10") (part "A3255Q48"))
    )
    (comp (ref "U1_16")
      (value "A3255Q48")
      (footprint "SMD_QFN50P700X700X90-49N")
      (description "Avalon2 SHA256")
      (libsource (lib "DevicesA10") (part "A3255Q48"))
    )
    (comp (ref "U2")
      (value "(OPT)74AUP1G02GW")
      (footprint "SMD_SOT353_SOT65P210X110-5AN")
      (libsource (lib "Devices") (part "74AUP1G02GW"))
    )
    (comp (ref "U3")
      (value "(OPT)74HC02")
      (footprint "SMD_SOIC127P600X175-14N")
      (libsource (lib "Devices") (part "74HC02"))
    )
    (comp (ref "U6")
      (value "(OPT)BU33TD3WG-TR")
      (footprint "SMD_SOT26_SOT95P285X140-5N - DLV")
      (libsource (lib "Miscellaneous Devices") (part "VOLTREG LDO"))
    )
    (comp (ref "U19")
      (value "BD33KA5WF")
      (footprint "SMD_SOIC127P602X173-8N")
      (libsource (lib "EPIQ_DND_CIS_Library") (part "IC_LM2931AD-5.0R2G_SO-8"))
    )
    (comp (ref "U20")
      (value "L78M05CDT-TR")
      (footprint "SMD_TO229P991X239-4AN_DPAK")
      (libsource (lib "EPIQ_DND_CIS_Library") (part "IC_Vout1GND2Vin3"))
    )
    (comp (ref "U22")
      (value "(OPT) LM7805")
      (footprint "SMD_SOIC127P602X173-8N")
      (libsource (lib "EPIQ_DND_CIS_Library") (part "IC_LM2931AD-5.0R2G_SO-8"))
    )
    (comp (ref "U23")
      (value "(OPT) L7805CD2T-TR")
      (footprint "SMD_TO254P1524X483-3_4N_D2PAK + DPAK")
      (libsource (lib "EPIQ_DND_CIS_Library") (part "IC_Vout1GND2Vin3"))
    )
    (comp (ref "U25")
      (value "LTC 4449")
      (footprint "SMD_SOP65P490X110-9N - DUAL")
      (description "Mosfet 12V Dual Bootstrapped PWM Sync Buck Optimised")
      (libsource (lib "Devices") (part "DRVFET_LTC4442"))
    )
    (comp (ref "U30")
      (value "LTC 4449")
      (footprint "SMD_SOP65P490X110-9N - DUAL")
      (description "Mosfet 12V Dual Bootstrapped PWM Sync Buck Optimised")
      (libsource (lib "Devices") (part "DRVFET_LTC4442"))
    )
    (comp (ref "Y1")
      (value "Q4.000 MHz HC-49SM SMD")
      (footprint "SMD_HC49_XTAL1140X480X420N")
      (description "Crystal")
      (libsource (lib "*") (part "CRYSTAL"))
    )
  )
  (nets
    (net (code "1") (name "/1.0V") (class "Default")
      (node (ref "C11_1") (pin "1") (pinfunction "1_1") (pintype "passive"))
      (node (ref "C11_10") (pin "1") (pinfunction "1_1") (pintype "passive"))
      (node (ref "C11_11") (pin "1") (pinfunction "1_1") (pintype "passive"))
      (node (ref "C11_12") (pin "1") (pinfunction "1_1") (pintype "passive"))
      (node (ref "C11_13") (pin "1") (pinfunction "1_1") (pintype "passive"))
      (node (ref "C11_14") (pin "1") (pinfunction "1_1") (pintype "passive"))
      (node (ref "C11_15") (pin "1") (pinfunction "1_1") (pintype "passive"))
      (node (ref "C11_16") (pin "1") (pinfunction "1_1") (pintype "passive"))
      (node (ref "C11_2") (pin "1") (pinfunction "1_1") (pintype "passive"))
      (node (ref "C11_3") (pin "1") (pinfunction "1_1") (pintype "passive"))
      (node (ref "C11_4") (pin "1") (pinfunction "1_1") (pintype "passive"))
      (node (ref "C11_5") (pin "1") (pinfunction "1_1") (pintype "passive"))
      (node (ref "C11_6") (pin "1") (pinfunction "1_1") (pintype "passive"))
      (node (ref "C11_7") (pin "1") (pinfunction "1_1") (pintype "passive"))
      (node (ref "C11_8") (pin "1") (pinfunction "1_1") (pintype "passive"))
      (node (ref "C11_9") (pin "1") (pinfunction "1_1") (pintype "passive"))
      (node (ref "C198") (pin "1") (pinfunction "1_1") (pintype "passive"))
      (node (ref "C199") (pin "1") (pinfunction "1_1") (pintype "passive"))
      (node (ref "C1_1") (pin "1") (pinfunction "1_1") (pintype "passive"))
      (node (ref "C1_10") (pin "1") (pinfunction "1_1") (pintype "passive"))
      (node (ref "C1_11") (pin "1") (pinfunction "1_1") (pintype "passive"))
      (node (ref "C1_12") (pin "1") (pinfunction "1_1") (pintype "passive"))
      (node (ref "C1_13") (pin "1") (pinfunction "1_1") (pintype "passive"))
      (node (ref "C1_14") (pin "1") (pinfunction "1_1") (pintype "passive"))
      (node (ref "C1_15") (pin "1") (pinfunction "1_1") (pintype "passive"))
      (node (ref "C1_16") (pin "1") (pinfunction "1_1") (pintype "passive"))
      (node (ref "C1_2") (pin "1") (pinfunction "1_1") (pintype "passive"))
      (node (ref "C1_3") (pin "1") (pinfunction "1_1") (pintype "passive"))
      (node (ref "C1_4") (pin "1") (pinfunction "1_1") (pintype "passive"))
      (node (ref "C1_5") (pin "1") (pinfunction "1_1") (pintype "passive"))
      (node (ref "C1_6") (pin "1") (pinfunction "1_1") (pintype "passive"))
      (node (ref "C1_7") (pin "1") (pinfunction "1_1") (pintype "passive"))
      (node (ref "C1_8") (pin "1") (pinfunction "1_1") (pintype "passive"))
      (node (ref "C1_9") (pin "1") (pinfunction "1_1") (pintype "passive"))
      (node (ref "C200") (pin "1") (pinfunction "1_1") (pintype "passive"))
      (node (ref "C201") (pin "1") (pinfunction "1_1") (pintype "passive"))
      (node (ref "C202") (pin "1") (pinfunction "1_1") (pintype "passive"))
      (node (ref "C203") (pin "1") (pinfunction "1_1") (pintype "passive"))
      (node (ref "C204") (pin "1") (pinfunction "1_1") (pintype "passive"))
      (node (ref "C205") (pin "1") (pinfunction "1_1") (pintype "passive"))
      (node (ref "C209") (pin "2") (pinfunction "2_2") (pintype "passive"))
      (node (ref "C212") (pin "1") (pinfunction "1_1") (pintype "passive"))
      (node (ref "C220") (pin "1") (pinfunction "1_1") (pintype "passive"))
      (node (ref "C221") (pin "1") (pinfunction "1_1") (pintype "passive"))
      (node (ref "C222") (pin "1") (pinfunction "1_1") (pintype "passive"))
      (node (ref "C223") (pin "1") (pinfunction "1_1") (pintype "passive"))
      (node (ref "C224") (pin "1") (pinfunction "1_1") (pintype "passive"))
      (node (ref "C225") (pin "1") (pinfunction "1_1") (pintype "passive"))
      (node (ref "C226") (pin "1") (pinfunction "1_1") (pintype "passive"))
      (node (ref "C227") (pin "1") (pinfunction "1_1") (pintype "passive"))
      (node (ref "C228") (pin "1") (pinfunction "1_1") (pintype "passive"))
      (node (ref "C232") (pin "1") (pinfunction "1_1") (pintype "passive"))
      (node (ref "C238") (pin "1") (pinfunction "1_1") (pintype "passive"))
      (node (ref "C239") (pin "1") (pinfunction "1_1") (pintype "passive"))
      (node (ref "C240") (pin "1") (pinfunction "1_1") (pintype "passive"))
      (node (ref "C241") (pin "1") (pinfunction "1_1") (pintype "passive"))
      (node (ref "C242") (pin "1") (pinfunction "1_1") (pintype "passive"))
      (node (ref "C243") (pin "1") (pinfunction "1_1") (pintype "passive"))
      (node (ref "C244") (pin "1") (pinfunction "1_1") (pintype "passive"))
      (node (ref "C245") (pin "1") (pinfunction "1_1") (pintype "passive"))
      (node (ref "C246") (pin "1") (pinfunction "1_1") (pintype "passive"))
      (node (ref "C247") (pin "1") (pinfunction "1_1") (pintype "passive"))
      (node (ref "C256") (pin "1") (pinfunction "1_1") (pintype "passive"))
      (node (ref "C257") (pin "1") (pinfunction "1_1") (pintype "passive"))
      (node (ref "C258") (pin "1") (pinfunction "1_1") (pintype "passive"))
      (node (ref "C259") (pin "1") (pinfunction "1_1") (pintype "passive"))
      (node (ref "C260") (pin "1") (pinfunction "1_1") (pintype "passive"))
      (node (ref "C261") (pin "1") (pinfunction "1_1") (pintype "passive"))
      (node (ref "C262") (pin "1") (pinfunction "1_1") (pintype "passive"))
      (node (ref "C271") (pin "1") (pinfunction "1_1") (pintype "passive"))
      (node (ref "C282") (pin "1") (pinfunction "1_1") (pintype "passive"))
      (node (ref "C283") (pin "1") (pinfunction "1_1") (pintype "passive"))
      (node (ref "C284") (pin "1") (pinfunction "1_1") (pintype "passive"))
      (node (ref "C285") (pin "1") (pinfunction "1_1") (pintype "passive"))
      (node (ref "C286") (pin "1") (pinfunction "1_1") (pintype "passive"))
      (node (ref "C287") (pin "1") (pinfunction "1_1") (pintype "passive"))
      (node (ref "C288") (pin "1") (pinfunction "1_1") (pintype "passive"))
      (node (ref "C289") (pin "1") (pinfunction "1_1") (pintype "passive"))
      (node (ref "C290") (pin "1") (pinfunction "1_1") (pintype "passive"))
      (node (ref "C291") (pin "1") (pinfunction "1_1") (pintype "passive"))
      (node (ref "C292") (pin "1") (pinfunction "1_1") (pintype "passive"))
      (node (ref "C293") (pin "1") (pinfunction "1_1") (pintype "passive"))
      (node (ref "C294") (pin "1") (pinfunction "1_1") (pintype "passive"))
      (node (ref "C295") (pin "1") (pinfunction "1_1") (pintype "passive"))
      (node (ref "C296") (pin "1") (pinfunction "1_1") (pintype "passive"))
      (node (ref "C297") (pin "1") (pinfunction "1_1") (pintype "passive"))
      (node (ref "C298") (pin "1") (pinfunction "1_1") (pintype "passive"))
      (node (ref "C299") (pin "1") (pinfunction "1_1") (pintype "passive"))
      (node (ref "C2_1") (pin "1") (pinfunction "1_1") (pintype "passive"))
      (node (ref "C2_10") (pin "1") (pinfunction "1_1") (pintype "passive"))
      (node (ref "C2_11") (pin "1") (pinfunction "1_1") (pintype "passive"))
      (node (ref "C2_12") (pin "1") (pinfunction "1_1") (pintype "passive"))
      (node (ref "C2_13") (pin "1") (pinfunction "1_1") (pintype "passive"))
      (node (ref "C2_14") (pin "1") (pinfunction "1_1") (pintype "passive"))
      (node (ref "C2_15") (pin "1") (pinfunction "1_1") (pintype "passive"))
      (node (ref "C2_16") (pin "1") (pinfunction "1_1") (pintype "passive"))
      (node (ref "C2_2") (pin "1") (pinfunction "1_1") (pintype "passive"))
      (node (ref "C2_3") (pin "1") (pinfunction "1_1") (pintype "passive"))
      (node (ref "C2_4") (pin "1") (pinfunction "1_1") (pintype "passive"))
      (node (ref "C2_5") (pin "1") (pinfunction "1_1") (pintype "passive"))
      (node (ref "C2_6") (pin "1") (pinfunction "1_1") (pintype "passive"))
      (node (ref "C2_7") (pin "1") (pinfunction "1_1") (pintype "passive"))
      (node (ref "C2_8") (pin "1") (pinfunction "1_1") (pintype "passive"))
      (node (ref "C2_9") (pin "1") (pinfunction "1_1") (pintype "passive"))
      (node (ref "C300") (pin "1") (pinfunction "1_1") (pintype "passive"))
      (node (ref "C301") (pin "1") (pinfunction "1_1") (pintype "passive"))
      (node (ref "C302") (pin "1") (pinfunction "1_1") (pintype "passive"))
      (node (ref "C303") (pin "1") (pinfunction "1_1") (pintype "passive"))
      (node (ref "C304") (pin "1") (pinfunction "1_1") (pintype "passive"))
      (node (ref "C305") (pin "1") (pinfunction "1_1") (pintype "passive"))
      (node (ref "C306") (pin "1") (pinfunction "1_1") (pintype "passive"))
      (node (ref "C307") (pin "1") (pinfunction "1_1") (pintype "passive"))
      (node (ref "C309") (pin "1") (pinfunction "1_1") (pintype "passive"))
      (node (ref "C313") (pin "1") (pinfunction "1_1") (pintype "passive"))
      (node (ref "C314") (pin "1") (pinfunction "1_1") (pintype "passive"))
      (node (ref "C315") (pin "1") (pinfunction "1_1") (pintype "passive"))
      (node (ref "C316") (pin "1") (pinfunction "1_1") (pintype "passive"))
      (node (ref "C317") (pin "1") (pinfunction "1_1") (pintype "passive"))
      (node (ref "C318") (pin "1") (pinfunction "1_1") (pintype "passive"))
      (node (ref "C319") (pin "1") (pinfunction "1_1") (pintype "passive"))
      (node (ref "C320") (pin "1") (pinfunction "1_1") (pintype "passive"))
      (node (ref "C321") (pin "1") (pinfunction "1_1") (pintype "passive"))
      (node (ref "C322") (pin "1") (pinfunction "1_1") (pintype "passive"))
      (node (ref "C323") (pin "1") (pinfunction "1_1") (pintype "passive"))
      (node (ref "C324") (pin "1") (pinfunction "1_1") (pintype "passive"))
      (node (ref "C3_1") (pin "1") (pinfunction "1_1") (pintype "passive"))
      (node (ref "C3_10") (pin "1") (pinfunction "1_1") (pintype "passive"))
      (node (ref "C3_11") (pin "1") (pinfunction "1_1") (pintype "passive"))
      (node (ref "C3_12") (pin "1") (pinfunction "1_1") (pintype "passive"))
      (node (ref "C3_13") (pin "1") (pinfunction "1_1") (pintype "passive"))
      (node (ref "C3_14") (pin "1") (pinfunction "1_1") (pintype "passive"))
      (node (ref "C3_15") (pin "1") (pinfunction "1_1") (pintype "passive"))
      (node (ref "C3_16") (pin "1") (pinfunction "1_1") (pintype "passive"))
      (node (ref "C3_2") (pin "1") (pinfunction "1_1") (pintype "passive"))
      (node (ref "C3_3") (pin "1") (pinfunction "1_1") (pintype "passive"))
      (node (ref "C3_4") (pin "1") (pinfunction "1_1") (pintype "passive"))
      (node (ref "C3_5") (pin "1") (pinfunction "1_1") (pintype "passive"))
      (node (ref "C3_6") (pin "1") (pinfunction "1_1") (pintype "passive"))
      (node (ref "C3_7") (pin "1") (pinfunction "1_1") (pintype "passive"))
      (node (ref "C3_8") (pin "1") (pinfunction "1_1") (pintype "passive"))
      (node (ref "C3_9") (pin "1") (pinfunction "1_1") (pintype "passive"))
      (node (ref "C4_1") (pin "1") (pinfunction "1_1") (pintype "passive"))
      (node (ref "C4_10") (pin "1") (pinfunction "1_1") (pintype "passive"))
      (node (ref "C4_11") (pin "1") (pinfunction "1_1") (pintype "passive"))
      (node (ref "C4_12") (pin "1") (pinfunction "1_1") (pintype "passive"))
      (node (ref "C4_13") (pin "1") (pinfunction "1_1") (pintype "passive"))
      (node (ref "C4_14") (pin "1") (pinfunction "1_1") (pintype "passive"))
      (node (ref "C4_15") (pin "1") (pinfunction "1_1") (pintype "passive"))
      (node (ref "C4_16") (pin "1") (pinfunction "1_1") (pintype "passive"))
      (node (ref "C4_2") (pin "1") (pinfunction "1_1") (pintype "passive"))
      (node (ref "C4_3") (pin "1") (pinfunction "1_1") (pintype "passive"))
      (node (ref "C4_4") (pin "1") (pinfunction "1_1") (pintype "passive"))
      (node (ref "C4_5") (pin "1") (pinfunction "1_1") (pintype "passive"))
      (node (ref "C4_6") (pin "1") (pinfunction "1_1") (pintype "passive"))
      (node (ref "C4_7") (pin "1") (pinfunction "1_1") (pintype "passive"))
      (node (ref "C4_8") (pin "1") (pinfunction "1_1") (pintype "passive"))
      (node (ref "C4_9") (pin "1") (pinfunction "1_1") (pintype "passive"))
      (node (ref "C6_1") (pin "1") (pinfunction "1_1") (pintype "passive"))
      (node (ref "C6_10") (pin "1") (pinfunction "1_1") (pintype "passive"))
      (node (ref "C6_11") (pin "1") (pinfunction "1_1") (pintype "passive"))
      (node (ref "C6_12") (pin "1") (pinfunction "1_1") (pintype "passive"))
      (node (ref "C6_13") (pin "1") (pinfunction "1_1") (pintype "passive"))
      (node (ref "C6_14") (pin "1") (pinfunction "1_1") (pintype "passive"))
      (node (ref "C6_15") (pin "1") (pinfunction "1_1") (pintype "passive"))
      (node (ref "C6_16") (pin "1") (pinfunction "1_1") (pintype "passive"))
      (node (ref "C6_2") (pin "1") (pinfunction "1_1") (pintype "passive"))
      (node (ref "C6_3") (pin "1") (pinfunction "1_1") (pintype "passive"))
      (node (ref "C6_4") (pin "1") (pinfunction "1_1") (pintype "passive"))
      (node (ref "C6_5") (pin "1") (pinfunction "1_1") (pintype "passive"))
      (node (ref "C6_6") (pin "1") (pinfunction "1_1") (pintype "passive"))
      (node (ref "C6_7") (pin "1") (pinfunction "1_1") (pintype "passive"))
      (node (ref "C6_8") (pin "1") (pinfunction "1_1") (pintype "passive"))
      (node (ref "C6_9") (pin "1") (pinfunction "1_1") (pintype "passive"))
      (node (ref "C7_1") (pin "1") (pinfunction "1_1") (pintype "passive"))
      (node (ref "C7_10") (pin "1") (pinfunction "1_1") (pintype "passive"))
      (node (ref "C7_11") (pin "1") (pinfunction "1_1") (pintype "passive"))
      (node (ref "C7_12") (pin "1") (pinfunction "1_1") (pintype "passive"))
      (node (ref "C7_13") (pin "1") (pinfunction "1_1") (pintype "passive"))
      (node (ref "C7_14") (pin "1") (pinfunction "1_1") (pintype "passive"))
      (node (ref "C7_15") (pin "1") (pinfunction "1_1") (pintype "passive"))
      (node (ref "C7_16") (pin "1") (pinfunction "1_1") (pintype "passive"))
      (node (ref "C7_2") (pin "1") (pinfunction "1_1") (pintype "passive"))
      (node (ref "C7_3") (pin "1") (pinfunction "1_1") (pintype "passive"))
      (node (ref "C7_4") (pin "1") (pinfunction "1_1") (pintype "passive"))
      (node (ref "C7_5") (pin "1") (pinfunction "1_1") (pintype "passive"))
      (node (ref "C7_6") (pin "1") (pinfunction "1_1") (pintype "passive"))
      (node (ref "C7_7") (pin "1") (pinfunction "1_1") (pintype "passive"))
      (node (ref "C7_8") (pin "1") (pinfunction "1_1") (pintype "passive"))
      (node (ref "C7_9") (pin "1") (pinfunction "1_1") (pintype "passive"))
      (node (ref "C9_1") (pin "1") (pinfunction "1_1") (pintype "passive"))
      (node (ref "C9_10") (pin "1") (pinfunction "1_1") (pintype "passive"))
      (node (ref "C9_11") (pin "1") (pinfunction "1_1") (pintype "passive"))
      (node (ref "C9_12") (pin "1") (pinfunction "1_1") (pintype "passive"))
      (node (ref "C9_13") (pin "1") (pinfunction "1_1") (pintype "passive"))
      (node (ref "C9_14") (pin "1") (pinfunction "1_1") (pintype "passive"))
      (node (ref "C9_15") (pin "1") (pinfunction "1_1") (pintype "passive"))
      (node (ref "C9_16") (pin "1") (pinfunction "1_1") (pintype "passive"))
      (node (ref "C9_2") (pin "1") (pinfunction "1_1") (pintype "passive"))
      (node (ref "C9_3") (pin "1") (pinfunction "1_1") (pintype "passive"))
      (node (ref "C9_4") (pin "1") (pinfunction "1_1") (pintype "passive"))
      (node (ref "C9_5") (pin "1") (pinfunction "1_1") (pintype "passive"))
      (node (ref "C9_6") (pin "1") (pinfunction "1_1") (pintype "passive"))
      (node (ref "C9_7") (pin "1") (pinfunction "1_1") (pintype "passive"))
      (node (ref "C9_8") (pin "1") (pinfunction "1_1") (pintype "passive"))
      (node (ref "C9_9") (pin "1") (pinfunction "1_1") (pintype "passive"))
      (node (ref "L1") (pin "2") (pinfunction "2_2") (pintype "passive"))
      (node (ref "L2") (pin "2") (pinfunction "2_2") (pintype "passive"))
      (node (ref "R38") (pin "2") (pinfunction "2_2") (pintype "passive"))
      (node (ref "R43") (pin "2") (pinfunction "2_2") (pintype "passive"))
      (node (ref "U1_1") (pin "10") (pinfunction "DVDD_10") (pintype "passive"))
      (node (ref "U1_1") (pin "11") (pinfunction "DVDD_11") (pintype "passive"))
      (node (ref "U1_1") (pin "13") (pinfunction "DVDD_13") (pintype "passive"))
      (node (ref "U1_1") (pin "14") (pinfunction "DVDD_14") (pintype "passive"))
      (node (ref "U1_1") (pin "15") (pinfunction "DVDD_15") (pintype "passive"))
      (node (ref "U1_1") (pin "18") (pinfunction "DVDD_18") (pintype "passive"))
      (node (ref "U1_1") (pin "19") (pinfunction "DVDD_19") (pintype "passive"))
      (node (ref "U1_1") (pin "20") (pinfunction "DVDD_20") (pintype "passive"))
      (node (ref "U1_1") (pin "21") (pinfunction "DVDD_21") (pintype "passive"))
      (node (ref "U1_1") (pin "22") (pinfunction "DVDD_22") (pintype "passive"))
      (node (ref "U1_1") (pin "25") (pinfunction "DVDD_25") (pintype "passive"))
      (node (ref "U1_1") (pin "26") (pinfunction "DVDD_26") (pintype "passive"))
      (node (ref "U1_1") (pin "28") (pinfunction "DVDD_28") (pintype "passive"))
      (node (ref "U1_1") (pin "29") (pinfunction "DVDD_29") (pintype "passive"))
      (node (ref "U1_1") (pin "3") (pinfunction "DVDD_3") (pintype "passive"))
      (node (ref "U1_1") (pin "30") (pinfunction "DVDD_30") (pintype "passive"))
      (node (ref "U1_1") (pin "31") (pinfunction "DVDD_31") (pintype "passive"))
      (node (ref "U1_1") (pin "32") (pinfunction "DVDD_32") (pintype "passive"))
      (node (ref "U1_1") (pin "33") (pinfunction "DVDD_33") (pintype "passive"))
      (node (ref "U1_1") (pin "34") (pinfunction "DVDD_34") (pintype "passive"))
      (node (ref "U1_1") (pin "39") (pinfunction "DVDD_39") (pintype "passive"))
      (node (ref "U1_1") (pin "4") (pinfunction "DVDD_4") (pintype "passive"))
      (node (ref "U1_1") (pin "40") (pinfunction "DVDD_40") (pintype "passive"))
      (node (ref "U1_1") (pin "41") (pinfunction "DVDD_41") (pintype "passive"))
      (node (ref "U1_1") (pin "42") (pinfunction "DVDD_42") (pintype "passive"))
      (node (ref "U1_1") (pin "45") (pinfunction "DVDD_45") (pintype "passive"))
      (node (ref "U1_1") (pin "46") (pinfunction "DVDD_46") (pintype "passive"))
      (node (ref "U1_1") (pin "47") (pinfunction "DVDD_47") (pintype "passive"))
      (node (ref "U1_1") (pin "48") (pinfunction "DVDD_48") (pintype "passive"))
      (node (ref "U1_1") (pin "6") (pinfunction "VDDA_PLL_6") (pintype "passive"))
      (node (ref "U1_1") (pin "7") (pinfunction "VDD_PLL_7") (pintype "passive"))
      (node (ref "U1_10") (pin "10") (pinfunction "DVDD_10") (pintype "passive"))
      (node (ref "U1_10") (pin "11") (pinfunction "DVDD_11") (pintype "passive"))
      (node (ref "U1_10") (pin "13") (pinfunction "DVDD_13") (pintype "passive"))
      (node (ref "U1_10") (pin "14") (pinfunction "DVDD_14") (pintype "passive"))
      (node (ref "U1_10") (pin "15") (pinfunction "DVDD_15") (pintype "passive"))
      (node (ref "U1_10") (pin "18") (pinfunction "DVDD_18") (pintype "passive"))
      (node (ref "U1_10") (pin "19") (pinfunction "DVDD_19") (pintype "passive"))
      (node (ref "U1_10") (pin "20") (pinfunction "DVDD_20") (pintype "passive"))
      (node (ref "U1_10") (pin "21") (pinfunction "DVDD_21") (pintype "passive"))
      (node (ref "U1_10") (pin "22") (pinfunction "DVDD_22") (pintype "passive"))
      (node (ref "U1_10") (pin "25") (pinfunction "DVDD_25") (pintype "passive"))
      (node (ref "U1_10") (pin "26") (pinfunction "DVDD_26") (pintype "passive"))
      (node (ref "U1_10") (pin "28") (pinfunction "DVDD_28") (pintype "passive"))
      (node (ref "U1_10") (pin "29") (pinfunction "DVDD_29") (pintype "passive"))
      (node (ref "U1_10") (pin "3") (pinfunction "DVDD_3") (pintype "passive"))
      (node (ref "U1_10") (pin "30") (pinfunction "DVDD_30") (pintype "passive"))
      (node (ref "U1_10") (pin "31") (pinfunction "DVDD_31") (pintype "passive"))
      (node (ref "U1_10") (pin "32") (pinfunction "DVDD_32") (pintype "passive"))
      (node (ref "U1_10") (pin "33") (pinfunction "DVDD_33") (pintype "passive"))
      (node (ref "U1_10") (pin "34") (pinfunction "DVDD_34") (pintype "passive"))
      (node (ref "U1_10") (pin "39") (pinfunction "DVDD_39") (pintype "passive"))
      (node (ref "U1_10") (pin "4") (pinfunction "DVDD_4") (pintype "passive"))
      (node (ref "U1_10") (pin "40") (pinfunction "DVDD_40") (pintype "passive"))
      (node (ref "U1_10") (pin "41") (pinfunction "DVDD_41") (pintype "passive"))
      (node (ref "U1_10") (pin "42") (pinfunction "DVDD_42") (pintype "passive"))
      (node (ref "U1_10") (pin "45") (pinfunction "DVDD_45") (pintype "passive"))
      (node (ref "U1_10") (pin "46") (pinfunction "DVDD_46") (pintype "passive"))
      (node (ref "U1_10") (pin "47") (pinfunction "DVDD_47") (pintype "passive"))
      (node (ref "U1_10") (pin "48") (pinfunction "DVDD_48") (pintype "passive"))
      (node (ref "U1_10") (pin "6") (pinfunction "VDDA_PLL_6") (pintype "passive"))
      (node (ref "U1_10") (pin "7") (pinfunction "VDD_PLL_7") (pintype "passive"))
      (node (ref "U1_11") (pin "10") (pinfunction "DVDD_10") (pintype "passive"))
      (node (ref "U1_11") (pin "11") (pinfunction "DVDD_11") (pintype "passive"))
      (node (ref "U1_11") (pin "13") (pinfunction "DVDD_13") (pintype "passive"))
      (node (ref "U1_11") (pin "14") (pinfunction "DVDD_14") (pintype "passive"))
      (node (ref "U1_11") (pin "15") (pinfunction "DVDD_15") (pintype "passive"))
      (node (ref "U1_11") (pin "18") (pinfunction "DVDD_18") (pintype "passive"))
      (node (ref "U1_11") (pin "19") (pinfunction "DVDD_19") (pintype "passive"))
      (node (ref "U1_11") (pin "20") (pinfunction "DVDD_20") (pintype "passive"))
      (node (ref "U1_11") (pin "21") (pinfunction "DVDD_21") (pintype "passive"))
      (node (ref "U1_11") (pin "22") (pinfunction "DVDD_22") (pintype "passive"))
      (node (ref "U1_11") (pin "25") (pinfunction "DVDD_25") (pintype "passive"))
      (node (ref "U1_11") (pin "26") (pinfunction "DVDD_26") (pintype "passive"))
      (node (ref "U1_11") (pin "28") (pinfunction "DVDD_28") (pintype "passive"))
      (node (ref "U1_11") (pin "29") (pinfunction "DVDD_29") (pintype "passive"))
      (node (ref "U1_11") (pin "3") (pinfunction "DVDD_3") (pintype "passive"))
      (node (ref "U1_11") (pin "30") (pinfunction "DVDD_30") (pintype "passive"))
      (node (ref "U1_11") (pin "31") (pinfunction "DVDD_31") (pintype "passive"))
      (node (ref "U1_11") (pin "32") (pinfunction "DVDD_32") (pintype "passive"))
      (node (ref "U1_11") (pin "33") (pinfunction "DVDD_33") (pintype "passive"))
      (node (ref "U1_11") (pin "34") (pinfunction "DVDD_34") (pintype "passive"))
      (node (ref "U1_11") (pin "39") (pinfunction "DVDD_39") (pintype "passive"))
      (node (ref "U1_11") (pin "4") (pinfunction "DVDD_4") (pintype "passive"))
      (node (ref "U1_11") (pin "40") (pinfunction "DVDD_40") (pintype "passive"))
      (node (ref "U1_11") (pin "41") (pinfunction "DVDD_41") (pintype "passive"))
      (node (ref "U1_11") (pin "42") (pinfunction "DVDD_42") (pintype "passive"))
      (node (ref "U1_11") (pin "45") (pinfunction "DVDD_45") (pintype "passive"))
      (node (ref "U1_11") (pin "46") (pinfunction "DVDD_46") (pintype "passive"))
      (node (ref "U1_11") (pin "47") (pinfunction "DVDD_47") (pintype "passive"))
      (node (ref "U1_11") (pin "48") (pinfunction "DVDD_48") (pintype "passive"))
      (node (ref "U1_11") (pin "6") (pinfunction "VDDA_PLL_6") (pintype "passive"))
      (node (ref "U1_11") (pin "7") (pinfunction "VDD_PLL_7") (pintype "passive"))
      (node (ref "U1_12") (pin "10") (pinfunction "DVDD_10") (pintype "passive"))
      (node (ref "U1_12") (pin "11") (pinfunction "DVDD_11") (pintype "passive"))
      (node (ref "U1_12") (pin "13") (pinfunction "DVDD_13") (pintype "passive"))
      (node (ref "U1_12") (pin "14") (pinfunction "DVDD_14") (pintype "passive"))
      (node (ref "U1_12") (pin "15") (pinfunction "DVDD_15") (pintype "passive"))
      (node (ref "U1_12") (pin "18") (pinfunction "DVDD_18") (pintype "passive"))
      (node (ref "U1_12") (pin "19") (pinfunction "DVDD_19") (pintype "passive"))
      (node (ref "U1_12") (pin "20") (pinfunction "DVDD_20") (pintype "passive"))
      (node (ref "U1_12") (pin "21") (pinfunction "DVDD_21") (pintype "passive"))
      (node (ref "U1_12") (pin "22") (pinfunction "DVDD_22") (pintype "passive"))
      (node (ref "U1_12") (pin "25") (pinfunction "DVDD_25") (pintype "passive"))
      (node (ref "U1_12") (pin "26") (pinfunction "DVDD_26") (pintype "passive"))
      (node (ref "U1_12") (pin "28") (pinfunction "DVDD_28") (pintype "passive"))
      (node (ref "U1_12") (pin "29") (pinfunction "DVDD_29") (pintype "passive"))
      (node (ref "U1_12") (pin "3") (pinfunction "DVDD_3") (pintype "passive"))
      (node (ref "U1_12") (pin "30") (pinfunction "DVDD_30") (pintype "passive"))
      (node (ref "U1_12") (pin "31") (pinfunction "DVDD_31") (pintype "passive"))
      (node (ref "U1_12") (pin "32") (pinfunction "DVDD_32") (pintype "passive"))
      (node (ref "U1_12") (pin "33") (pinfunction "DVDD_33") (pintype "passive"))
      (node (ref "U1_12") (pin "34") (pinfunction "DVDD_34") (pintype "passive"))
      (node (ref "U1_12") (pin "39") (pinfunction "DVDD_39") (pintype "passive"))
      (node (ref "U1_12") (pin "4") (pinfunction "DVDD_4") (pintype "passive"))
      (node (ref "U1_12") (pin "40") (pinfunction "DVDD_40") (pintype "passive"))
      (node (ref "U1_12") (pin "41") (pinfunction "DVDD_41") (pintype "passive"))
      (node (ref "U1_12") (pin "42") (pinfunction "DVDD_42") (pintype "passive"))
      (node (ref "U1_12") (pin "45") (pinfunction "DVDD_45") (pintype "passive"))
      (node (ref "U1_12") (pin "46") (pinfunction "DVDD_46") (pintype "passive"))
      (node (ref "U1_12") (pin "47") (pinfunction "DVDD_47") (pintype "passive"))
      (node (ref "U1_12") (pin "48") (pinfunction "DVDD_48") (pintype "passive"))
      (node (ref "U1_12") (pin "6") (pinfunction "VDDA_PLL_6") (pintype "passive"))
      (node (ref "U1_12") (pin "7") (pinfunction "VDD_PLL_7") (pintype "passive"))
      (node (ref "U1_13") (pin "10") (pinfunction "DVDD_10") (pintype "passive"))
      (node (ref "U1_13") (pin "11") (pinfunction "DVDD_11") (pintype "passive"))
      (node (ref "U1_13") (pin "13") (pinfunction "DVDD_13") (pintype "passive"))
      (node (ref "U1_13") (pin "14") (pinfunction "DVDD_14") (pintype "passive"))
      (node (ref "U1_13") (pin "15") (pinfunction "DVDD_15") (pintype "passive"))
      (node (ref "U1_13") (pin "18") (pinfunction "DVDD_18") (pintype "passive"))
      (node (ref "U1_13") (pin "19") (pinfunction "DVDD_19") (pintype "passive"))
      (node (ref "U1_13") (pin "20") (pinfunction "DVDD_20") (pintype "passive"))
      (node (ref "U1_13") (pin "21") (pinfunction "DVDD_21") (pintype "passive"))
      (node (ref "U1_13") (pin "22") (pinfunction "DVDD_22") (pintype "passive"))
      (node (ref "U1_13") (pin "25") (pinfunction "DVDD_25") (pintype "passive"))
      (node (ref "U1_13") (pin "26") (pinfunction "DVDD_26") (pintype "passive"))
      (node (ref "U1_13") (pin "28") (pinfunction "DVDD_28") (pintype "passive"))
      (node (ref "U1_13") (pin "29") (pinfunction "DVDD_29") (pintype "passive"))
      (node (ref "U1_13") (pin "3") (pinfunction "DVDD_3") (pintype "passive"))
      (node (ref "U1_13") (pin "30") (pinfunction "DVDD_30") (pintype "passive"))
      (node (ref "U1_13") (pin "31") (pinfunction "DVDD_31") (pintype "passive"))
      (node (ref "U1_13") (pin "32") (pinfunction "DVDD_32") (pintype "passive"))
      (node (ref "U1_13") (pin "33") (pinfunction "DVDD_33") (pintype "passive"))
      (node (ref "U1_13") (pin "34") (pinfunction "DVDD_34") (pintype "passive"))
      (node (ref "U1_13") (pin "39") (pinfunction "DVDD_39") (pintype "passive"))
      (node (ref "U1_13") (pin "4") (pinfunction "DVDD_4") (pintype "passive"))
      (node (ref "U1_13") (pin "40") (pinfunction "DVDD_40") (pintype "passive"))
      (node (ref "U1_13") (pin "41") (pinfunction "DVDD_41") (pintype "passive"))
      (node (ref "U1_13") (pin "42") (pinfunction "DVDD_42") (pintype "passive"))
      (node (ref "U1_13") (pin "45") (pinfunction "DVDD_45") (pintype "passive"))
      (node (ref "U1_13") (pin "46") (pinfunction "DVDD_46") (pintype "passive"))
      (node (ref "U1_13") (pin "47") (pinfunction "DVDD_47") (pintype "passive"))
      (node (ref "U1_13") (pin "48") (pinfunction "DVDD_48") (pintype "passive"))
      (node (ref "U1_13") (pin "6") (pinfunction "VDDA_PLL_6") (pintype "passive"))
      (node (ref "U1_13") (pin "7") (pinfunction "VDD_PLL_7") (pintype "passive"))
      (node (ref "U1_14") (pin "10") (pinfunction "DVDD_10") (pintype "passive"))
      (node (ref "U1_14") (pin "11") (pinfunction "DVDD_11") (pintype "passive"))
      (node (ref "U1_14") (pin "13") (pinfunction "DVDD_13") (pintype "passive"))
      (node (ref "U1_14") (pin "14") (pinfunction "DVDD_14") (pintype "passive"))
      (node (ref "U1_14") (pin "15") (pinfunction "DVDD_15") (pintype "passive"))
      (node (ref "U1_14") (pin "18") (pinfunction "DVDD_18") (pintype "passive"))
      (node (ref "U1_14") (pin "19") (pinfunction "DVDD_19") (pintype "passive"))
      (node (ref "U1_14") (pin "20") (pinfunction "DVDD_20") (pintype "passive"))
      (node (ref "U1_14") (pin "21") (pinfunction "DVDD_21") (pintype "passive"))
      (node (ref "U1_14") (pin "22") (pinfunction "DVDD_22") (pintype "passive"))
      (node (ref "U1_14") (pin "25") (pinfunction "DVDD_25") (pintype "passive"))
      (node (ref "U1_14") (pin "26") (pinfunction "DVDD_26") (pintype "passive"))
      (node (ref "U1_14") (pin "28") (pinfunction "DVDD_28") (pintype "passive"))
      (node (ref "U1_14") (pin "29") (pinfunction "DVDD_29") (pintype "passive"))
      (node (ref "U1_14") (pin "3") (pinfunction "DVDD_3") (pintype "passive"))
      (node (ref "U1_14") (pin "30") (pinfunction "DVDD_30") (pintype "passive"))
      (node (ref "U1_14") (pin "31") (pinfunction "DVDD_31") (pintype "passive"))
      (node (ref "U1_14") (pin "32") (pinfunction "DVDD_32") (pintype "passive"))
      (node (ref "U1_14") (pin "33") (pinfunction "DVDD_33") (pintype "passive"))
      (node (ref "U1_14") (pin "34") (pinfunction "DVDD_34") (pintype "passive"))
      (node (ref "U1_14") (pin "39") (pinfunction "DVDD_39") (pintype "passive"))
      (node (ref "U1_14") (pin "4") (pinfunction "DVDD_4") (pintype "passive"))
      (node (ref "U1_14") (pin "40") (pinfunction "DVDD_40") (pintype "passive"))
      (node (ref "U1_14") (pin "41") (pinfunction "DVDD_41") (pintype "passive"))
      (node (ref "U1_14") (pin "42") (pinfunction "DVDD_42") (pintype "passive"))
      (node (ref "U1_14") (pin "45") (pinfunction "DVDD_45") (pintype "passive"))
      (node (ref "U1_14") (pin "46") (pinfunction "DVDD_46") (pintype "passive"))
      (node (ref "U1_14") (pin "47") (pinfunction "DVDD_47") (pintype "passive"))
      (node (ref "U1_14") (pin "48") (pinfunction "DVDD_48") (pintype "passive"))
      (node (ref "U1_14") (pin "6") (pinfunction "VDDA_PLL_6") (pintype "passive"))
      (node (ref "U1_14") (pin "7") (pinfunction "VDD_PLL_7") (pintype "passive"))
      (node (ref "U1_15") (pin "10") (pinfunction "DVDD_10") (pintype "passive"))
      (node (ref "U1_15") (pin "11") (pinfunction "DVDD_11") (pintype "passive"))
      (node (ref "U1_15") (pin "13") (pinfunction "DVDD_13") (pintype "passive"))
      (node (ref "U1_15") (pin "14") (pinfunction "DVDD_14") (pintype "passive"))
      (node (ref "U1_15") (pin "15") (pinfunction "DVDD_15") (pintype "passive"))
      (node (ref "U1_15") (pin "18") (pinfunction "DVDD_18") (pintype "passive"))
      (node (ref "U1_15") (pin "19") (pinfunction "DVDD_19") (pintype "passive"))
      (node (ref "U1_15") (pin "20") (pinfunction "DVDD_20") (pintype "passive"))
      (node (ref "U1_15") (pin "21") (pinfunction "DVDD_21") (pintype "passive"))
      (node (ref "U1_15") (pin "22") (pinfunction "DVDD_22") (pintype "passive"))
      (node (ref "U1_15") (pin "25") (pinfunction "DVDD_25") (pintype "passive"))
      (node (ref "U1_15") (pin "26") (pinfunction "DVDD_26") (pintype "passive"))
      (node (ref "U1_15") (pin "28") (pinfunction "DVDD_28") (pintype "passive"))
      (node (ref "U1_15") (pin "29") (pinfunction "DVDD_29") (pintype "passive"))
      (node (ref "U1_15") (pin "3") (pinfunction "DVDD_3") (pintype "passive"))
      (node (ref "U1_15") (pin "30") (pinfunction "DVDD_30") (pintype "passive"))
      (node (ref "U1_15") (pin "31") (pinfunction "DVDD_31") (pintype "passive"))
      (node (ref "U1_15") (pin "32") (pinfunction "DVDD_32") (pintype "passive"))
      (node (ref "U1_15") (pin "33") (pinfunction "DVDD_33") (pintype "passive"))
      (node (ref "U1_15") (pin "34") (pinfunction "DVDD_34") (pintype "passive"))
      (node (ref "U1_15") (pin "39") (pinfunction "DVDD_39") (pintype "passive"))
      (node (ref "U1_15") (pin "4") (pinfunction "DVDD_4") (pintype "passive"))
      (node (ref "U1_15") (pin "40") (pinfunction "DVDD_40") (pintype "passive"))
      (node (ref "U1_15") (pin "41") (pinfunction "DVDD_41") (pintype "passive"))
      (node (ref "U1_15") (pin "42") (pinfunction "DVDD_42") (pintype "passive"))
      (node (ref "U1_15") (pin "45") (pinfunction "DVDD_45") (pintype "passive"))
      (node (ref "U1_15") (pin "46") (pinfunction "DVDD_46") (pintype "passive"))
      (node (ref "U1_15") (pin "47") (pinfunction "DVDD_47") (pintype "passive"))
      (node (ref "U1_15") (pin "48") (pinfunction "DVDD_48") (pintype "passive"))
      (node (ref "U1_15") (pin "6") (pinfunction "VDDA_PLL_6") (pintype "passive"))
      (node (ref "U1_15") (pin "7") (pinfunction "VDD_PLL_7") (pintype "passive"))
      (node (ref "U1_16") (pin "10") (pinfunction "DVDD_10") (pintype "passive"))
      (node (ref "U1_16") (pin "11") (pinfunction "DVDD_11") (pintype "passive"))
      (node (ref "U1_16") (pin "13") (pinfunction "DVDD_13") (pintype "passive"))
      (node (ref "U1_16") (pin "14") (pinfunction "DVDD_14") (pintype "passive"))
      (node (ref "U1_16") (pin "15") (pinfunction "DVDD_15") (pintype "passive"))
      (node (ref "U1_16") (pin "18") (pinfunction "DVDD_18") (pintype "passive"))
      (node (ref "U1_16") (pin "19") (pinfunction "DVDD_19") (pintype "passive"))
      (node (ref "U1_16") (pin "20") (pinfunction "DVDD_20") (pintype "passive"))
      (node (ref "U1_16") (pin "21") (pinfunction "DVDD_21") (pintype "passive"))
      (node (ref "U1_16") (pin "22") (pinfunction "DVDD_22") (pintype "passive"))
      (node (ref "U1_16") (pin "25") (pinfunction "DVDD_25") (pintype "passive"))
      (node (ref "U1_16") (pin "26") (pinfunction "DVDD_26") (pintype "passive"))
      (node (ref "U1_16") (pin "28") (pinfunction "DVDD_28") (pintype "passive"))
      (node (ref "U1_16") (pin "29") (pinfunction "DVDD_29") (pintype "passive"))
      (node (ref "U1_16") (pin "3") (pinfunction "DVDD_3") (pintype "passive"))
      (node (ref "U1_16") (pin "30") (pinfunction "DVDD_30") (pintype "passive"))
      (node (ref "U1_16") (pin "31") (pinfunction "DVDD_31") (pintype "passive"))
      (node (ref "U1_16") (pin "32") (pinfunction "DVDD_32") (pintype "passive"))
      (node (ref "U1_16") (pin "33") (pinfunction "DVDD_33") (pintype "passive"))
      (node (ref "U1_16") (pin "34") (pinfunction "DVDD_34") (pintype "passive"))
      (node (ref "U1_16") (pin "39") (pinfunction "DVDD_39") (pintype "passive"))
      (node (ref "U1_16") (pin "4") (pinfunction "DVDD_4") (pintype "passive"))
      (node (ref "U1_16") (pin "40") (pinfunction "DVDD_40") (pintype "passive"))
      (node (ref "U1_16") (pin "41") (pinfunction "DVDD_41") (pintype "passive"))
      (node (ref "U1_16") (pin "42") (pinfunction "DVDD_42") (pintype "passive"))
      (node (ref "U1_16") (pin "45") (pinfunction "DVDD_45") (pintype "passive"))
      (node (ref "U1_16") (pin "46") (pinfunction "DVDD_46") (pintype "passive"))
      (node (ref "U1_16") (pin "47") (pinfunction "DVDD_47") (pintype "passive"))
      (node (ref "U1_16") (pin "48") (pinfunction "DVDD_48") (pintype "passive"))
      (node (ref "U1_16") (pin "6") (pinfunction "VDDA_PLL_6") (pintype "passive"))
      (node (ref "U1_16") (pin "7") (pinfunction "VDD_PLL_7") (pintype "passive"))
      (node (ref "U1_2") (pin "10") (pinfunction "DVDD_10") (pintype "passive"))
      (node (ref "U1_2") (pin "11") (pinfunction "DVDD_11") (pintype "passive"))
      (node (ref "U1_2") (pin "13") (pinfunction "DVDD_13") (pintype "passive"))
      (node (ref "U1_2") (pin "14") (pinfunction "DVDD_14") (pintype "passive"))
      (node (ref "U1_2") (pin "15") (pinfunction "DVDD_15") (pintype "passive"))
      (node (ref "U1_2") (pin "18") (pinfunction "DVDD_18") (pintype "passive"))
      (node (ref "U1_2") (pin "19") (pinfunction "DVDD_19") (pintype "passive"))
      (node (ref "U1_2") (pin "20") (pinfunction "DVDD_20") (pintype "passive"))
      (node (ref "U1_2") (pin "21") (pinfunction "DVDD_21") (pintype "passive"))
      (node (ref "U1_2") (pin "22") (pinfunction "DVDD_22") (pintype "passive"))
      (node (ref "U1_2") (pin "25") (pinfunction "DVDD_25") (pintype "passive"))
      (node (ref "U1_2") (pin "26") (pinfunction "DVDD_26") (pintype "passive"))
      (node (ref "U1_2") (pin "28") (pinfunction "DVDD_28") (pintype "passive"))
      (node (ref "U1_2") (pin "29") (pinfunction "DVDD_29") (pintype "passive"))
      (node (ref "U1_2") (pin "3") (pinfunction "DVDD_3") (pintype "passive"))
      (node (ref "U1_2") (pin "30") (pinfunction "DVDD_30") (pintype "passive"))
      (node (ref "U1_2") (pin "31") (pinfunction "DVDD_31") (pintype "passive"))
      (node (ref "U1_2") (pin "32") (pinfunction "DVDD_32") (pintype "passive"))
      (node (ref "U1_2") (pin "33") (pinfunction "DVDD_33") (pintype "passive"))
      (node (ref "U1_2") (pin "34") (pinfunction "DVDD_34") (pintype "passive"))
      (node (ref "U1_2") (pin "39") (pinfunction "DVDD_39") (pintype "passive"))
      (node (ref "U1_2") (pin "4") (pinfunction "DVDD_4") (pintype "passive"))
      (node (ref "U1_2") (pin "40") (pinfunction "DVDD_40") (pintype "passive"))
      (node (ref "U1_2") (pin "41") (pinfunction "DVDD_41") (pintype "passive"))
      (node (ref "U1_2") (pin "42") (pinfunction "DVDD_42") (pintype "passive"))
      (node (ref "U1_2") (pin "45") (pinfunction "DVDD_45") (pintype "passive"))
      (node (ref "U1_2") (pin "46") (pinfunction "DVDD_46") (pintype "passive"))
      (node (ref "U1_2") (pin "47") (pinfunction "DVDD_47") (pintype "passive"))
      (node (ref "U1_2") (pin "48") (pinfunction "DVDD_48") (pintype "passive"))
      (node (ref "U1_2") (pin "6") (pinfunction "VDDA_PLL_6") (pintype "passive"))
      (node (ref "U1_2") (pin "7") (pinfunction "VDD_PLL_7") (pintype "passive"))
      (node (ref "U1_3") (pin "10") (pinfunction "DVDD_10") (pintype "passive"))
      (node (ref "U1_3") (pin "11") (pinfunction "DVDD_11") (pintype "passive"))
      (node (ref "U1_3") (pin "13") (pinfunction "DVDD_13") (pintype "passive"))
      (node (ref "U1_3") (pin "14") (pinfunction "DVDD_14") (pintype "passive"))
      (node (ref "U1_3") (pin "15") (pinfunction "DVDD_15") (pintype "passive"))
      (node (ref "U1_3") (pin "18") (pinfunction "DVDD_18") (pintype "passive"))
      (node (ref "U1_3") (pin "19") (pinfunction "DVDD_19") (pintype "passive"))
      (node (ref "U1_3") (pin "20") (pinfunction "DVDD_20") (pintype "passive"))
      (node (ref "U1_3") (pin "21") (pinfunction "DVDD_21") (pintype "passive"))
      (node (ref "U1_3") (pin "22") (pinfunction "DVDD_22") (pintype "passive"))
      (node (ref "U1_3") (pin "25") (pinfunction "DVDD_25") (pintype "passive"))
      (node (ref "U1_3") (pin "26") (pinfunction "DVDD_26") (pintype "passive"))
      (node (ref "U1_3") (pin "28") (pinfunction "DVDD_28") (pintype "passive"))
      (node (ref "U1_3") (pin "29") (pinfunction "DVDD_29") (pintype "passive"))
      (node (ref "U1_3") (pin "3") (pinfunction "DVDD_3") (pintype "passive"))
      (node (ref "U1_3") (pin "30") (pinfunction "DVDD_30") (pintype "passive"))
      (node (ref "U1_3") (pin "31") (pinfunction "DVDD_31") (pintype "passive"))
      (node (ref "U1_3") (pin "32") (pinfunction "DVDD_32") (pintype "passive"))
      (node (ref "U1_3") (pin "33") (pinfunction "DVDD_33") (pintype "passive"))
      (node (ref "U1_3") (pin "34") (pinfunction "DVDD_34") (pintype "passive"))
      (node (ref "U1_3") (pin "39") (pinfunction "DVDD_39") (pintype "passive"))
      (node (ref "U1_3") (pin "4") (pinfunction "DVDD_4") (pintype "passive"))
      (node (ref "U1_3") (pin "40") (pinfunction "DVDD_40") (pintype "passive"))
      (node (ref "U1_3") (pin "41") (pinfunction "DVDD_41") (pintype "passive"))
      (node (ref "U1_3") (pin "42") (pinfunction "DVDD_42") (pintype "passive"))
      (node (ref "U1_3") (pin "45") (pinfunction "DVDD_45") (pintype "passive"))
      (node (ref "U1_3") (pin "46") (pinfunction "DVDD_46") (pintype "passive"))
      (node (ref "U1_3") (pin "47") (pinfunction "DVDD_47") (pintype "passive"))
      (node (ref "U1_3") (pin "48") (pinfunction "DVDD_48") (pintype "passive"))
      (node (ref "U1_3") (pin "6") (pinfunction "VDDA_PLL_6") (pintype "passive"))
      (node (ref "U1_3") (pin "7") (pinfunction "VDD_PLL_7") (pintype "passive"))
      (node (ref "U1_4") (pin "10") (pinfunction "DVDD_10") (pintype "passive"))
      (node (ref "U1_4") (pin "11") (pinfunction "DVDD_11") (pintype "passive"))
      (node (ref "U1_4") (pin "13") (pinfunction "DVDD_13") (pintype "passive"))
      (node (ref "U1_4") (pin "14") (pinfunction "DVDD_14") (pintype "passive"))
      (node (ref "U1_4") (pin "15") (pinfunction "DVDD_15") (pintype "passive"))
      (node (ref "U1_4") (pin "18") (pinfunction "DVDD_18") (pintype "passive"))
      (node (ref "U1_4") (pin "19") (pinfunction "DVDD_19") (pintype "passive"))
      (node (ref "U1_4") (pin "20") (pinfunction "DVDD_20") (pintype "passive"))
      (node (ref "U1_4") (pin "21") (pinfunction "DVDD_21") (pintype "passive"))
      (node (ref "U1_4") (pin "22") (pinfunction "DVDD_22") (pintype "passive"))
      (node (ref "U1_4") (pin "25") (pinfunction "DVDD_25") (pintype "passive"))
      (node (ref "U1_4") (pin "26") (pinfunction "DVDD_26") (pintype "passive"))
      (node (ref "U1_4") (pin "28") (pinfunction "DVDD_28") (pintype "passive"))
      (node (ref "U1_4") (pin "29") (pinfunction "DVDD_29") (pintype "passive"))
      (node (ref "U1_4") (pin "3") (pinfunction "DVDD_3") (pintype "passive"))
      (node (ref "U1_4") (pin "30") (pinfunction "DVDD_30") (pintype "passive"))
      (node (ref "U1_4") (pin "31") (pinfunction "DVDD_31") (pintype "passive"))
      (node (ref "U1_4") (pin "32") (pinfunction "DVDD_32") (pintype "passive"))
      (node (ref "U1_4") (pin "33") (pinfunction "DVDD_33") (pintype "passive"))
      (node (ref "U1_4") (pin "34") (pinfunction "DVDD_34") (pintype "passive"))
      (node (ref "U1_4") (pin "39") (pinfunction "DVDD_39") (pintype "passive"))
      (node (ref "U1_4") (pin "4") (pinfunction "DVDD_4") (pintype "passive"))
      (node (ref "U1_4") (pin "40") (pinfunction "DVDD_40") (pintype "passive"))
      (node (ref "U1_4") (pin "41") (pinfunction "DVDD_41") (pintype "passive"))
      (node (ref "U1_4") (pin "42") (pinfunction "DVDD_42") (pintype "passive"))
      (node (ref "U1_4") (pin "45") (pinfunction "DVDD_45") (pintype "passive"))
      (node (ref "U1_4") (pin "46") (pinfunction "DVDD_46") (pintype "passive"))
      (node (ref "U1_4") (pin "47") (pinfunction "DVDD_47") (pintype "passive"))
      (node (ref "U1_4") (pin "48") (pinfunction "DVDD_48") (pintype "passive"))
      (node (ref "U1_4") (pin "6") (pinfunction "VDDA_PLL_6") (pintype "passive"))
      (node (ref "U1_4") (pin "7") (pinfunction "VDD_PLL_7") (pintype "passive"))
      (node (ref "U1_5") (pin "10") (pinfunction "DVDD_10") (pintype "passive"))
      (node (ref "U1_5") (pin "11") (pinfunction "DVDD_11") (pintype "passive"))
      (node (ref "U1_5") (pin "13") (pinfunction "DVDD_13") (pintype "passive"))
      (node (ref "U1_5") (pin "14") (pinfunction "DVDD_14") (pintype "passive"))
      (node (ref "U1_5") (pin "15") (pinfunction "DVDD_15") (pintype "passive"))
      (node (ref "U1_5") (pin "18") (pinfunction "DVDD_18") (pintype "passive"))
      (node (ref "U1_5") (pin "19") (pinfunction "DVDD_19") (pintype "passive"))
      (node (ref "U1_5") (pin "20") (pinfunction "DVDD_20") (pintype "passive"))
      (node (ref "U1_5") (pin "21") (pinfunction "DVDD_21") (pintype "passive"))
      (node (ref "U1_5") (pin "22") (pinfunction "DVDD_22") (pintype "passive"))
      (node (ref "U1_5") (pin "25") (pinfunction "DVDD_25") (pintype "passive"))
      (node (ref "U1_5") (pin "26") (pinfunction "DVDD_26") (pintype "passive"))
      (node (ref "U1_5") (pin "28") (pinfunction "DVDD_28") (pintype "passive"))
      (node (ref "U1_5") (pin "29") (pinfunction "DVDD_29") (pintype "passive"))
      (node (ref "U1_5") (pin "3") (pinfunction "DVDD_3") (pintype "passive"))
      (node (ref "U1_5") (pin "30") (pinfunction "DVDD_30") (pintype "passive"))
      (node (ref "U1_5") (pin "31") (pinfunction "DVDD_31") (pintype "passive"))
      (node (ref "U1_5") (pin "32") (pinfunction "DVDD_32") (pintype "passive"))
      (node (ref "U1_5") (pin "33") (pinfunction "DVDD_33") (pintype "passive"))
      (node (ref "U1_5") (pin "34") (pinfunction "DVDD_34") (pintype "passive"))
      (node (ref "U1_5") (pin "39") (pinfunction "DVDD_39") (pintype "passive"))
      (node (ref "U1_5") (pin "4") (pinfunction "DVDD_4") (pintype "passive"))
      (node (ref "U1_5") (pin "40") (pinfunction "DVDD_40") (pintype "passive"))
      (node (ref "U1_5") (pin "41") (pinfunction "DVDD_41") (pintype "passive"))
      (node (ref "U1_5") (pin "42") (pinfunction "DVDD_42") (pintype "passive"))
      (node (ref "U1_5") (pin "45") (pinfunction "DVDD_45") (pintype "passive"))
      (node (ref "U1_5") (pin "46") (pinfunction "DVDD_46") (pintype "passive"))
      (node (ref "U1_5") (pin "47") (pinfunction "DVDD_47") (pintype "passive"))
      (node (ref "U1_5") (pin "48") (pinfunction "DVDD_48") (pintype "passive"))
      (node (ref "U1_5") (pin "6") (pinfunction "VDDA_PLL_6") (pintype "passive"))
      (node (ref "U1_5") (pin "7") (pinfunction "VDD_PLL_7") (pintype "passive"))
      (node (ref "U1_6") (pin "10") (pinfunction "DVDD_10") (pintype "passive"))
      (node (ref "U1_6") (pin "11") (pinfunction "DVDD_11") (pintype "passive"))
      (node (ref "U1_6") (pin "13") (pinfunction "DVDD_13") (pintype "passive"))
      (node (ref "U1_6") (pin "14") (pinfunction "DVDD_14") (pintype "passive"))
      (node (ref "U1_6") (pin "15") (pinfunction "DVDD_15") (pintype "passive"))
      (node (ref "U1_6") (pin "18") (pinfunction "DVDD_18") (pintype "passive"))
      (node (ref "U1_6") (pin "19") (pinfunction "DVDD_19") (pintype "passive"))
      (node (ref "U1_6") (pin "20") (pinfunction "DVDD_20") (pintype "passive"))
      (node (ref "U1_6") (pin "21") (pinfunction "DVDD_21") (pintype "passive"))
      (node (ref "U1_6") (pin "22") (pinfunction "DVDD_22") (pintype "passive"))
      (node (ref "U1_6") (pin "25") (pinfunction "DVDD_25") (pintype "passive"))
      (node (ref "U1_6") (pin "26") (pinfunction "DVDD_26") (pintype "passive"))
      (node (ref "U1_6") (pin "28") (pinfunction "DVDD_28") (pintype "passive"))
      (node (ref "U1_6") (pin "29") (pinfunction "DVDD_29") (pintype "passive"))
      (node (ref "U1_6") (pin "3") (pinfunction "DVDD_3") (pintype "passive"))
      (node (ref "U1_6") (pin "30") (pinfunction "DVDD_30") (pintype "passive"))
      (node (ref "U1_6") (pin "31") (pinfunction "DVDD_31") (pintype "passive"))
      (node (ref "U1_6") (pin "32") (pinfunction "DVDD_32") (pintype "passive"))
      (node (ref "U1_6") (pin "33") (pinfunction "DVDD_33") (pintype "passive"))
      (node (ref "U1_6") (pin "34") (pinfunction "DVDD_34") (pintype "passive"))
      (node (ref "U1_6") (pin "39") (pinfunction "DVDD_39") (pintype "passive"))
      (node (ref "U1_6") (pin "4") (pinfunction "DVDD_4") (pintype "passive"))
      (node (ref "U1_6") (pin "40") (pinfunction "DVDD_40") (pintype "passive"))
      (node (ref "U1_6") (pin "41") (pinfunction "DVDD_41") (pintype "passive"))
      (node (ref "U1_6") (pin "42") (pinfunction "DVDD_42") (pintype "passive"))
      (node (ref "U1_6") (pin "45") (pinfunction "DVDD_45") (pintype "passive"))
      (node (ref "U1_6") (pin "46") (pinfunction "DVDD_46") (pintype "passive"))
      (node (ref "U1_6") (pin "47") (pinfunction "DVDD_47") (pintype "passive"))
      (node (ref "U1_6") (pin "48") (pinfunction "DVDD_48") (pintype "passive"))
      (node (ref "U1_6") (pin "6") (pinfunction "VDDA_PLL_6") (pintype "passive"))
      (node (ref "U1_6") (pin "7") (pinfunction "VDD_PLL_7") (pintype "passive"))
      (node (ref "U1_7") (pin "10") (pinfunction "DVDD_10") (pintype "passive"))
      (node (ref "U1_7") (pin "11") (pinfunction "DVDD_11") (pintype "passive"))
      (node (ref "U1_7") (pin "13") (pinfunction "DVDD_13") (pintype "passive"))
      (node (ref "U1_7") (pin "14") (pinfunction "DVDD_14") (pintype "passive"))
      (node (ref "U1_7") (pin "15") (pinfunction "DVDD_15") (pintype "passive"))
      (node (ref "U1_7") (pin "18") (pinfunction "DVDD_18") (pintype "passive"))
      (node (ref "U1_7") (pin "19") (pinfunction "DVDD_19") (pintype "passive"))
      (node (ref "U1_7") (pin "20") (pinfunction "DVDD_20") (pintype "passive"))
      (node (ref "U1_7") (pin "21") (pinfunction "DVDD_21") (pintype "passive"))
      (node (ref "U1_7") (pin "22") (pinfunction "DVDD_22") (pintype "passive"))
      (node (ref "U1_7") (pin "25") (pinfunction "DVDD_25") (pintype "passive"))
      (node (ref "U1_7") (pin "26") (pinfunction "DVDD_26") (pintype "passive"))
      (node (ref "U1_7") (pin "28") (pinfunction "DVDD_28") (pintype "passive"))
      (node (ref "U1_7") (pin "29") (pinfunction "DVDD_29") (pintype "passive"))
      (node (ref "U1_7") (pin "3") (pinfunction "DVDD_3") (pintype "passive"))
      (node (ref "U1_7") (pin "30") (pinfunction "DVDD_30") (pintype "passive"))
      (node (ref "U1_7") (pin "31") (pinfunction "DVDD_31") (pintype "passive"))
      (node (ref "U1_7") (pin "32") (pinfunction "DVDD_32") (pintype "passive"))
      (node (ref "U1_7") (pin "33") (pinfunction "DVDD_33") (pintype "passive"))
      (node (ref "U1_7") (pin "34") (pinfunction "DVDD_34") (pintype "passive"))
      (node (ref "U1_7") (pin "39") (pinfunction "DVDD_39") (pintype "passive"))
      (node (ref "U1_7") (pin "4") (pinfunction "DVDD_4") (pintype "passive"))
      (node (ref "U1_7") (pin "40") (pinfunction "DVDD_40") (pintype "passive"))
      (node (ref "U1_7") (pin "41") (pinfunction "DVDD_41") (pintype "passive"))
      (node (ref "U1_7") (pin "42") (pinfunction "DVDD_42") (pintype "passive"))
      (node (ref "U1_7") (pin "45") (pinfunction "DVDD_45") (pintype "passive"))
      (node (ref "U1_7") (pin "46") (pinfunction "DVDD_46") (pintype "passive"))
      (node (ref "U1_7") (pin "47") (pinfunction "DVDD_47") (pintype "passive"))
      (node (ref "U1_7") (pin "48") (pinfunction "DVDD_48") (pintype "passive"))
      (node (ref "U1_7") (pin "6") (pinfunction "VDDA_PLL_6") (pintype "passive"))
      (node (ref "U1_7") (pin "7") (pinfunction "VDD_PLL_7") (pintype "passive"))
      (node (ref "U1_8") (pin "10") (pinfunction "DVDD_10") (pintype "passive"))
      (node (ref "U1_8") (pin "11") (pinfunction "DVDD_11") (pintype "passive"))
      (node (ref "U1_8") (pin "13") (pinfunction "DVDD_13") (pintype "passive"))
      (node (ref "U1_8") (pin "14") (pinfunction "DVDD_14") (pintype "passive"))
      (node (ref "U1_8") (pin "15") (pinfunction "DVDD_15") (pintype "passive"))
      (node (ref "U1_8") (pin "18") (pinfunction "DVDD_18") (pintype "passive"))
      (node (ref "U1_8") (pin "19") (pinfunction "DVDD_19") (pintype "passive"))
      (node (ref "U1_8") (pin "20") (pinfunction "DVDD_20") (pintype "passive"))
      (node (ref "U1_8") (pin "21") (pinfunction "DVDD_21") (pintype "passive"))
      (node (ref "U1_8") (pin "22") (pinfunction "DVDD_22") (pintype "passive"))
      (node (ref "U1_8") (pin "25") (pinfunction "DVDD_25") (pintype "passive"))
      (node (ref "U1_8") (pin "26") (pinfunction "DVDD_26") (pintype "passive"))
      (node (ref "U1_8") (pin "28") (pinfunction "DVDD_28") (pintype "passive"))
      (node (ref "U1_8") (pin "29") (pinfunction "DVDD_29") (pintype "passive"))
      (node (ref "U1_8") (pin "3") (pinfunction "DVDD_3") (pintype "passive"))
      (node (ref "U1_8") (pin "30") (pinfunction "DVDD_30") (pintype "passive"))
      (node (ref "U1_8") (pin "31") (pinfunction "DVDD_31") (pintype "passive"))
      (node (ref "U1_8") (pin "32") (pinfunction "DVDD_32") (pintype "passive"))
      (node (ref "U1_8") (pin "33") (pinfunction "DVDD_33") (pintype "passive"))
      (node (ref "U1_8") (pin "34") (pinfunction "DVDD_34") (pintype "passive"))
      (node (ref "U1_8") (pin "39") (pinfunction "DVDD_39") (pintype "passive"))
      (node (ref "U1_8") (pin "4") (pinfunction "DVDD_4") (pintype "passive"))
      (node (ref "U1_8") (pin "40") (pinfunction "DVDD_40") (pintype "passive"))
      (node (ref "U1_8") (pin "41") (pinfunction "DVDD_41") (pintype "passive"))
      (node (ref "U1_8") (pin "42") (pinfunction "DVDD_42") (pintype "passive"))
      (node (ref "U1_8") (pin "45") (pinfunction "DVDD_45") (pintype "passive"))
      (node (ref "U1_8") (pin "46") (pinfunction "DVDD_46") (pintype "passive"))
      (node (ref "U1_8") (pin "47") (pinfunction "DVDD_47") (pintype "passive"))
      (node (ref "U1_8") (pin "48") (pinfunction "DVDD_48") (pintype "passive"))
      (node (ref "U1_8") (pin "6") (pinfunction "VDDA_PLL_6") (pintype "passive"))
      (node (ref "U1_8") (pin "7") (pinfunction "VDD_PLL_7") (pintype "passive"))
      (node (ref "U1_9") (pin "10") (pinfunction "DVDD_10") (pintype "passive"))
      (node (ref "U1_9") (pin "11") (pinfunction "DVDD_11") (pintype "passive"))
      (node (ref "U1_9") (pin "13") (pinfunction "DVDD_13") (pintype "passive"))
      (node (ref "U1_9") (pin "14") (pinfunction "DVDD_14") (pintype "passive"))
      (node (ref "U1_9") (pin "15") (pinfunction "DVDD_15") (pintype "passive"))
      (node (ref "U1_9") (pin "18") (pinfunction "DVDD_18") (pintype "passive"))
      (node (ref "U1_9") (pin "19") (pinfunction "DVDD_19") (pintype "passive"))
      (node (ref "U1_9") (pin "20") (pinfunction "DVDD_20") (pintype "passive"))
      (node (ref "U1_9") (pin "21") (pinfunction "DVDD_21") (pintype "passive"))
      (node (ref "U1_9") (pin "22") (pinfunction "DVDD_22") (pintype "passive"))
      (node (ref "U1_9") (pin "25") (pinfunction "DVDD_25") (pintype "passive"))
      (node (ref "U1_9") (pin "26") (pinfunction "DVDD_26") (pintype "passive"))
      (node (ref "U1_9") (pin "28") (pinfunction "DVDD_28") (pintype "passive"))
      (node (ref "U1_9") (pin "29") (pinfunction "DVDD_29") (pintype "passive"))
      (node (ref "U1_9") (pin "3") (pinfunction "DVDD_3") (pintype "passive"))
      (node (ref "U1_9") (pin "30") (pinfunction "DVDD_30") (pintype "passive"))
      (node (ref "U1_9") (pin "31") (pinfunction "DVDD_31") (pintype "passive"))
      (node (ref "U1_9") (pin "32") (pinfunction "DVDD_32") (pintype "passive"))
      (node (ref "U1_9") (pin "33") (pinfunction "DVDD_33") (pintype "passive"))
      (node (ref "U1_9") (pin "34") (pinfunction "DVDD_34") (pintype "passive"))
      (node (ref "U1_9") (pin "39") (pinfunction "DVDD_39") (pintype "passive"))
      (node (ref "U1_9") (pin "4") (pinfunction "DVDD_4") (pintype "passive"))
      (node (ref "U1_9") (pin "40") (pinfunction "DVDD_40") (pintype "passive"))
      (node (ref "U1_9") (pin "41") (pinfunction "DVDD_41") (pintype "passive"))
      (node (ref "U1_9") (pin "42") (pinfunction "DVDD_42") (pintype "passive"))
      (node (ref "U1_9") (pin "45") (pinfunction "DVDD_45") (pintype "passive"))
      (node (ref "U1_9") (pin "46") (pinfunction "DVDD_46") (pintype "passive"))
      (node (ref "U1_9") (pin "47") (pinfunction "DVDD_47") (pintype "passive"))
      (node (ref "U1_9") (pin "48") (pinfunction "DVDD_48") (pintype "passive"))
      (node (ref "U1_9") (pin "6") (pinfunction "VDDA_PLL_6") (pintype "passive"))
      (node (ref "U1_9") (pin "7") (pinfunction "VDD_PLL_7") (pintype "passive"))
    )
    (net (code "2") (name "/3.3V") (class "Default")
      (node (ref "C211") (pin "1") (pinfunction "1_1") (pintype "passive"))
      (node (ref "C229") (pin "1") (pinfunction "1_1") (pintype "passive"))
      (node (ref "C233") (pin "1") (pinfunction "1_1") (pintype "passive"))
      (node (ref "C234") (pin "1") (pinfunction "1_1") (pintype "passive"))
      (node (ref "C235") (pin "1") (pinfunction "1_1") (pintype "passive"))
      (node (ref "C236") (pin "1") (pinfunction "1_1") (pintype "passive"))
      (node (ref "C237") (pin "1") (pinfunction "1_1") (pintype "passive"))
      (node (ref "C248") (pin "1") (pinfunction "1_1") (pintype "passive"))
      (node (ref "C249") (pin "1") (pinfunction "1_1") (pintype "passive"))
      (node (ref "C250") (pin "1") (pinfunction "1_1") (pintype "passive"))
      (node (ref "C252") (pin "1") (pinfunction "1_1") (pintype "passive"))
      (node (ref "C311") (pin "1") (pinfunction "1_1") (pintype "passive"))
      (node (ref "C34") (pin "1") (pinfunction "1_1") (pintype "passive"))
      (node (ref "C5_1") (pin "2") (pinfunction "2_2") (pintype "passive"))
      (node (ref "C5_10") (pin "2") (pinfunction "2_2") (pintype "passive"))
      (node (ref "C5_11") (pin "2") (pinfunction "2_2") (pintype "passive"))
      (node (ref "C5_12") (pin "2") (pinfunction "2_2") (pintype "passive"))
      (node (ref "C5_13") (pin "2") (pinfunction "2_2") (pintype "passive"))
      (node (ref "C5_14") (pin "2") (pinfunction "2_2") (pintype "passive"))
      (node (ref "C5_15") (pin "2") (pinfunction "2_2") (pintype "passive"))
      (node (ref "C5_16") (pin "2") (pinfunction "2_2") (pintype "passive"))
      (node (ref "C5_2") (pin "2") (pinfunction "2_2") (pintype "passive"))
      (node (ref "C5_3") (pin "2") (pinfunction "2_2") (pintype "passive"))
      (node (ref "C5_4") (pin "2") (pinfunction "2_2") (pintype "passive"))
      (node (ref "C5_5") (pin "2") (pinfunction "2_2") (pintype "passive"))
      (node (ref "C5_6") (pin "2") (pinfunction "2_2") (pintype "passive"))
      (node (ref "C5_7") (pin "2") (pinfunction "2_2") (pintype "passive"))
      (node (ref "C5_8") (pin "2") (pinfunction "2_2") (pintype "passive"))
      (node (ref "C5_9") (pin "2") (pinfunction "2_2") (pintype "passive"))
      (node (ref "C63") (pin "1") (pinfunction "1_1") (pintype "passive"))
      (node (ref "C73") (pin "1") (pinfunction "1_1") (pintype "passive"))
      (node (ref "C74") (pin "1") (pinfunction "1_1") (pintype "passive"))
      (node (ref "C75") (pin "1") (pinfunction "1_1") (pintype "passive"))
      (node (ref "C76") (pin "1") (pinfunction "1_1") (pintype "passive"))
      (node (ref "C8_1") (pin "1") (pinfunction "1_1") (pintype "passive"))
      (node (ref "C8_10") (pin "1") (pinfunction "1_1") (pintype "passive"))
      (node (ref "C8_11") (pin "1") (pinfunction "1_1") (pintype "passive"))
      (node (ref "C8_12") (pin "1") (pinfunction "1_1") (pintype "passive"))
      (node (ref "C8_13") (pin "1") (pinfunction "1_1") (pintype "passive"))
      (node (ref "C8_14") (pin "1") (pinfunction "1_1") (pintype "passive"))
      (node (ref "C8_15") (pin "1") (pinfunction "1_1") (pintype "passive"))
      (node (ref "C8_16") (pin "1") (pinfunction "1_1") (pintype "passive"))
      (node (ref "C8_2") (pin "1") (pinfunction "1_1") (pintype "passive"))
      (node (ref "C8_3") (pin "1") (pinfunction "1_1") (pintype "passive"))
      (node (ref "C8_4") (pin "1") (pinfunction "1_1") (pintype "passive"))
      (node (ref "C8_5") (pin "1") (pinfunction "1_1") (pintype "passive"))
      (node (ref "C8_6") (pin "1") (pinfunction "1_1") (pintype "passive"))
      (node (ref "C8_7") (pin "1") (pinfunction "1_1") (pintype "passive"))
      (node (ref "C8_8") (pin "1") (pinfunction "1_1") (pintype "passive"))
      (node (ref "C8_9") (pin "1") (pinfunction "1_1") (pintype "passive"))
      (node (ref "J1") (pin "2") (pinfunction "2_2") (pintype "passive"))
      (node (ref "R1") (pin "1") (pinfunction "1_1") (pintype "passive"))
      (node (ref "R1_1") (pin "1") (pinfunction "1_1") (pintype "passive"))
      (node (ref "R1_10") (pin "1") (pinfunction "1_1") (pintype "passive"))
      (node (ref "R1_11") (pin "1") (pinfunction "1_1") (pintype "passive"))
      (node (ref "R1_12") (pin "1") (pinfunction "1_1") (pintype "passive"))
      (node (ref "R1_13") (pin "1") (pinfunction "1_1") (pintype "passive"))
      (node (ref "R1_14") (pin "1") (pinfunction "1_1") (pintype "passive"))
      (node (ref "R1_15") (pin "1") (pinfunction "1_1") (pintype "passive"))
      (node (ref "R1_16") (pin "1") (pinfunction "1_1") (pintype "passive"))
      (node (ref "R1_2") (pin "1") (pinfunction "1_1") (pintype "passive"))
      (node (ref "R1_3") (pin "1") (pinfunction "1_1") (pintype "passive"))
      (node (ref "R1_4") (pin "1") (pinfunction "1_1") (pintype "passive"))
      (node (ref "R1_5") (pin "1") (pinfunction "1_1") (pintype "passive"))
      (node (ref "R1_6") (pin "1") (pinfunction "1_1") (pintype "passive"))
      (node (ref "R1_7") (pin "1") (pinfunction "1_1") (pintype "passive"))
      (node (ref "R1_8") (pin "1") (pinfunction "1_1") (pintype "passive"))
      (node (ref "R1_9") (pin "1") (pinfunction "1_1") (pintype "passive"))
      (node (ref "R48") (pin "1") (pinfunction "1_1") (pintype "passive"))
      (node (ref "R49") (pin "1") (pinfunction "1_1") (pintype "passive"))
      (node (ref "R50") (pin "1") (pinfunction "1_1") (pintype "passive"))
      (node (ref "R51") (pin "1") (pinfunction "1_1") (pintype "passive"))
      (node (ref "R52") (pin "2") (pinfunction "2_2") (pintype "passive"))
      (node (ref "R53") (pin "2") (pinfunction "2_2") (pintype "passive"))
      (node (ref "R54") (pin "2") (pinfunction "2_2") (pintype "passive"))
      (node (ref "R55") (pin "2") (pinfunction "2_2") (pintype "passive"))
      (node (ref "R9") (pin "2") (pinfunction "2_2") (pintype "passive"))
      (node (ref "U1") (pin "10") (pinfunction "VDD_10") (pintype "passive"))
      (node (ref "U1") (pin "19") (pinfunction "AVDD_19") (pintype "passive"))
      (node (ref "U1") (pin "26") (pinfunction "VDD_26") (pintype "passive"))
      (node (ref "U1") (pin "35") (pinfunction "VUSB3V3_35") (pintype "passive"))
      (node (ref "U1") (pin "38") (pinfunction "VDD_38") (pintype "passive"))
      (node (ref "U1") (pin "57") (pinfunction "VDD_57") (pintype "passive"))
      (node (ref "U19") (pin "1") (pinfunction "OUTPUT_1") (pintype "passive"))
      (node (ref "U1_1") (pin "24") (pinfunction "OVDD1_24") (pintype "passive"))
      (node (ref "U1_1") (pin "37") (pinfunction "OVDD0_37") (pintype "passive"))
      (node (ref "U1_10") (pin "24") (pinfunction "OVDD1_24") (pintype "passive"))
      (node (ref "U1_10") (pin "37") (pinfunction "OVDD0_37") (pintype "passive"))
      (node (ref "U1_11") (pin "24") (pinfunction "OVDD1_24") (pintype "passive"))
      (node (ref "U1_11") (pin "37") (pinfunction "OVDD0_37") (pintype "passive"))
      (node (ref "U1_12") (pin "24") (pinfunction "OVDD1_24") (pintype "passive"))
      (node (ref "U1_12") (pin "37") (pinfunction "OVDD0_37") (pintype "passive"))
      (node (ref "U1_13") (pin "24") (pinfunction "OVDD1_24") (pintype "passive"))
      (node (ref "U1_13") (pin "37") (pinfunction "OVDD0_37") (pintype "passive"))
      (node (ref "U1_14") (pin "24") (pinfunction "OVDD1_24") (pintype "passive"))
      (node (ref "U1_14") (pin "37") (pinfunction "OVDD0_37") (pintype "passive"))
      (node (ref "U1_15") (pin "24") (pinfunction "OVDD1_24") (pintype "passive"))
      (node (ref "U1_15") (pin "37") (pinfunction "OVDD0_37") (pintype "passive"))
      (node (ref "U1_16") (pin "24") (pinfunction "OVDD1_24") (pintype "passive"))
      (node (ref "U1_16") (pin "37") (pinfunction "OVDD0_37") (pintype "passive"))
      (node (ref "U1_2") (pin "24") (pinfunction "OVDD1_24") (pintype "passive"))
      (node (ref "U1_2") (pin "37") (pinfunction "OVDD0_37") (pintype "passive"))
      (node (ref "U1_3") (pin "24") (pinfunction "OVDD1_24") (pintype "passive"))
      (node (ref "U1_3") (pin "37") (pinfunction "OVDD0_37") (pintype "passive"))
      (node (ref "U1_4") (pin "24") (pinfunction "OVDD1_24") (pintype "passive"))
      (node (ref "U1_4") (pin "37") (pinfunction "OVDD0_37") (pintype "passive"))
      (node (ref "U1_5") (pin "24") (pinfunction "OVDD1_24") (pintype "passive"))
      (node (ref "U1_5") (pin "37") (pinfunction "OVDD0_37") (pintype "passive"))
      (node (ref "U1_6") (pin "24") (pinfunction "OVDD1_24") (pintype "passive"))
      (node (ref "U1_6") (pin "37") (pinfunction "OVDD0_37") (pintype "passive"))
      (node (ref "U1_7") (pin "24") (pinfunction "OVDD1_24") (pintype "passive"))
      (node (ref "U1_7") (pin "37") (pinfunction "OVDD0_37") (pintype "passive"))
      (node (ref "U1_8") (pin "24") (pinfunction "OVDD1_24") (pintype "passive"))
      (node (ref "U1_8") (pin "37") (pinfunction "OVDD0_37") (pintype "passive"))
      (node (ref "U1_9") (pin "24") (pinfunction "OVDD1_24") (pintype "passive"))
      (node (ref "U1_9") (pin "37") (pinfunction "OVDD0_37") (pintype "passive"))
      (node (ref "U2") (pin "5") (pinfunction "VCC_5") (pintype "passive"))
      (node (ref "U25") (pin "6") (pinfunction "Vlogic_6") (pintype "passive"))
      (node (ref "U3") (pin "14") (pinfunction "VCC_14") (pintype "passive"))
      (node (ref "U30") (pin "6") (pinfunction "Vlogic_6") (pintype "passive"))
      (node (ref "U6") (pin "5") (pinfunction "Vout_5") (pintype "passive"))
    )
    (net (code "3") (name "/5.0V") (class "Default")
      (node (ref "C188") (pin "2") (pinfunction "2_2") (pintype "passive"))
      (node (ref "C231") (pin "1") (pinfunction "1_1") (pintype "passive"))
      (node (ref "C308") (pin "2") (pinfunction "2_2") (pintype "passive"))
      (node (ref "D1") (pin "1") (pinfunction "A1_1") (pintype "passive"))
      (node (ref "D1") (pin "2") (pinfunction "A2_2") (pintype "passive"))
      (node (ref "D2") (pin "1") (pinfunction "A1_1") (pintype "passive"))
      (node (ref "D2") (pin "2") (pinfunction "A2_2") (pintype "passive"))
      (node (ref "R42") (pin "1") (pinfunction "1_1") (pintype "passive"))
      (node (ref "R63") (pin "1") (pinfunction "1_1") (pintype "passive"))
      (node (ref "U20") (pin "3") (pinfunction "Vin_3") (pintype "passive"))
      (node (ref "U22") (pin "1") (pinfunction "OUTPUT_1") (pintype "passive"))
      (node (ref "U23") (pin "3") (pinfunction "Vin_3") (pintype "passive"))
      (node (ref "U25") (pin "7") (pinfunction "VCC_7") (pintype "passive"))
      (node (ref "U30") (pin "7") (pinfunction "VCC_7") (pintype "passive"))
    )
    (net (code "4") (name "/5.0V PS") (class "Default")
      (node (ref "J2") (pin "4") (pinfunction "4_4") (pintype "passive"))
      (node (ref "R42") (pin "2") (pinfunction "2_2") (pintype "passive"))
    )
    (net (code "5") (name "/12V") (class "Default")
      (node (ref "C190") (pin "1") (pinfunction "1_1") (pintype "passive"))
      (node (ref "C191") (pin "1") (pinfunction "1_1") (pintype "passive"))
      (node (ref "C192") (pin "1") (pinfunction "1_1") (pintype "passive"))
      (node (ref "C193") (pin "1") (pinfunction "1_1") (pintype "passive"))
      (node (ref "C194") (pin "1") (pinfunction "1_1") (pintype "passive"))
      (node (ref "C195") (pin "1") (pinfunction "1_1") (pintype "passive"))
      (node (ref "C196") (pin "1") (pinfunction "1_1") (pintype "passive"))
      (node (ref "C197") (pin "1") (pinfunction "1_1") (pintype "passive"))
      (node (ref "C207") (pin "1") (pinfunction "1_1") (pintype "passive"))
      (node (ref "C213") (pin "1") (pinfunction "1_1") (pintype "passive"))
      (node (ref "C214") (pin "1") (pinfunction "1_1") (pintype "passive"))
      (node (ref "C215") (pin "1") (pinfunction "1_1") (pintype "passive"))
      (node (ref "C216") (pin "1") (pinfunction "1_1") (pintype "passive"))
      (node (ref "C217") (pin "1") (pinfunction "1_1") (pintype "passive"))
      (node (ref "C218") (pin "1") (pinfunction "1_1") (pintype "passive"))
      (node (ref "C219") (pin "1") (pinfunction "1_1") (pintype "passive"))
      (node (ref "C230") (pin "1") (pinfunction "1_1") (pintype "passive"))
      (node (ref "C263") (pin "1") (pinfunction "1_1") (pintype "passive"))
      (node (ref "C264") (pin "1") (pinfunction "1_1") (pintype "passive"))
      (node (ref "C265") (pin "1") (pinfunction "1_1") (pintype "passive"))
      (node (ref "C266") (pin "1") (pinfunction "1_1") (pintype "passive"))
      (node (ref "C267") (pin "1") (pinfunction "1_1") (pintype "passive"))
      (node (ref "C268") (pin "1") (pinfunction "1_1") (pintype "passive"))
      (node (ref "C269") (pin "1") (pinfunction "1_1") (pintype "passive"))
      (node (ref "C270") (pin "1") (pinfunction "1_1") (pintype "passive"))
      (node (ref "C273") (pin "1") (pinfunction "1_1") (pintype "passive"))
      (node (ref "C274") (pin "1") (pinfunction "1_1") (pintype "passive"))
      (node (ref "C275") (pin "1") (pinfunction "1_1") (pintype "passive"))
      (node (ref "C276") (pin "1") (pinfunction "1_1") (pintype "passive"))
      (node (ref "C277") (pin "1") (pinfunction "1_1") (pintype "passive"))
      (node (ref "C278") (pin "1") (pinfunction "1_1") (pintype "passive"))
      (node (ref "C279") (pin "1") (pinfunction "1_1") (pintype "passive"))
      (node (ref "C280") (pin "1") (pinfunction "1_1") (pintype "passive"))
      (node (ref "J2") (pin "1") (pinfunction "1_1") (pintype "passive"))
      (node (ref "J6") (pin "2") (pinfunction "2_2") (pintype "passive"))
      (node (ref "Q1") (pin "5") (pinfunction "D_5") (pintype "passive"))
      (node (ref "Q1") (pin "6") (pinfunction "D_6") (pintype "passive"))
      (node (ref "Q1") (pin "7") (pinfunction "D_7") (pintype "passive"))
      (node (ref "Q1") (pin "8") (pinfunction "D_8") (pintype "passive"))
      (node (ref "Q4") (pin "5") (pinfunction "D_5") (pintype "passive"))
      (node (ref "Q4") (pin "6") (pinfunction "D_6") (pintype "passive"))
      (node (ref "Q4") (pin "7") (pinfunction "D_7") (pintype "passive"))
      (node (ref "Q4") (pin "8") (pinfunction "D_8") (pintype "passive"))
      (node (ref "R57") (pin "1") (pinfunction "1_1") (pintype "passive"))
      (node (ref "U20") (pin "1") (pinfunction "Vout_1") (pintype "passive"))
      (node (ref "U22") (pin "8") (pinfunction "INPUT_8") (pintype "passive"))
      (node (ref "U23") (pin "1") (pinfunction "Vout_1") (pintype "passive"))
    )
    (net (code "6") (name "/BOOT3") (class "Default")
      (node (ref "C312") (pin "1") (pinfunction "1_1") (pintype "passive"))
      (node (ref "D2") (pin "3") (pinfunction "CC_3") (pintype "passive"))
      (node (ref "U30") (pin "8") (pinfunction "BOOT_8") (pintype "passive"))
    )
    (net (code "7") (name "/BOOT4") (class "Default")
      (node (ref "C189") (pin "1") (pinfunction "1_1") (pintype "passive"))
      (node (ref "D1") (pin "3") (pinfunction "CC_3") (pintype "passive"))
      (node (ref "U25") (pin "8") (pinfunction "BOOT_8") (pintype "passive"))
    )
    (net (code "8") (name "/C1Rx") (class "Default")
      (node (ref "U1") (pin "58") (pinfunction "VCMPST1/RP96/RF0_58") (pintype "passive"))
    )
    (net (code "9") (name "/C1Tx") (class "Default")
      (node (ref "U1") (pin "59") (pinfunction "VCMPST2/RP97/RF1_59") (pintype "passive"))
    )
    (net (code "10") (name "/CAN5.0V") (class "Default")
      (node (ref "R47") (pin "1") (pinfunction "1_1") (pintype "passive"))
      (node (ref "R64") (pin "1") (pinfunction "1_1") (pintype "passive"))
    )
    (net (code "11") (name "/CONFIG_N1") (class "Default")
      (node (ref "U1") (pin "42") (pinfunction "RTCC/DMLN/RPI72/RD8_42") (pintype "passive"))
      (node (ref "U1_1") (pin "2") (pinfunction "CONFIG_NI_2") (pintype "passive"))
    )
    (net (code "12") (name "/CONFIG_N2") (class "Default")
      (node (ref "U1_1") (pin "35") (pinfunction "CONFIG_NO_35") (pintype "passive"))
      (node (ref "U1_2") (pin "2") (pinfunction "CONFIG_NI_2") (pintype "passive"))
    )
    (net (code "13") (name "/CONFIG_N3") (class "Default")
      (node (ref "U1_2") (pin "35") (pinfunction "CONFIG_NO_35") (pintype "passive"))
      (node (ref "U1_3") (pin "2") (pinfunction "CONFIG_NI_2") (pintype "passive"))
    )
    (net (code "14") (name "/CONFIG_N4") (class "Default")
      (node (ref "U1_3") (pin "35") (pinfunction "CONFIG_NO_35") (pintype "passive"))
      (node (ref "U1_4") (pin "2") (pinfunction "CONFIG_NI_2") (pintype "passive"))
    )
    (net (code "15") (name "/CONFIG_N5") (class "Default")
      (node (ref "U1_4") (pin "35") (pinfunction "CONFIG_NO_35") (pintype "passive"))
      (node (ref "U1_5") (pin "2") (pinfunction "CONFIG_NI_2") (pintype "passive"))
    )
    (net (code "16") (name "/CONFIG_N6") (class "Default")
      (node (ref "U1_5") (pin "35") (pinfunction "CONFIG_NO_35") (pintype "passive"))
      (node (ref "U1_6") (pin "2") (pinfunction "CONFIG_NI_2") (pintype "passive"))
    )
    (net (code "17") (name "/CONFIG_N7") (class "Default")
      (node (ref "U1_6") (pin "35") (pinfunction "CONFIG_NO_35") (pintype "passive"))
      (node (ref "U1_7") (pin "2") (pinfunction "CONFIG_NI_2") (pintype "passive"))
    )
    (net (code "18") (name "/CONFIG_N8") (class "Default")
      (node (ref "U1_7") (pin "35") (pinfunction "CONFIG_NO_35") (pintype "passive"))
      (node (ref "U1_8") (pin "2") (pinfunction "CONFIG_NI_2") (pintype "passive"))
    )
    (net (code "19") (name "/CONFIG_N9") (class "Default")
      (node (ref "R25") (pin "2") (pinfunction "2_2") (pintype "passive"))
      (node (ref "U1_8") (pin "35") (pinfunction "CONFIG_NO_35") (pintype "passive"))
    )
    (net (code "20") (name "/CONFIG_N9I") (class "Default")
      (node (ref "R25") (pin "1") (pinfunction "1_1") (pintype "passive"))
      (node (ref "U1") (pin "54") (pinfunction "C3IN2-/RP70/RD6_54") (pintype "passive"))
      (node (ref "U1_9") (pin "2") (pinfunction "CONFIG_NI_2") (pintype "passive"))
    )
    (net (code "21") (name "/CONFIG_N10") (class "Default")
      (node (ref "U1_10") (pin "2") (pinfunction "CONFIG_NI_2") (pintype "passive"))
      (node (ref "U1_9") (pin "35") (pinfunction "CONFIG_NO_35") (pintype "passive"))
    )
    (net (code "22") (name "/CONFIG_N11") (class "Default")
      (node (ref "U1_10") (pin "35") (pinfunction "CONFIG_NO_35") (pintype "passive"))
      (node (ref "U1_11") (pin "2") (pinfunction "CONFIG_NI_2") (pintype "passive"))
    )
    (net (code "23") (name "/CONFIG_N12") (class "Default")
      (node (ref "U1_11") (pin "35") (pinfunction "CONFIG_NO_35") (pintype "passive"))
      (node (ref "U1_12") (pin "2") (pinfunction "CONFIG_NI_2") (pintype "passive"))
    )
    (net (code "24") (name "/CONFIG_N13") (class "Default")
      (node (ref "U1_12") (pin "35") (pinfunction "CONFIG_NO_35") (pintype "passive"))
      (node (ref "U1_13") (pin "2") (pinfunction "CONFIG_NI_2") (pintype "passive"))
    )
    (net (code "25") (name "/CONFIG_N14") (class "Default")
      (node (ref "U1_13") (pin "35") (pinfunction "CONFIG_NO_35") (pintype "passive"))
      (node (ref "U1_14") (pin "2") (pinfunction "CONFIG_NI_2") (pintype "passive"))
    )
    (net (code "26") (name "/CONFIG_N15") (class "Default")
      (node (ref "U1_14") (pin "35") (pinfunction "CONFIG_NO_35") (pintype "passive"))
      (node (ref "U1_15") (pin "2") (pinfunction "CONFIG_NI_2") (pintype "passive"))
    )
    (net (code "27") (name "/CONFIG_N16") (class "Default")
      (node (ref "U1_15") (pin "35") (pinfunction "CONFIG_NO_35") (pintype "passive"))
      (node (ref "U1_16") (pin "2") (pinfunction "CONFIG_NI_2") (pintype "passive"))
    )
    (net (code "28") (name "/CONFIG_N17") (class "Default")
      (node (ref "U1_16") (pin "35") (pinfunction "CONFIG_NO_35") (pintype "passive"))
    )
    (net (code "29") (name "/CONFIG_P1") (class "Default")
      (node (ref "U1") (pin "43") (pinfunction "ASDA1/DPLN/RPI73/RD9_43") (pintype "passive"))
      (node (ref "U1_1") (pin "1") (pinfunction "CONFIG_PI_1") (pintype "passive"))
    )
    (net (code "30") (name "/CONFIG_P2") (class "Default")
      (node (ref "U1_1") (pin "36") (pinfunction "CONFIG_PO_36") (pintype "passive"))
      (node (ref "U1_2") (pin "1") (pinfunction "CONFIG_PI_1") (pintype "passive"))
    )
    (net (code "31") (name "/CONFIG_P3") (class "Default")
      (node (ref "U1_2") (pin "36") (pinfunction "CONFIG_PO_36") (pintype "passive"))
      (node (ref "U1_3") (pin "1") (pinfunction "CONFIG_PI_1") (pintype "passive"))
    )
    (net (code "32") (name "/CONFIG_P4") (class "Default")
      (node (ref "U1_3") (pin "36") (pinfunction "CONFIG_PO_36") (pintype "passive"))
      (node (ref "U1_4") (pin "1") (pinfunction "CONFIG_PI_1") (pintype "passive"))
    )
    (net (code "33") (name "/CONFIG_P5") (class "Default")
      (node (ref "U1_4") (pin "36") (pinfunction "CONFIG_PO_36") (pintype "passive"))
      (node (ref "U1_5") (pin "1") (pinfunction "CONFIG_PI_1") (pintype "passive"))
    )
    (net (code "34") (name "/CONFIG_P6") (class "Default")
      (node (ref "U1_5") (pin "36") (pinfunction "CONFIG_PO_36") (pintype "passive"))
      (node (ref "U1_6") (pin "1") (pinfunction "CONFIG_PI_1") (pintype "passive"))
    )
    (net (code "35") (name "/CONFIG_P7") (class "Default")
      (node (ref "U1_6") (pin "36") (pinfunction "CONFIG_PO_36") (pintype "passive"))
      (node (ref "U1_7") (pin "1") (pinfunction "CONFIG_PI_1") (pintype "passive"))
    )
    (net (code "36") (name "/CONFIG_P8") (class "Default")
      (node (ref "U1_7") (pin "36") (pinfunction "CONFIG_PO_36") (pintype "passive"))
      (node (ref "U1_8") (pin "1") (pinfunction "CONFIG_PI_1") (pintype "passive"))
    )
    (net (code "37") (name "/CONFIG_P9") (class "Default")
      (node (ref "R24") (pin "2") (pinfunction "2_2") (pintype "passive"))
      (node (ref "U1_8") (pin "36") (pinfunction "CONFIG_PO_36") (pintype "passive"))
    )
    (net (code "38") (name "/CONFIG_P9I") (class "Default")
      (node (ref "R24") (pin "1") (pinfunction "1_1") (pintype "passive"))
      (node (ref "U1") (pin "55") (pinfunction "C3IN1+/VCMPST3/RP71/RD7_55") (pintype "passive"))
      (node (ref "U1_9") (pin "1") (pinfunction "CONFIG_PI_1") (pintype "passive"))
    )
    (net (code "39") (name "/CONFIG_P10") (class "Default")
      (node (ref "U1_10") (pin "1") (pinfunction "CONFIG_PI_1") (pintype "passive"))
      (node (ref "U1_9") (pin "36") (pinfunction "CONFIG_PO_36") (pintype "passive"))
    )
    (net (code "40") (name "/CONFIG_P11") (class "Default")
      (node (ref "U1_10") (pin "36") (pinfunction "CONFIG_PO_36") (pintype "passive"))
      (node (ref "U1_11") (pin "1") (pinfunction "CONFIG_PI_1") (pintype "passive"))
    )
    (net (code "41") (name "/CONFIG_P12") (class "Default")
      (node (ref "U1_11") (pin "36") (pinfunction "CONFIG_PO_36") (pintype "passive"))
      (node (ref "U1_12") (pin "1") (pinfunction "CONFIG_PI_1") (pintype "passive"))
    )
    (net (code "42") (name "/CONFIG_P13") (class "Default")
      (node (ref "U1_12") (pin "36") (pinfunction "CONFIG_PO_36") (pintype "passive"))
      (node (ref "U1_13") (pin "1") (pinfunction "CONFIG_PI_1") (pintype "passive"))
    )
    (net (code "43") (name "/CONFIG_P14") (class "Default")
      (node (ref "U1_13") (pin "36") (pinfunction "CONFIG_PO_36") (pintype "passive"))
      (node (ref "U1_14") (pin "1") (pinfunction "CONFIG_PI_1") (pintype "passive"))
    )
    (net (code "44") (name "/CONFIG_P15") (class "Default")
      (node (ref "U1_14") (pin "36") (pinfunction "CONFIG_PO_36") (pintype "passive"))
      (node (ref "U1_15") (pin "1") (pinfunction "CONFIG_PI_1") (pintype "passive"))
    )
    (net (code "45") (name "/CONFIG_P16") (class "Default")
      (node (ref "U1_15") (pin "36") (pinfunction "CONFIG_PO_36") (pintype "passive"))
      (node (ref "U1_16") (pin "1") (pinfunction "CONFIG_PI_1") (pintype "passive"))
    )
    (net (code "46") (name "/CONFIG_P17") (class "Default")
      (node (ref "U1_16") (pin "36") (pinfunction "CONFIG_PO_36") (pintype "passive"))
    )
    (net (code "47") (name "/CSN4") (class "Default")
      (node (ref "R38") (pin "1") (pinfunction "1_1") (pintype "passive"))
      (node (ref "U1") (pin "14") (pinfunction "AN2/C2IN2-/VMIO/RPI34/RB2_14") (pintype "passive"))
    )
    (net (code "48") (name "/CSP4") (class "Default")
      (node (ref "R37") (pin "1") (pinfunction "1_1") (pintype "passive"))
      (node (ref "U1") (pin "13") (pinfunction "AN3/C2IN1+/VPIO/RPI35/RB3_13") (pintype "passive"))
    )
    (net (code "49") (name "/C_CLK_OUT1") (class "Default")
      (node (ref "U1_1") (pin "43") (pinfunction "CORE_CLKOUT_43") (pintype "passive"))
    )
    (net (code "50") (name "/C_CLK_OUT2") (class "Default")
      (node (ref "U1_2") (pin "43") (pinfunction "CORE_CLKOUT_43") (pintype "passive"))
    )
    (net (code "51") (name "/C_CLK_OUT3") (class "Default")
      (node (ref "U1_3") (pin "43") (pinfunction "CORE_CLKOUT_43") (pintype "passive"))
    )
    (net (code "52") (name "/C_CLK_OUT4") (class "Default")
      (node (ref "U1_4") (pin "43") (pinfunction "CORE_CLKOUT_43") (pintype "passive"))
    )
    (net (code "53") (name "/C_CLK_OUT5") (class "Default")
      (node (ref "U1_5") (pin "43") (pinfunction "CORE_CLKOUT_43") (pintype "passive"))
    )
    (net (code "54") (name "/C_CLK_OUT6") (class "Default")
      (node (ref "U1_6") (pin "43") (pinfunction "CORE_CLKOUT_43") (pintype "passive"))
    )
    (net (code "55") (name "/C_CLK_OUT7") (class "Default")
      (node (ref "U1_7") (pin "43") (pinfunction "CORE_CLKOUT_43") (pintype "passive"))
    )
    (net (code "56") (name "/C_CLK_OUT8") (class "Default")
      (node (ref "U1_8") (pin "43") (pinfunction "CORE_CLKOUT_43") (pintype "passive"))
    )
    (net (code "57") (name "/C_CLK_OUT9") (class "Default")
      (node (ref "U1_9") (pin "43") (pinfunction "CORE_CLKOUT_43") (pintype "passive"))
    )
    (net (code "58") (name "/C_CLK_OUT10") (class "Default")
      (node (ref "U1_10") (pin "43") (pinfunction "CORE_CLKOUT_43") (pintype "passive"))
    )
    (net (code "59") (name "/C_CLK_OUT11") (class "Default")
      (node (ref "U1_11") (pin "43") (pinfunction "CORE_CLKOUT_43") (pintype "passive"))
    )
    (net (code "60") (name "/C_CLK_OUT12") (class "Default")
      (node (ref "U1_12") (pin "43") (pinfunction "CORE_CLKOUT_43") (pintype "passive"))
    )
    (net (code "61") (name "/C_CLK_OUT13") (class "Default")
      (node (ref "U1_13") (pin "43") (pinfunction "CORE_CLKOUT_43") (pintype "passive"))
    )
    (net (code "62") (name "/C_CLK_OUT14") (class "Default")
      (node (ref "U1_14") (pin "43") (pinfunction "CORE_CLKOUT_43") (pintype "passive"))
    )
    (net (code "63") (name "/C_CLK_OUT15") (class "Default")
      (node (ref "U1_15") (pin "43") (pinfunction "CORE_CLKOUT_43") (pintype "passive"))
    )
    (net (code "64") (name "/C_CLK_OUT16") (class "Default")
      (node (ref "U1_16") (pin "43") (pinfunction "CORE_CLKOUT_43") (pintype "passive"))
    )
    (net (code "65") (name "/D+") (class "Default")
      (node (ref "C254") (pin "2") (pinfunction "2_2") (pintype "passive"))
      (node (ref "R35") (pin "2") (pinfunction "2_2") (pintype "passive"))
      (node (ref "U1") (pin "37") (pinfunction "D+/RG2_37") (pintype "passive"))
    )
    (net (code "66") (name "/D-") (class "Default")
      (node (ref "C253") (pin "2") (pinfunction "2_2") (pintype "passive"))
      (node (ref "R34") (pin "2") (pinfunction "2_2") (pintype "passive"))
      (node (ref "U1") (pin "36") (pinfunction "D-/RG3_36") (pintype "passive"))
    )
    (net (code "67") (name "/FAN5.0V") (class "Default")
      (node (ref "R63") (pin "2") (pinfunction "2_2") (pintype "passive"))
      (node (ref "R64") (pin "2") (pinfunction "2_2") (pintype "passive"))
    )
    (net (code "68") (name "/FB") (class "Default")
      (node (ref "C251") (pin "1") (pinfunction "1_1") (pintype "passive"))
      (node (ref "R43") (pin "1") (pinfunction "1_1") (pintype "passive"))
      (node (ref "U1") (pin "17") (pinfunction "PGEC1/AN6/RPI38/RB6_17") (pintype "passive"))
    )
    (net (code "69") (name "/GREEN") (class "Default")
      (node (ref "D5") (pin "2") (pinfunction "A_2") (pintype "passive"))
      (node (ref "U1") (pin "62") (pinfunction "AN26/PWM2L/PMD2/RP82/RE2_62") (pintype "passive"))
    )
    (net (code "70") (name "/HO3") (class "Default")
      (node (ref "Q4") (pin "4") (pinfunction "G_4") (pintype "passive"))
      (node (ref "U30") (pin "1") (pinfunction "HO_1") (pintype "passive"))
    )
    (net (code "71") (name "/HO4") (class "Default")
      (node (ref "Q1") (pin "4") (pinfunction "G_4") (pintype "passive"))
      (node (ref "U25") (pin "1") (pinfunction "HO_1") (pintype "passive"))
    )
    (net (code "72") (name "/LDO5.0V") (class "Default")
      (node (ref "C187") (pin "1") (pinfunction "1_1") (pintype "passive"))
      (node (ref "R46") (pin "1") (pinfunction "1_1") (pintype "passive"))
      (node (ref "R47") (pin "2") (pinfunction "2_2") (pintype "passive"))
      (node (ref "R62") (pin "2") (pinfunction "2_2") (pintype "passive"))
      (node (ref "U19") (pin "5") (pinfunction "N.C._5") (pintype "passive"))
      (node (ref "U19") (pin "8") (pinfunction "INPUT_8") (pintype "passive"))
      (node (ref "U6") (pin "1") (pinfunction "Vin_1") (pintype "passive"))
      (node (ref "U6") (pin "3") (pinfunction "STBY_3") (pintype "passive"))
    )
    (net (code "73") (name "/LMGND") (class "Default")
      (node (ref "D3") (pin "3") (pinfunction "CC_3") (pintype "passive"))
      (node (ref "R60") (pin "2") (pinfunction "2_2") (pintype "passive"))
      (node (ref "U20") (pin "2") (pinfunction "GND_2") (pintype "passive"))
      (node (ref "U22") (pin "2") (pinfunction "GND_2") (pintype "passive"))
      (node (ref "U22") (pin "3") (pinfunction "GND_3") (pintype "passive"))
      (node (ref "U22") (pin "4") (pinfunction "N.C._4") (pintype "passive"))
      (node (ref "U22") (pin "5") (pinfunction "N.C._5") (pintype "passive"))
      (node (ref "U22") (pin "6") (pinfunction "GND_6") (pintype "passive"))
      (node (ref "U22") (pin "7") (pinfunction "GND_7") (pintype "passive"))
      (node (ref "U23") (pin "2") (pinfunction "GND_2") (pintype "passive"))
    )
    (net (code "74") (name "/LO3") (class "Default")
      (node (ref "Q5") (pin "4") (pinfunction "G_4") (pintype "passive"))
      (node (ref "Q6") (pin "4") (pinfunction "G_4") (pintype "passive"))
      (node (ref "U30") (pin "3") (pinfunction "LO_3") (pintype "passive"))
    )
    (net (code "75") (name "/LO4") (class "Default")
      (node (ref "Q2") (pin "4") (pinfunction "G_4") (pintype "passive"))
      (node (ref "Q3") (pin "4") (pinfunction "G_4") (pintype "passive"))
      (node (ref "U25") (pin "3") (pinfunction "LO_3") (pintype "passive"))
    )
    (net (code "76") (name "/MCLR") (class "Default")
      (node (ref "C72") (pin "1") (pinfunction "1_1") (pintype "passive"))
      (node (ref "J1") (pin "1") (pinfunction "1_1") (pintype "passive"))
      (node (ref "R9") (pin "1") (pinfunction "1_1") (pintype "passive"))
      (node (ref "U1") (pin "7") (pinfunction "MCLR_7") (pintype "passive"))
    )
    (net (code "77") (name "/MEAS12") (class "Default")
      (node (ref "C325") (pin "1") (pinfunction "1_1") (pintype "passive"))
      (node (ref "R57") (pin "2") (pinfunction "2_2") (pintype "passive"))
      (node (ref "R61") (pin "2") (pinfunction "2_2") (pintype "passive"))
      (node (ref "U1") (pin "18") (pinfunction "PGED1/AN7/RCV/RPI39/RB7_18") (pintype "passive"))
    )
    (net (code "78") (name "/Main OSC In") (class "Default")
      (node (ref "C85") (pin "1") (pinfunction "1_1") (pintype "passive"))
      (node (ref "U1") (pin "39") (pinfunction "OSC1/RPI60/RC12_39") (pintype "passive"))
      (node (ref "Y1") (pin "1") (pinfunction "1_1") (pintype "passive"))
    )
    (net (code "79") (name "/Main OSC Out") (class "Default")
      (node (ref "C86") (pin "1") (pinfunction "1_1") (pintype "passive"))
      (node (ref "U1") (pin "40") (pinfunction "OSC2/CLKO/RC15_40") (pintype "passive"))
      (node (ref "Y1") (pin "2") (pinfunction "2_2") (pintype "passive"))
    )
    (net (code "80") (name "/ORANGE") (class "Default")
      (node (ref "D7") (pin "2") (pinfunction "A_2") (pintype "passive"))
      (node (ref "U1") (pin "45") (pinfunction "PMCS1/RPI75/RD11_45") (pintype "passive"))
    )
    (net (code "81") (name "/PGC") (class "Default")
      (node (ref "J1") (pin "5") (pinfunction "5_5") (pintype "passive"))
      (node (ref "U1") (pin "15") (pinfunction "PGEC3/AN1/VREF-/RPI33/RB1_15") (pintype "passive"))
    )
    (net (code "82") (name "/PGD") (class "Default")
      (node (ref "J1") (pin "4") (pinfunction "4_4") (pintype "passive"))
      (node (ref "U1") (pin "16") (pinfunction "PGED3/AN0/VREF+/RPI32/RB0_16") (pintype "passive"))
    )
    (net (code "83") (name "/PWM") (class "Default")
      (node (ref "J6") (pin "4") (pinfunction "4_4") (pintype "passive"))
      (node (ref "U1") (pin "61") (pinfunction "AN25/PWM1H/PMD1/RPI81/RE1_61") (pintype "passive"))
    )
    (net (code "84") (name "/PWM3H") (class "Default")
      (node (ref "R59") (pin "2") (pinfunction "2_2") (pintype "passive"))
      (node (ref "U1") (pin "1") (pinfunction "AN29/PWM3H/PMD5/RP85/RE5_1") (pintype "passive"))
      (node (ref "U30") (pin "5") (pinfunction "IN_5") (pintype "passive"))
    )
    (net (code "85") (name "/PWM3L") (class "Default")
      (node (ref "U1") (pin "64") (pinfunction "AN28/PWM3L/PMD4/RP84/RE4_64") (pintype "passive"))
    )
    (net (code "86") (name "/PWM4H") (class "Default")
      (node (ref "R40") (pin "2") (pinfunction "2_2") (pintype "passive"))
      (node (ref "U1") (pin "3") (pinfunction "AN31/PWM4H/PMD7/RP87/RE7_3") (pintype "passive"))
      (node (ref "U25") (pin "5") (pinfunction "IN_5") (pintype "passive"))
    )
    (net (code "87") (name "/PWM4L") (class "Default")
      (node (ref "U1") (pin "2") (pinfunction "AN30/PWM4L/PMD6/RPI86/RE6_2") (pintype "passive"))
    )
    (net (code "88") (name "/RED") (class "Default")
      (node (ref "D4") (pin "2") (pinfunction "A_2") (pintype "passive"))
      (node (ref "U1") (pin "63") (pinfunction "AN27/PWM2H/PMD3/RPI83/RE3_63") (pintype "passive"))
    )
    (net (code "89") (name "/REPORT_N1-4") (class "Default")
      (node (ref "R18") (pin "2") (pinfunction "2_2") (pintype "passive"))
      (node (ref "R22") (pin "2") (pinfunction "2_2") (pintype "passive"))
      (node (ref "R50") (pin "2") (pinfunction "2_2") (pintype "passive"))
      (node (ref "U1") (pin "48") (pinfunction "PGEC2/SOSCO/C3IN1-/T1CK/RPI62/RC14_48") (pintype "passive"))
      (node (ref "U1_1") (pin "16") (pinfunction "REPORT_N_16") (pintype "passive"))
      (node (ref "U1_2") (pin "16") (pinfunction "REPORT_N_16") (pintype "passive"))
      (node (ref "U1_3") (pin "16") (pinfunction "REPORT_N_16") (pintype "passive"))
      (node (ref "U1_4") (pin "16") (pinfunction "REPORT_N_16") (pintype "passive"))
    )
    (net (code "90") (name "/REPORT_N5-8") (class "Default")
      (node (ref "R18") (pin "1") (pinfunction "1_1") (pintype "passive"))
      (node (ref "R49") (pin "2") (pinfunction "2_2") (pintype "passive"))
      (node (ref "U1") (pin "50") (pinfunction "DPH/RP66/RD2_50") (pintype "passive"))
      (node (ref "U1_5") (pin "16") (pinfunction "REPORT_N_16") (pintype "passive"))
      (node (ref "U1_6") (pin "16") (pinfunction "REPORT_N_16") (pintype "passive"))
      (node (ref "U1_7") (pin "16") (pinfunction "REPORT_N_16") (pintype "passive"))
      (node (ref "U1_8") (pin "16") (pinfunction "REPORT_N_16") (pintype "passive"))
    )
    (net (code "91") (name "/REPORT_N9-12") (class "Default")
      (node (ref "R26") (pin "2") (pinfunction "2_2") (pintype "passive"))
      (node (ref "R55") (pin "1") (pinfunction "1_1") (pintype "passive"))
      (node (ref "U1") (pin "30") (pinfunction "AN15/PMA0/RPI47/RB15_30") (pintype "passive"))
      (node (ref "U1_10") (pin "16") (pinfunction "REPORT_N_16") (pintype "passive"))
      (node (ref "U1_11") (pin "16") (pinfunction "REPORT_N_16") (pintype "passive"))
      (node (ref "U1_12") (pin "16") (pinfunction "REPORT_N_16") (pintype "passive"))
      (node (ref "U1_9") (pin "16") (pinfunction "REPORT_N_16") (pintype "passive"))
    )
    (net (code "92") (name "/REPORT_N13-16") (class "Default")
      (node (ref "R22") (pin "1") (pinfunction "1_1") (pintype "passive"))
      (node (ref "R26") (pin "1") (pinfunction "1_1") (pintype "passive"))
      (node (ref "R54") (pin "1") (pinfunction "1_1") (pintype "passive"))
      (node (ref "U1") (pin "29") (pinfunction "AN14/PMA1/RPI46/RB14_29") (pintype "passive"))
      (node (ref "U1_13") (pin "16") (pinfunction "REPORT_N_16") (pintype "passive"))
      (node (ref "U1_14") (pin "16") (pinfunction "REPORT_N_16") (pintype "passive"))
      (node (ref "U1_15") (pin "16") (pinfunction "REPORT_N_16") (pintype "passive"))
      (node (ref "U1_16") (pin "16") (pinfunction "REPORT_N_16") (pintype "passive"))
    )
    (net (code "93") (name "/REPORT_P1-4") (class "Default")
      (node (ref "R19") (pin "2") (pinfunction "2_2") (pintype "passive"))
      (node (ref "R23") (pin "2") (pinfunction "2_2") (pintype "passive"))
      (node (ref "R51") (pin "2") (pinfunction "2_2") (pintype "passive"))
      (node (ref "U1") (pin "47") (pinfunction "PGED2/SOSCI/C3IN3-/RPI61/RC13_47") (pintype "passive"))
      (node (ref "U1_1") (pin "17") (pinfunction "REPORT_P_17") (pintype "passive"))
      (node (ref "U1_2") (pin "17") (pinfunction "REPORT_P_17") (pintype "passive"))
      (node (ref "U1_3") (pin "17") (pinfunction "REPORT_P_17") (pintype "passive"))
      (node (ref "U1_4") (pin "17") (pinfunction "REPORT_P_17") (pintype "passive"))
    )
    (net (code "94") (name "/REPORT_P5-8") (class "Default")
      (node (ref "R19") (pin "1") (pinfunction "1_1") (pintype "passive"))
      (node (ref "R48") (pin "2") (pinfunction "2_2") (pintype "passive"))
      (node (ref "U1") (pin "51") (pinfunction "PMBE/RP67/RD3_51") (pintype "passive"))
      (node (ref "U1_5") (pin "17") (pinfunction "REPORT_P_17") (pintype "passive"))
      (node (ref "U1_6") (pin "17") (pinfunction "REPORT_P_17") (pintype "passive"))
      (node (ref "U1_7") (pin "17") (pinfunction "REPORT_P_17") (pintype "passive"))
      (node (ref "U1_8") (pin "17") (pinfunction "REPORT_P_17") (pintype "passive"))
    )
    (net (code "95") (name "/REPORT_P9-12") (class "Default")
      (node (ref "R27") (pin "2") (pinfunction "2_2") (pintype "passive"))
      (node (ref "R53") (pin "1") (pinfunction "1_1") (pintype "passive"))
      (node (ref "U1") (pin "28") (pinfunction "TDI/AN13/PMA10/RPI45/RB13_28") (pintype "passive"))
      (node (ref "U1_10") (pin "17") (pinfunction "REPORT_P_17") (pintype "passive"))
      (node (ref "U1_11") (pin "17") (pinfunction "REPORT_P_17") (pintype "passive"))
      (node (ref "U1_12") (pin "17") (pinfunction "REPORT_P_17") (pintype "passive"))
      (node (ref "U1_9") (pin "17") (pinfunction "REPORT_P_17") (pintype "passive"))
    )
    (net (code "96") (name "/REPORT_P13-16") (class "Default")
      (node (ref "R23") (pin "1") (pinfunction "1_1") (pintype "passive"))
      (node (ref "R27") (pin "1") (pinfunction "1_1") (pintype "passive"))
      (node (ref "R52") (pin "1") (pinfunction "1_1") (pintype "passive"))
      (node (ref "U1") (pin "27") (pinfunction "TCK/AN12/PMA11/RPI44/RB12_27") (pintype "passive"))
      (node (ref "U1_13") (pin "17") (pinfunction "REPORT_P_17") (pintype "passive"))
      (node (ref "U1_14") (pin "17") (pinfunction "REPORT_P_17") (pintype "passive"))
      (node (ref "U1_15") (pin "17") (pinfunction "REPORT_P_17") (pintype "passive"))
      (node (ref "U1_16") (pin "17") (pinfunction "REPORT_P_17") (pintype "passive"))
    )
    (net (code "97") (name "/RESET1") (class "Default")
      (node (ref "C10_1") (pin "1") (pinfunction "1_1") (pintype "passive"))
      (node (ref "R1_1") (pin "2") (pinfunction "2_2") (pintype "passive"))
      (node (ref "U1_1") (pin "44") (pinfunction "RSTN_44") (pintype "passive"))
    )
    (net (code "98") (name "/RESET2") (class "Default")
      (node (ref "C10_2") (pin "1") (pinfunction "1_1") (pintype "passive"))
      (node (ref "R1_2") (pin "2") (pinfunction "2_2") (pintype "passive"))
      (node (ref "U1_2") (pin "44") (pinfunction "RSTN_44") (pintype "passive"))
    )
    (net (code "99") (name "/RESET3") (class "Default")
      (node (ref "C10_3") (pin "1") (pinfunction "1_1") (pintype "passive"))
      (node (ref "R1_3") (pin "2") (pinfunction "2_2") (pintype "passive"))
      (node (ref "U1_3") (pin "44") (pinfunction "RSTN_44") (pintype "passive"))
    )
    (net (code "100") (name "/RESET4") (class "Default")
      (node (ref "C10_4") (pin "1") (pinfunction "1_1") (pintype "passive"))
      (node (ref "R1_4") (pin "2") (pinfunction "2_2") (pintype "passive"))
      (node (ref "U1_4") (pin "44") (pinfunction "RSTN_44") (pintype "passive"))
    )
    (net (code "101") (name "/RESET5") (class "Default")
      (node (ref "C10_5") (pin "1") (pinfunction "1_1") (pintype "passive"))
      (node (ref "R1_5") (pin "2") (pinfunction "2_2") (pintype "passive"))
      (node (ref "U1_5") (pin "44") (pinfunction "RSTN_44") (pintype "passive"))
    )
    (net (code "102") (name "/RESET6") (class "Default")
      (node (ref "C10_6") (pin "1") (pinfunction "1_1") (pintype "passive"))
      (node (ref "R1_6") (pin "2") (pinfunction "2_2") (pintype "passive"))
      (node (ref "U1_6") (pin "44") (pinfunction "RSTN_44") (pintype "passive"))
    )
    (net (code "103") (name "/RESET7") (class "Default")
      (node (ref "C10_7") (pin "1") (pinfunction "1_1") (pintype "passive"))
      (node (ref "R1_7") (pin "2") (pinfunction "2_2") (pintype "passive"))
      (node (ref "U1_7") (pin "44") (pinfunction "RSTN_44") (pintype "passive"))
    )
    (net (code "104") (name "/RESET8") (class "Default")
      (node (ref "C10_8") (pin "1") (pinfunction "1_1") (pintype "passive"))
      (node (ref "R1_8") (pin "2") (pinfunction "2_2") (pintype "passive"))
      (node (ref "U1_8") (pin "44") (pinfunction "RSTN_44") (pintype "passive"))
    )
    (net (code "105") (name "/RESET9") (class "Default")
      (node (ref "C10_9") (pin "1") (pinfunction "1_1") (pintype "passive"))
      (node (ref "R1_9") (pin "2") (pinfunction "2_2") (pintype "passive"))
      (node (ref "U1_9") (pin "44") (pinfunction "RSTN_44") (pintype "passive"))
    )
    (net (code "106") (name "/RESET10") (class "Default")
      (node (ref "C10_10") (pin "1") (pinfunction "1_1") (pintype "passive"))
      (node (ref "R1_10") (pin "2") (pinfunction "2_2") (pintype "passive"))
      (node (ref "U1_10") (pin "44") (pinfunction "RSTN_44") (pintype "passive"))
    )
    (net (code "107") (name "/RESET11") (class "Default")
      (node (ref "C10_11") (pin "1") (pinfunction "1_1") (pintype "passive"))
      (node (ref "R1_11") (pin "2") (pinfunction "2_2") (pintype "passive"))
      (node (ref "U1_11") (pin "44") (pinfunction "RSTN_44") (pintype "passive"))
    )
    (net (code "108") (name "/RESET12") (class "Default")
      (node (ref "C10_12") (pin "1") (pinfunction "1_1") (pintype "passive"))
      (node (ref "R1_12") (pin "2") (pinfunction "2_2") (pintype "passive"))
      (node (ref "U1_12") (pin "44") (pinfunction "RSTN_44") (pintype "passive"))
    )
    (net (code "109") (name "/RESET13") (class "Default")
      (node (ref "C10_13") (pin "1") (pinfunction "1_1") (pintype "passive"))
      (node (ref "R1_13") (pin "2") (pinfunction "2_2") (pintype "passive"))
      (node (ref "U1_13") (pin "44") (pinfunction "RSTN_44") (pintype "passive"))
    )
    (net (code "110") (name "/RESET14") (class "Default")
      (node (ref "C10_14") (pin "1") (pinfunction "1_1") (pintype "passive"))
      (node (ref "R1_14") (pin "2") (pinfunction "2_2") (pintype "passive"))
      (node (ref "U1_14") (pin "44") (pinfunction "RSTN_44") (pintype "passive"))
    )
    (net (code "111") (name "/RESET15") (class "Default")
      (node (ref "C10_15") (pin "1") (pinfunction "1_1") (pintype "passive"))
      (node (ref "R1_15") (pin "2") (pinfunction "2_2") (pintype "passive"))
      (node (ref "U1_15") (pin "44") (pinfunction "RSTN_44") (pintype "passive"))
    )
    (net (code "112") (name "/RESET16") (class "Default")
      (node (ref "C10_16") (pin "1") (pinfunction "1_1") (pintype "passive"))
      (node (ref "R1_16") (pin "2") (pinfunction "2_2") (pintype "passive"))
      (node (ref "U1_16") (pin "44") (pinfunction "RSTN_44") (pintype "passive"))
    )
    (net (code "113") (name "/RPM") (class "Default")
      (node (ref "R44") (pin "1") (pinfunction "1_1") (pintype "passive"))
      (node (ref "R45") (pin "2") (pinfunction "2_2") (pintype "passive"))
      (node (ref "U1") (pin "60") (pinfunction "AN24/PWM1L/PMD0/RP80/RE0_60") (pintype "passive"))
    )
    (net (code "114") (name "/RPMF") (class "Default")
      (node (ref "J6") (pin "3") (pinfunction "3_3") (pintype "passive"))
      (node (ref "R44") (pin "2") (pinfunction "2_2") (pintype "passive"))
    )
    (net (code "115") (name "/SWN3") (class "Default")
      (node (ref "C312") (pin "2") (pinfunction "2_2") (pintype "passive"))
      (node (ref "L2") (pin "1") (pinfunction "1_1") (pintype "passive"))
      (node (ref "Q4") (pin "1") (pinfunction "S_1") (pintype "passive"))
      (node (ref "Q4") (pin "2") (pinfunction "S_2") (pintype "passive"))
      (node (ref "Q4") (pin "3") (pinfunction "S_3") (pintype "passive"))
      (node (ref "Q5") (pin "5") (pinfunction "D_5") (pintype "passive"))
      (node (ref "Q5") (pin "6") (pinfunction "D_6") (pintype "passive"))
      (node (ref "Q5") (pin "7") (pinfunction "D_7") (pintype "passive"))
      (node (ref "Q5") (pin "8") (pinfunction "D_8") (pintype "passive"))
      (node (ref "Q6") (pin "5") (pinfunction "D_5") (pintype "passive"))
      (node (ref "Q6") (pin "6") (pinfunction "D_6") (pintype "passive"))
      (node (ref "Q6") (pin "7") (pinfunction "D_7") (pintype "passive"))
      (node (ref "Q6") (pin "8") (pinfunction "D_8") (pintype "passive"))
      (node (ref "U30") (pin "2") (pinfunction "SW_2") (pintype "passive"))
    )
    (net (code "116") (name "/SWN4") (class "Default")
      (node (ref "C189") (pin "2") (pinfunction "2_2") (pintype "passive"))
      (node (ref "L1") (pin "1") (pinfunction "1_1") (pintype "passive"))
      (node (ref "Q1") (pin "1") (pinfunction "S_1") (pintype "passive"))
      (node (ref "Q1") (pin "2") (pinfunction "S_2") (pintype "passive"))
      (node (ref "Q1") (pin "3") (pinfunction "S_3") (pintype "passive"))
      (node (ref "Q2") (pin "5") (pinfunction "D_5") (pintype "passive"))
      (node (ref "Q2") (pin "6") (pinfunction "D_6") (pintype "passive"))
      (node (ref "Q2") (pin "7") (pinfunction "D_7") (pintype "passive"))
      (node (ref "Q2") (pin "8") (pinfunction "D_8") (pintype "passive"))
      (node (ref "Q3") (pin "5") (pinfunction "D_5") (pintype "passive"))
      (node (ref "Q3") (pin "6") (pinfunction "D_6") (pintype "passive"))
      (node (ref "Q3") (pin "7") (pinfunction "D_7") (pintype "passive"))
      (node (ref "Q3") (pin "8") (pinfunction "D_8") (pintype "passive"))
      (node (ref "R36") (pin "2") (pinfunction "2_2") (pintype "passive"))
      (node (ref "U25") (pin "2") (pinfunction "SW_2") (pintype "passive"))
    )
    (net (code "117") (name "/U2Rx") (class "Default")
      (node (ref "U1") (pin "31") (pinfunction "SDA2/PMA9/RP100/RF4_31") (pintype "passive"))
    )
    (net (code "118") (name "/U2Tx") (class "Default")
      (node (ref "U1") (pin "32") (pinfunction "SCL2/PMA8/RP101/RF5_32") (pintype "passive"))
    )
    (net (code "119") (name "/USB5.0V") (class "Default")
      (node (ref "J3") (pin "1") (pinfunction "1_1") (pintype "passive"))
      (node (ref "R46") (pin "2") (pinfunction "2_2") (pintype "passive"))
      (node (ref "R56") (pin "2") (pinfunction "2_2") (pintype "passive"))
    )
    (net (code "120") (name "/USBDM{slash}D-") (class "Default")
      (node (ref "J3") (pin "2") (pinfunction "2_2") (pintype "passive"))
      (node (ref "R34") (pin "1") (pinfunction "1_1") (pintype "passive"))
    )
    (net (code "121") (name "/USBDP{slash}D+") (class "Default")
      (node (ref "J3") (pin "3") (pinfunction "3_3") (pintype "passive"))
      (node (ref "R35") (pin "1") (pinfunction "1_1") (pintype "passive"))
    )
    (net (code "122") (name "/USBMCU5.0V") (class "Default")
      (node (ref "R56") (pin "1") (pinfunction "1_1") (pintype "passive"))
      (node (ref "R62") (pin "1") (pinfunction "1_1") (pintype "passive"))
      (node (ref "U1") (pin "34") (pinfunction "VBUS_34") (pintype "passive"))
    )
    (net (code "123") (name "/VCAP") (class "Default")
      (node (ref "C17") (pin "1") (pinfunction "1_1") (pintype "passive"))
      (node (ref "U1") (pin "56") (pinfunction "VCAP_56") (pintype "passive"))
    )
    (net (code "124") (name "/XCLK1") (class "Default")
      (node (ref "Q7") (pin "1") (pinfunction "B_1") (pintype "passive"))
      (node (ref "R2") (pin "2") (pinfunction "2_2") (pintype "passive"))
      (node (ref "U1") (pin "46") (pinfunction "INT0/DMH/RP64/RD0_46") (pintype "passive"))
      (node (ref "U1") (pin "49") (pinfunction "VCPCON/RP65/RD1_49") (pintype "passive"))
      (node (ref "U1") (pin "52") (pinfunction "PMWR/RP68/RD4_52") (pintype "passive"))
      (node (ref "U1") (pin "53") (pinfunction "PMRD/RP69/RD5_53") (pintype "passive"))
      (node (ref "U2") (pin "1") (pinfunction "1B_1") (pintype "passive"))
      (node (ref "U3") (pin "2") (pinfunction "1A_2") (pintype "passive"))
    )
    (net (code "125") (name "/XCLKIN") (class "Default")
      (node (ref "Q7") (pin "3") (pinfunction "C_3") (pintype "passive"))
      (node (ref "R1") (pin "2") (pinfunction "2_2") (pintype "passive"))
      (node (ref "R2") (pin "1") (pinfunction "1_1") (pintype "passive"))
      (node (ref "U1_1") (pin "9") (pinfunction "XCLKIN_9") (pintype "passive"))
      (node (ref "U1_10") (pin "9") (pinfunction "XCLKIN_9") (pintype "passive"))
      (node (ref "U1_11") (pin "9") (pinfunction "XCLKIN_9") (pintype "passive"))
      (node (ref "U1_12") (pin "9") (pinfunction "XCLKIN_9") (pintype "passive"))
      (node (ref "U1_13") (pin "9") (pinfunction "XCLKIN_9") (pintype "passive"))
      (node (ref "U1_14") (pin "9") (pinfunction "XCLKIN_9") (pintype "passive"))
      (node (ref "U1_15") (pin "9") (pinfunction "XCLKIN_9") (pintype "passive"))
      (node (ref "U1_16") (pin "9") (pinfunction "XCLKIN_9") (pintype "passive"))
      (node (ref "U1_2") (pin "9") (pinfunction "XCLKIN_9") (pintype "passive"))
      (node (ref "U1_3") (pin "9") (pinfunction "XCLKIN_9") (pintype "passive"))
      (node (ref "U1_4") (pin "9") (pinfunction "XCLKIN_9") (pintype "passive"))
      (node (ref "U1_5") (pin "9") (pinfunction "XCLKIN_9") (pintype "passive"))
      (node (ref "U1_6") (pin "9") (pinfunction "XCLKIN_9") (pintype "passive"))
      (node (ref "U1_7") (pin "9") (pinfunction "XCLKIN_9") (pintype "passive"))
      (node (ref "U1_8") (pin "9") (pinfunction "XCLKIN_9") (pintype "passive"))
      (node (ref "U1_9") (pin "9") (pinfunction "XCLKIN_9") (pintype "passive"))
      (node (ref "U2") (pin "4") (pinfunction "1Y_4") (pintype "passive"))
      (node (ref "U3") (pin "1") (pinfunction "1Y_1") (pintype "passive"))
    )
    (net (code "126") (name "/YELLOW") (class "Default")
      (node (ref "D6") (pin "2") (pinfunction "A_2") (pintype "passive"))
      (node (ref "U1") (pin "44") (pinfunction "ASCL1/PMCS2/RPI74/RD10_44") (pintype "passive"))
    )
    (net (code "127") (name "GND") (class "Default")
      (node (ref "C10_1") (pin "2") (pinfunction "2_2") (pintype "passive"))
      (node (ref "C10_10") (pin "2") (pinfunction "2_2") (pintype "passive"))
      (node (ref "C10_11") (pin "2") (pinfunction "2_2") (pintype "passive"))
      (node (ref "C10_12") (pin "2") (pinfunction "2_2") (pintype "passive"))
      (node (ref "C10_13") (pin "2") (pinfunction "2_2") (pintype "passive"))
      (node (ref "C10_14") (pin "2") (pinfunction "2_2") (pintype "passive"))
      (node (ref "C10_15") (pin "2") (pinfunction "2_2") (pintype "passive"))
      (node (ref "C10_16") (pin "2") (pinfunction "2_2") (pintype "passive"))
      (node (ref "C10_2") (pin "2") (pinfunction "2_2") (pintype "passive"))
      (node (ref "C10_3") (pin "2") (pinfunction "2_2") (pintype "passive"))
      (node (ref "C10_4") (pin "2") (pinfunction "2_2") (pintype "passive"))
      (node (ref "C10_5") (pin "2") (pinfunction "2_2") (pintype "passive"))
      (node (ref "C10_6") (pin "2") (pinfunction "2_2") (pintype "passive"))
      (node (ref "C10_7") (pin "2") (pinfunction "2_2") (pintype "passive"))
      (node (ref "C10_8") (pin "2") (pinfunction "2_2") (pintype "passive"))
      (node (ref "C10_9") (pin "2") (pinfunction "2_2") (pintype "passive"))
      (node (ref "C11_1") (pin "2") (pinfunction "2_2") (pintype "passive"))
      (node (ref "C11_10") (pin "2") (pinfunction "2_2") (pintype "passive"))
      (node (ref "C11_11") (pin "2") (pinfunction "2_2") (pintype "passive"))
      (node (ref "C11_12") (pin "2") (pinfunction "2_2") (pintype "passive"))
      (node (ref "C11_13") (pin "2") (pinfunction "2_2") (pintype "passive"))
      (node (ref "C11_14") (pin "2") (pinfunction "2_2") (pintype "passive"))
      (node (ref "C11_15") (pin "2") (pinfunction "2_2") (pintype "passive"))
      (node (ref "C11_16") (pin "2") (pinfunction "2_2") (pintype "passive"))
      (node (ref "C11_2") (pin "2") (pinfunction "2_2") (pintype "passive"))
      (node (ref "C11_3") (pin "2") (pinfunction "2_2") (pintype "passive"))
      (node (ref "C11_4") (pin "2") (pinfunction "2_2") (pintype "passive"))
      (node (ref "C11_5") (pin "2") (pinfunction "2_2") (pintype "passive"))
      (node (ref "C11_6") (pin "2") (pinfunction "2_2") (pintype "passive"))
      (node (ref "C11_7") (pin "2") (pinfunction "2_2") (pintype "passive"))
      (node (ref "C11_8") (pin "2") (pinfunction "2_2") (pintype "passive"))
      (node (ref "C11_9") (pin "2") (pinfunction "2_2") (pintype "passive"))
      (node (ref "C17") (pin "2") (pinfunction "2_2") (pintype "passive"))
      (node (ref "C187") (pin "2") (pinfunction "2_2") (pintype "passive"))
      (node (ref "C188") (pin "1") (pinfunction "1_1") (pintype "passive"))
      (node (ref "C190") (pin "2") (pinfunction "2_2") (pintype "passive"))
      (node (ref "C191") (pin "2") (pinfunction "2_2") (pintype "passive"))
      (node (ref "C192") (pin "2") (pinfunction "2_2") (pintype "passive"))
      (node (ref "C193") (pin "2") (pinfunction "2_2") (pintype "passive"))
      (node (ref "C194") (pin "2") (pinfunction "2_2") (pintype "passive"))
      (node (ref "C195") (pin "2") (pinfunction "2_2") (pintype "passive"))
      (node (ref "C196") (pin "2") (pinfunction "2_2") (pintype "passive"))
      (node (ref "C197") (pin "2") (pinfunction "2_2") (pintype "passive"))
      (node (ref "C198") (pin "2") (pinfunction "2_2") (pintype "passive"))
      (node (ref "C199") (pin "2") (pinfunction "2_2") (pintype "passive"))
      (node (ref "C1_1") (pin "2") (pinfunction "2_2") (pintype "passive"))
      (node (ref "C1_10") (pin "2") (pinfunction "2_2") (pintype "passive"))
      (node (ref "C1_11") (pin "2") (pinfunction "2_2") (pintype "passive"))
      (node (ref "C1_12") (pin "2") (pinfunction "2_2") (pintype "passive"))
      (node (ref "C1_13") (pin "2") (pinfunction "2_2") (pintype "passive"))
      (node (ref "C1_14") (pin "2") (pinfunction "2_2") (pintype "passive"))
      (node (ref "C1_15") (pin "2") (pinfunction "2_2") (pintype "passive"))
      (node (ref "C1_16") (pin "2") (pinfunction "2_2") (pintype "passive"))
      (node (ref "C1_2") (pin "2") (pinfunction "2_2") (pintype "passive"))
      (node (ref "C1_3") (pin "2") (pinfunction "2_2") (pintype "passive"))
      (node (ref "C1_4") (pin "2") (pinfunction "2_2") (pintype "passive"))
      (node (ref "C1_5") (pin "2") (pinfunction "2_2") (pintype "passive"))
      (node (ref "C1_6") (pin "2") (pinfunction "2_2") (pintype "passive"))
      (node (ref "C1_7") (pin "2") (pinfunction "2_2") (pintype "passive"))
      (node (ref "C1_8") (pin "2") (pinfunction "2_2") (pintype "passive"))
      (node (ref "C1_9") (pin "2") (pinfunction "2_2") (pintype "passive"))
      (node (ref "C200") (pin "2") (pinfunction "2_2") (pintype "passive"))
      (node (ref "C201") (pin "2") (pinfunction "2_2") (pintype "passive"))
      (node (ref "C202") (pin "2") (pinfunction "2_2") (pintype "passive"))
      (node (ref "C203") (pin "2") (pinfunction "2_2") (pintype "passive"))
      (node (ref "C204") (pin "2") (pinfunction "2_2") (pintype "passive"))
      (node (ref "C205") (pin "2") (pinfunction "2_2") (pintype "passive"))
      (node (ref "C207") (pin "2") (pinfunction "2_2") (pintype "passive"))
      (node (ref "C211") (pin "2") (pinfunction "2_2") (pintype "passive"))
      (node (ref "C212") (pin "2") (pinfunction "2_2") (pintype "passive"))
      (node (ref "C213") (pin "2") (pinfunction "2_2") (pintype "passive"))
      (node (ref "C214") (pin "2") (pinfunction "2_2") (pintype "passive"))
      (node (ref "C215") (pin "2") (pinfunction "2_2") (pintype "passive"))
      (node (ref "C216") (pin "2") (pinfunction "2_2") (pintype "passive"))
      (node (ref "C217") (pin "2") (pinfunction "2_2") (pintype "passive"))
      (node (ref "C218") (pin "2") (pinfunction "2_2") (pintype "passive"))
      (node (ref "C219") (pin "2") (pinfunction "2_2") (pintype "passive"))
      (node (ref "C220") (pin "2") (pinfunction "2_2") (pintype "passive"))
      (node (ref "C221") (pin "2") (pinfunction "2_2") (pintype "passive"))
      (node (ref "C222") (pin "2") (pinfunction "2_2") (pintype "passive"))
      (node (ref "C223") (pin "2") (pinfunction "2_2") (pintype "passive"))
      (node (ref "C224") (pin "2") (pinfunction "2_2") (pintype "passive"))
      (node (ref "C225") (pin "2") (pinfunction "2_2") (pintype "passive"))
      (node (ref "C226") (pin "2") (pinfunction "2_2") (pintype "passive"))
      (node (ref "C227") (pin "2") (pinfunction "2_2") (pintype "passive"))
      (node (ref "C228") (pin "2") (pinfunction "2_2") (pintype "passive"))
      (node (ref "C229") (pin "2") (pinfunction "2_2") (pintype "passive"))
      (node (ref "C230") (pin "2") (pinfunction "2_2") (pintype "passive"))
      (node (ref "C231") (pin "2") (pinfunction "2_2") (pintype "passive"))
      (node (ref "C232") (pin "2") (pinfunction "2_2") (pintype "passive"))
      (node (ref "C233") (pin "2") (pinfunction "2_2") (pintype "passive"))
      (node (ref "C234") (pin "2") (pinfunction "2_2") (pintype "passive"))
      (node (ref "C235") (pin "2") (pinfunction "2_2") (pintype "passive"))
      (node (ref "C236") (pin "2") (pinfunction "2_2") (pintype "passive"))
      (node (ref "C237") (pin "2") (pinfunction "2_2") (pintype "passive"))
      (node (ref "C238") (pin "2") (pinfunction "2_2") (pintype "passive"))
      (node (ref "C239") (pin "2") (pinfunction "2_2") (pintype "passive"))
      (node (ref "C240") (pin "2") (pinfunction "2_2") (pintype "passive"))
      (node (ref "C241") (pin "2") (pinfunction "2_2") (pintype "passive"))
      (node (ref "C242") (pin "2") (pinfunction "2_2") (pintype "passive"))
      (node (ref "C243") (pin "2") (pinfunction "2_2") (pintype "passive"))
      (node (ref "C244") (pin "2") (pinfunction "2_2") (pintype "passive"))
      (node (ref "C245") (pin "2") (pinfunction "2_2") (pintype "passive"))
      (node (ref "C246") (pin "2") (pinfunction "2_2") (pintype "passive"))
      (node (ref "C247") (pin "2") (pinfunction "2_2") (pintype "passive"))
      (node (ref "C248") (pin "2") (pinfunction "2_2") (pintype "passive"))
      (node (ref "C249") (pin "2") (pinfunction "2_2") (pintype "passive"))
      (node (ref "C250") (pin "2") (pinfunction "2_2") (pintype "passive"))
      (node (ref "C251") (pin "2") (pinfunction "2_2") (pintype "passive"))
      (node (ref "C252") (pin "2") (pinfunction "2_2") (pintype "passive"))
      (node (ref "C253") (pin "1") (pinfunction "1_1") (pintype "passive"))
      (node (ref "C254") (pin "1") (pinfunction "1_1") (pintype "passive"))
      (node (ref "C256") (pin "2") (pinfunction "2_2") (pintype "passive"))
      (node (ref "C257") (pin "2") (pinfunction "2_2") (pintype "passive"))
      (node (ref "C258") (pin "2") (pinfunction "2_2") (pintype "passive"))
      (node (ref "C259") (pin "2") (pinfunction "2_2") (pintype "passive"))
      (node (ref "C260") (pin "2") (pinfunction "2_2") (pintype "passive"))
      (node (ref "C261") (pin "2") (pinfunction "2_2") (pintype "passive"))
      (node (ref "C262") (pin "2") (pinfunction "2_2") (pintype "passive"))
      (node (ref "C263") (pin "2") (pinfunction "2_2") (pintype "passive"))
      (node (ref "C264") (pin "2") (pinfunction "2_2") (pintype "passive"))
      (node (ref "C265") (pin "2") (pinfunction "2_2") (pintype "passive"))
      (node (ref "C266") (pin "2") (pinfunction "2_2") (pintype "passive"))
      (node (ref "C267") (pin "2") (pinfunction "2_2") (pintype "passive"))
      (node (ref "C268") (pin "2") (pinfunction "2_2") (pintype "passive"))
      (node (ref "C269") (pin "2") (pinfunction "2_2") (pintype "passive"))
      (node (ref "C270") (pin "2") (pinfunction "2_2") (pintype "passive"))
      (node (ref "C271") (pin "2") (pinfunction "2_2") (pintype "passive"))
      (node (ref "C273") (pin "2") (pinfunction "2_2") (pintype "passive"))
      (node (ref "C274") (pin "2") (pinfunction "2_2") (pintype "passive"))
      (node (ref "C275") (pin "2") (pinfunction "2_2") (pintype "passive"))
      (node (ref "C276") (pin "2") (pinfunction "2_2") (pintype "passive"))
      (node (ref "C277") (pin "2") (pinfunction "2_2") (pintype "passive"))
      (node (ref "C278") (pin "2") (pinfunction "2_2") (pintype "passive"))
      (node (ref "C279") (pin "2") (pinfunction "2_2") (pintype "passive"))
      (node (ref "C280") (pin "2") (pinfunction "2_2") (pintype "passive"))
      (node (ref "C282") (pin "2") (pinfunction "2_2") (pintype "passive"))
      (node (ref "C283") (pin "2") (pinfunction "2_2") (pintype "passive"))
      (node (ref "C284") (pin "2") (pinfunction "2_2") (pintype "passive"))
      (node (ref "C285") (pin "2") (pinfunction "2_2") (pintype "passive"))
      (node (ref "C286") (pin "2") (pinfunction "2_2") (pintype "passive"))
      (node (ref "C287") (pin "2") (pinfunction "2_2") (pintype "passive"))
      (node (ref "C288") (pin "2") (pinfunction "2_2") (pintype "passive"))
      (node (ref "C289") (pin "2") (pinfunction "2_2") (pintype "passive"))
      (node (ref "C290") (pin "2") (pinfunction "2_2") (pintype "passive"))
      (node (ref "C291") (pin "2") (pinfunction "2_2") (pintype "passive"))
      (node (ref "C292") (pin "2") (pinfunction "2_2") (pintype "passive"))
      (node (ref "C293") (pin "2") (pinfunction "2_2") (pintype "passive"))
      (node (ref "C294") (pin "2") (pinfunction "2_2") (pintype "passive"))
      (node (ref "C295") (pin "2") (pinfunction "2_2") (pintype "passive"))
      (node (ref "C296") (pin "2") (pinfunction "2_2") (pintype "passive"))
      (node (ref "C297") (pin "2") (pinfunction "2_2") (pintype "passive"))
      (node (ref "C298") (pin "2") (pinfunction "2_2") (pintype "passive"))
      (node (ref "C299") (pin "2") (pinfunction "2_2") (pintype "passive"))
      (node (ref "C2_1") (pin "2") (pinfunction "2_2") (pintype "passive"))
      (node (ref "C2_10") (pin "2") (pinfunction "2_2") (pintype "passive"))
      (node (ref "C2_11") (pin "2") (pinfunction "2_2") (pintype "passive"))
      (node (ref "C2_12") (pin "2") (pinfunction "2_2") (pintype "passive"))
      (node (ref "C2_13") (pin "2") (pinfunction "2_2") (pintype "passive"))
      (node (ref "C2_14") (pin "2") (pinfunction "2_2") (pintype "passive"))
      (node (ref "C2_15") (pin "2") (pinfunction "2_2") (pintype "passive"))
      (node (ref "C2_16") (pin "2") (pinfunction "2_2") (pintype "passive"))
      (node (ref "C2_2") (pin "2") (pinfunction "2_2") (pintype "passive"))
      (node (ref "C2_3") (pin "2") (pinfunction "2_2") (pintype "passive"))
      (node (ref "C2_4") (pin "2") (pinfunction "2_2") (pintype "passive"))
      (node (ref "C2_5") (pin "2") (pinfunction "2_2") (pintype "passive"))
      (node (ref "C2_6") (pin "2") (pinfunction "2_2") (pintype "passive"))
      (node (ref "C2_7") (pin "2") (pinfunction "2_2") (pintype "passive"))
      (node (ref "C2_8") (pin "2") (pinfunction "2_2") (pintype "passive"))
      (node (ref "C2_9") (pin "2") (pinfunction "2_2") (pintype "passive"))
      (node (ref "C300") (pin "2") (pinfunction "2_2") (pintype "passive"))
      (node (ref "C301") (pin "2") (pinfunction "2_2") (pintype "passive"))
      (node (ref "C302") (pin "2") (pinfunction "2_2") (pintype "passive"))
      (node (ref "C303") (pin "2") (pinfunction "2_2") (pintype "passive"))
      (node (ref "C304") (pin "2") (pinfunction "2_2") (pintype "passive"))
      (node (ref "C305") (pin "2") (pinfunction "2_2") (pintype "passive"))
      (node (ref "C306") (pin "2") (pinfunction "2_2") (pintype "passive"))
      (node (ref "C307") (pin "2") (pinfunction "2_2") (pintype "passive"))
      (node (ref "C308") (pin "1") (pinfunction "1_1") (pintype "passive"))
      (node (ref "C309") (pin "2") (pinfunction "2_2") (pintype "passive"))
      (node (ref "C311") (pin "2") (pinfunction "2_2") (pintype "passive"))
      (node (ref "C313") (pin "2") (pinfunction "2_2") (pintype "passive"))
      (node (ref "C314") (pin "2") (pinfunction "2_2") (pintype "passive"))
      (node (ref "C315") (pin "2") (pinfunction "2_2") (pintype "passive"))
      (node (ref "C316") (pin "2") (pinfunction "2_2") (pintype "passive"))
      (node (ref "C317") (pin "2") (pinfunction "2_2") (pintype "passive"))
      (node (ref "C318") (pin "2") (pinfunction "2_2") (pintype "passive"))
      (node (ref "C319") (pin "2") (pinfunction "2_2") (pintype "passive"))
      (node (ref "C320") (pin "2") (pinfunction "2_2") (pintype "passive"))
      (node (ref "C321") (pin "2") (pinfunction "2_2") (pintype "passive"))
      (node (ref "C322") (pin "2") (pinfunction "2_2") (pintype "passive"))
      (node (ref "C323") (pin "2") (pinfunction "2_2") (pintype "passive"))
      (node (ref "C324") (pin "2") (pinfunction "2_2") (pintype "passive"))
      (node (ref "C325") (pin "2") (pinfunction "2_2") (pintype "passive"))
      (node (ref "C34") (pin "2") (pinfunction "2_2") (pintype "passive"))
      (node (ref "C3_1") (pin "2") (pinfunction "2_2") (pintype "passive"))
      (node (ref "C3_10") (pin "2") (pinfunction "2_2") (pintype "passive"))
      (node (ref "C3_11") (pin "2") (pinfunction "2_2") (pintype "passive"))
      (node (ref "C3_12") (pin "2") (pinfunction "2_2") (pintype "passive"))
      (node (ref "C3_13") (pin "2") (pinfunction "2_2") (pintype "passive"))
      (node (ref "C3_14") (pin "2") (pinfunction "2_2") (pintype "passive"))
      (node (ref "C3_15") (pin "2") (pinfunction "2_2") (pintype "passive"))
      (node (ref "C3_16") (pin "2") (pinfunction "2_2") (pintype "passive"))
      (node (ref "C3_2") (pin "2") (pinfunction "2_2") (pintype "passive"))
      (node (ref "C3_3") (pin "2") (pinfunction "2_2") (pintype "passive"))
      (node (ref "C3_4") (pin "2") (pinfunction "2_2") (pintype "passive"))
      (node (ref "C3_5") (pin "2") (pinfunction "2_2") (pintype "passive"))
      (node (ref "C3_6") (pin "2") (pinfunction "2_2") (pintype "passive"))
      (node (ref "C3_7") (pin "2") (pinfunction "2_2") (pintype "passive"))
      (node (ref "C3_8") (pin "2") (pinfunction "2_2") (pintype "passive"))
      (node (ref "C3_9") (pin "2") (pinfunction "2_2") (pintype "passive"))
      (node (ref "C4_1") (pin "2") (pinfunction "2_2") (pintype "passive"))
      (node (ref "C4_10") (pin "2") (pinfunction "2_2") (pintype "passive"))
      (node (ref "C4_11") (pin "2") (pinfunction "2_2") (pintype "passive"))
      (node (ref "C4_12") (pin "2") (pinfunction "2_2") (pintype "passive"))
      (node (ref "C4_13") (pin "2") (pinfunction "2_2") (pintype "passive"))
      (node (ref "C4_14") (pin "2") (pinfunction "2_2") (pintype "passive"))
      (node (ref "C4_15") (pin "2") (pinfunction "2_2") (pintype "passive"))
      (node (ref "C4_16") (pin "2") (pinfunction "2_2") (pintype "passive"))
      (node (ref "C4_2") (pin "2") (pinfunction "2_2") (pintype "passive"))
      (node (ref "C4_3") (pin "2") (pinfunction "2_2") (pintype "passive"))
      (node (ref "C4_4") (pin "2") (pinfunction "2_2") (pintype "passive"))
      (node (ref "C4_5") (pin "2") (pinfunction "2_2") (pintype "passive"))
      (node (ref "C4_6") (pin "2") (pinfunction "2_2") (pintype "passive"))
      (node (ref "C4_7") (pin "2") (pinfunction "2_2") (pintype "passive"))
      (node (ref "C4_8") (pin "2") (pinfunction "2_2") (pintype "passive"))
      (node (ref "C4_9") (pin "2") (pinfunction "2_2") (pintype "passive"))
      (node (ref "C5_1") (pin "1") (pinfunction "1_1") (pintype "passive"))
      (node (ref "C5_10") (pin "1") (pinfunction "1_1") (pintype "passive"))
      (node (ref "C5_11") (pin "1") (pinfunction "1_1") (pintype "passive"))
      (node (ref "C5_12") (pin "1") (pinfunction "1_1") (pintype "passive"))
      (node (ref "C5_13") (pin "1") (pinfunction "1_1") (pintype "passive"))
      (node (ref "C5_14") (pin "1") (pinfunction "1_1") (pintype "passive"))
      (node (ref "C5_15") (pin "1") (pinfunction "1_1") (pintype "passive"))
      (node (ref "C5_16") (pin "1") (pinfunction "1_1") (pintype "passive"))
      (node (ref "C5_2") (pin "1") (pinfunction "1_1") (pintype "passive"))
      (node (ref "C5_3") (pin "1") (pinfunction "1_1") (pintype "passive"))
      (node (ref "C5_4") (pin "1") (pinfunction "1_1") (pintype "passive"))
      (node (ref "C5_5") (pin "1") (pinfunction "1_1") (pintype "passive"))
      (node (ref "C5_6") (pin "1") (pinfunction "1_1") (pintype "passive"))
      (node (ref "C5_7") (pin "1") (pinfunction "1_1") (pintype "passive"))
      (node (ref "C5_8") (pin "1") (pinfunction "1_1") (pintype "passive"))
      (node (ref "C5_9") (pin "1") (pinfunction "1_1") (pintype "passive"))
      (node (ref "C63") (pin "2") (pinfunction "2_2") (pintype "passive"))
      (node (ref "C6_1") (pin "2") (pinfunction "2_2") (pintype "passive"))
      (node (ref "C6_10") (pin "2") (pinfunction "2_2") (pintype "passive"))
      (node (ref "C6_11") (pin "2") (pinfunction "2_2") (pintype "passive"))
      (node (ref "C6_12") (pin "2") (pinfunction "2_2") (pintype "passive"))
      (node (ref "C6_13") (pin "2") (pinfunction "2_2") (pintype "passive"))
      (node (ref "C6_14") (pin "2") (pinfunction "2_2") (pintype "passive"))
      (node (ref "C6_15") (pin "2") (pinfunction "2_2") (pintype "passive"))
      (node (ref "C6_16") (pin "2") (pinfunction "2_2") (pintype "passive"))
      (node (ref "C6_2") (pin "2") (pinfunction "2_2") (pintype "passive"))
      (node (ref "C6_3") (pin "2") (pinfunction "2_2") (pintype "passive"))
      (node (ref "C6_4") (pin "2") (pinfunction "2_2") (pintype "passive"))
      (node (ref "C6_5") (pin "2") (pinfunction "2_2") (pintype "passive"))
      (node (ref "C6_6") (pin "2") (pinfunction "2_2") (pintype "passive"))
      (node (ref "C6_7") (pin "2") (pinfunction "2_2") (pintype "passive"))
      (node (ref "C6_8") (pin "2") (pinfunction "2_2") (pintype "passive"))
      (node (ref "C6_9") (pin "2") (pinfunction "2_2") (pintype "passive"))
      (node (ref "C72") (pin "2") (pinfunction "2_2") (pintype "passive"))
      (node (ref "C73") (pin "2") (pinfunction "2_2") (pintype "passive"))
      (node (ref "C74") (pin "2") (pinfunction "2_2") (pintype "passive"))
      (node (ref "C75") (pin "2") (pinfunction "2_2") (pintype "passive"))
      (node (ref "C76") (pin "2") (pinfunction "2_2") (pintype "passive"))
      (node (ref "C7_1") (pin "2") (pinfunction "2_2") (pintype "passive"))
      (node (ref "C7_10") (pin "2") (pinfunction "2_2") (pintype "passive"))
      (node (ref "C7_11") (pin "2") (pinfunction "2_2") (pintype "passive"))
      (node (ref "C7_12") (pin "2") (pinfunction "2_2") (pintype "passive"))
      (node (ref "C7_13") (pin "2") (pinfunction "2_2") (pintype "passive"))
      (node (ref "C7_14") (pin "2") (pinfunction "2_2") (pintype "passive"))
      (node (ref "C7_15") (pin "2") (pinfunction "2_2") (pintype "passive"))
      (node (ref "C7_16") (pin "2") (pinfunction "2_2") (pintype "passive"))
      (node (ref "C7_2") (pin "2") (pinfunction "2_2") (pintype "passive"))
      (node (ref "C7_3") (pin "2") (pinfunction "2_2") (pintype "passive"))
      (node (ref "C7_4") (pin "2") (pinfunction "2_2") (pintype "passive"))
      (node (ref "C7_5") (pin "2") (pinfunction "2_2") (pintype "passive"))
      (node (ref "C7_6") (pin "2") (pinfunction "2_2") (pintype "passive"))
      (node (ref "C7_7") (pin "2") (pinfunction "2_2") (pintype "passive"))
      (node (ref "C7_8") (pin "2") (pinfunction "2_2") (pintype "passive"))
      (node (ref "C7_9") (pin "2") (pinfunction "2_2") (pintype "passive"))
      (node (ref "C85") (pin "2") (pinfunction "2_2") (pintype "passive"))
      (node (ref "C86") (pin "2") (pinfunction "2_2") (pintype "passive"))
      (node (ref "C8_1") (pin "2") (pinfunction "2_2") (pintype "passive"))
      (node (ref "C8_10") (pin "2") (pinfunction "2_2") (pintype "passive"))
      (node (ref "C8_11") (pin "2") (pinfunction "2_2") (pintype "passive"))
      (node (ref "C8_12") (pin "2") (pinfunction "2_2") (pintype "passive"))
      (node (ref "C8_13") (pin "2") (pinfunction "2_2") (pintype "passive"))
      (node (ref "C8_14") (pin "2") (pinfunction "2_2") (pintype "passive"))
      (node (ref "C8_15") (pin "2") (pinfunction "2_2") (pintype "passive"))
      (node (ref "C8_16") (pin "2") (pinfunction "2_2") (pintype "passive"))
      (node (ref "C8_2") (pin "2") (pinfunction "2_2") (pintype "passive"))
      (node (ref "C8_3") (pin "2") (pinfunction "2_2") (pintype "passive"))
      (node (ref "C8_4") (pin "2") (pinfunction "2_2") (pintype "passive"))
      (node (ref "C8_5") (pin "2") (pinfunction "2_2") (pintype "passive"))
      (node (ref "C8_6") (pin "2") (pinfunction "2_2") (pintype "passive"))
      (node (ref "C8_7") (pin "2") (pinfunction "2_2") (pintype "passive"))
      (node (ref "C8_8") (pin "2") (pinfunction "2_2") (pintype "passive"))
      (node (ref "C8_9") (pin "2") (pinfunction "2_2") (pintype "passive"))
      (node (ref "C9_1") (pin "2") (pinfunction "2_2") (pintype "passive"))
      (node (ref "C9_10") (pin "2") (pinfunction "2_2") (pintype "passive"))
      (node (ref "C9_11") (pin "2") (pinfunction "2_2") (pintype "passive"))
      (node (ref "C9_12") (pin "2") (pinfunction "2_2") (pintype "passive"))
      (node (ref "C9_13") (pin "2") (pinfunction "2_2") (pintype "passive"))
      (node (ref "C9_14") (pin "2") (pinfunction "2_2") (pintype "passive"))
      (node (ref "C9_15") (pin "2") (pinfunction "2_2") (pintype "passive"))
      (node (ref "C9_16") (pin "2") (pinfunction "2_2") (pintype "passive"))
      (node (ref "C9_2") (pin "2") (pinfunction "2_2") (pintype "passive"))
      (node (ref "C9_3") (pin "2") (pinfunction "2_2") (pintype "passive"))
      (node (ref "C9_4") (pin "2") (pinfunction "2_2") (pintype "passive"))
      (node (ref "C9_5") (pin "2") (pinfunction "2_2") (pintype "passive"))
      (node (ref "C9_6") (pin "2") (pinfunction "2_2") (pintype "passive"))
      (node (ref "C9_7") (pin "2") (pinfunction "2_2") (pintype "passive"))
      (node (ref "C9_8") (pin "2") (pinfunction "2_2") (pintype "passive"))
      (node (ref "C9_9") (pin "2") (pinfunction "2_2") (pintype "passive"))
      (node (ref "D3") (pin "1") (pinfunction "A1_1") (pintype "passive"))
      (node (ref "D3") (pin "2") (pinfunction "A2_2") (pintype "passive"))
      (node (ref "D4") (pin "1") (pinfunction "C_1") (pintype "passive"))
      (node (ref "D5") (pin "1") (pinfunction "C_1") (pintype "passive"))
      (node (ref "D6") (pin "1") (pinfunction "C_1") (pintype "passive"))
      (node (ref "D7") (pin "1") (pinfunction "C_1") (pintype "passive"))
      (node (ref "J1") (pin "3") (pinfunction "3_3") (pintype "passive"))
      (node (ref "J2") (pin "2") (pinfunction "2_2") (pintype "passive"))
      (node (ref "J2") (pin "3") (pinfunction "3_3") (pintype "passive"))
      (node (ref "J3") (pin "5") (pinfunction "5_5") (pintype "passive"))
      (node (ref "J3") (pin "6") (pinfunction "6_6") (pintype "passive"))
      (node (ref "J3") (pin "7") (pinfunction "7_7") (pintype "passive"))
      (node (ref "J3") (pin "8") (pinfunction "8_8") (pintype "passive"))
      (node (ref "J3") (pin "9") (pinfunction "9_9") (pintype "passive"))
      (node (ref "J6") (pin "1") (pinfunction "1_1") (pintype "passive"))
      (node (ref "Q2") (pin "1") (pinfunction "S_1") (pintype "passive"))
      (node (ref "Q2") (pin "2") (pinfunction "S_2") (pintype "passive"))
      (node (ref "Q2") (pin "3") (pinfunction "S_3") (pintype "passive"))
      (node (ref "Q3") (pin "1") (pinfunction "S_1") (pintype "passive"))
      (node (ref "Q3") (pin "2") (pinfunction "S_2") (pintype "passive"))
      (node (ref "Q3") (pin "3") (pinfunction "S_3") (pintype "passive"))
      (node (ref "Q5") (pin "1") (pinfunction "S_1") (pintype "passive"))
      (node (ref "Q5") (pin "2") (pinfunction "S_2") (pintype "passive"))
      (node (ref "Q5") (pin "3") (pinfunction "S_3") (pintype "passive"))
      (node (ref "Q6") (pin "1") (pinfunction "S_1") (pintype "passive"))
      (node (ref "Q6") (pin "2") (pinfunction "S_2") (pintype "passive"))
      (node (ref "Q6") (pin "3") (pinfunction "S_3") (pintype "passive"))
      (node (ref "Q7") (pin "2") (pinfunction "E_2") (pintype "passive"))
      (node (ref "R40") (pin "1") (pinfunction "1_1") (pintype "passive"))
      (node (ref "R45") (pin "1") (pinfunction "1_1") (pintype "passive"))
      (node (ref "R59") (pin "1") (pinfunction "1_1") (pintype "passive"))
      (node (ref "R60") (pin "1") (pinfunction "1_1") (pintype "passive"))
      (node (ref "R61") (pin "1") (pinfunction "1_1") (pintype "passive"))
      (node (ref "U1") (pin "20") (pinfunction "AVSS_20") (pintype "passive"))
      (node (ref "U1") (pin "25") (pinfunction "VSS_25") (pintype "passive"))
      (node (ref "U1") (pin "41") (pinfunction "VSS_41") (pintype "passive"))
      (node (ref "U1") (pin "9") (pinfunction "VSS_9") (pintype "passive"))
      (node (ref "U19") (pin "6") (pinfunction "GND_6") (pintype "passive"))
      (node (ref "U19") (pin "7") (pinfunction "GND_7") (pintype "passive"))
      (node (ref "U1_1") (pin "12") (pinfunction "DVSS_12") (pintype "passive"))
      (node (ref "U1_1") (pin "23") (pinfunction "OVSS1_23") (pintype "passive"))
      (node (ref "U1_1") (pin "27") (pinfunction "DVSS_27") (pintype "passive"))
      (node (ref "U1_1") (pin "38") (pinfunction "OVSS0_38") (pintype "passive"))
      (node (ref "U1_1") (pin "49") (pinfunction "EP_49") (pintype "passive"))
      (node (ref "U1_1") (pin "5") (pinfunction "VSSA_PLL_5") (pintype "passive"))
      (node (ref "U1_1") (pin "8") (pinfunction "VSS_PLL_8") (pintype "passive"))
      (node (ref "U1_10") (pin "12") (pinfunction "DVSS_12") (pintype "passive"))
      (node (ref "U1_10") (pin "23") (pinfunction "OVSS1_23") (pintype "passive"))
      (node (ref "U1_10") (pin "27") (pinfunction "DVSS_27") (pintype "passive"))
      (node (ref "U1_10") (pin "38") (pinfunction "OVSS0_38") (pintype "passive"))
      (node (ref "U1_10") (pin "49") (pinfunction "EP_49") (pintype "passive"))
      (node (ref "U1_10") (pin "5") (pinfunction "VSSA_PLL_5") (pintype "passive"))
      (node (ref "U1_10") (pin "8") (pinfunction "VSS_PLL_8") (pintype "passive"))
      (node (ref "U1_11") (pin "12") (pinfunction "DVSS_12") (pintype "passive"))
      (node (ref "U1_11") (pin "23") (pinfunction "OVSS1_23") (pintype "passive"))
      (node (ref "U1_11") (pin "27") (pinfunction "DVSS_27") (pintype "passive"))
      (node (ref "U1_11") (pin "38") (pinfunction "OVSS0_38") (pintype "passive"))
      (node (ref "U1_11") (pin "49") (pinfunction "EP_49") (pintype "passive"))
      (node (ref "U1_11") (pin "5") (pinfunction "VSSA_PLL_5") (pintype "passive"))
      (node (ref "U1_11") (pin "8") (pinfunction "VSS_PLL_8") (pintype "passive"))
      (node (ref "U1_12") (pin "12") (pinfunction "DVSS_12") (pintype "passive"))
      (node (ref "U1_12") (pin "23") (pinfunction "OVSS1_23") (pintype "passive"))
      (node (ref "U1_12") (pin "27") (pinfunction "DVSS_27") (pintype "passive"))
      (node (ref "U1_12") (pin "38") (pinfunction "OVSS0_38") (pintype "passive"))
      (node (ref "U1_12") (pin "49") (pinfunction "EP_49") (pintype "passive"))
      (node (ref "U1_12") (pin "5") (pinfunction "VSSA_PLL_5") (pintype "passive"))
      (node (ref "U1_12") (pin "8") (pinfunction "VSS_PLL_8") (pintype "passive"))
      (node (ref "U1_13") (pin "12") (pinfunction "DVSS_12") (pintype "passive"))
      (node (ref "U1_13") (pin "23") (pinfunction "OVSS1_23") (pintype "passive"))
      (node (ref "U1_13") (pin "27") (pinfunction "DVSS_27") (pintype "passive"))
      (node (ref "U1_13") (pin "38") (pinfunction "OVSS0_38") (pintype "passive"))
      (node (ref "U1_13") (pin "49") (pinfunction "EP_49") (pintype "passive"))
      (node (ref "U1_13") (pin "5") (pinfunction "VSSA_PLL_5") (pintype "passive"))
      (node (ref "U1_13") (pin "8") (pinfunction "VSS_PLL_8") (pintype "passive"))
      (node (ref "U1_14") (pin "12") (pinfunction "DVSS_12") (pintype "passive"))
      (node (ref "U1_14") (pin "23") (pinfunction "OVSS1_23") (pintype "passive"))
      (node (ref "U1_14") (pin "27") (pinfunction "DVSS_27") (pintype "passive"))
      (node (ref "U1_14") (pin "38") (pinfunction "OVSS0_38") (pintype "passive"))
      (node (ref "U1_14") (pin "49") (pinfunction "EP_49") (pintype "passive"))
      (node (ref "U1_14") (pin "5") (pinfunction "VSSA_PLL_5") (pintype "passive"))
      (node (ref "U1_14") (pin "8") (pinfunction "VSS_PLL_8") (pintype "passive"))
      (node (ref "U1_15") (pin "12") (pinfunction "DVSS_12") (pintype "passive"))
      (node (ref "U1_15") (pin "23") (pinfunction "OVSS1_23") (pintype "passive"))
      (node (ref "U1_15") (pin "27") (pinfunction "DVSS_27") (pintype "passive"))
      (node (ref "U1_15") (pin "38") (pinfunction "OVSS0_38") (pintype "passive"))
      (node (ref "U1_15") (pin "49") (pinfunction "EP_49") (pintype "passive"))
      (node (ref "U1_15") (pin "5") (pinfunction "VSSA_PLL_5") (pintype "passive"))
      (node (ref "U1_15") (pin "8") (pinfunction "VSS_PLL_8") (pintype "passive"))
      (node (ref "U1_16") (pin "12") (pinfunction "DVSS_12") (pintype "passive"))
      (node (ref "U1_16") (pin "23") (pinfunction "OVSS1_23") (pintype "passive"))
      (node (ref "U1_16") (pin "27") (pinfunction "DVSS_27") (pintype "passive"))
      (node (ref "U1_16") (pin "38") (pinfunction "OVSS0_38") (pintype "passive"))
      (node (ref "U1_16") (pin "49") (pinfunction "EP_49") (pintype "passive"))
      (node (ref "U1_16") (pin "5") (pinfunction "VSSA_PLL_5") (pintype "passive"))
      (node (ref "U1_16") (pin "8") (pinfunction "VSS_PLL_8") (pintype "passive"))
      (node (ref "U1_2") (pin "12") (pinfunction "DVSS_12") (pintype "passive"))
      (node (ref "U1_2") (pin "23") (pinfunction "OVSS1_23") (pintype "passive"))
      (node (ref "U1_2") (pin "27") (pinfunction "DVSS_27") (pintype "passive"))
      (node (ref "U1_2") (pin "38") (pinfunction "OVSS0_38") (pintype "passive"))
      (node (ref "U1_2") (pin "49") (pinfunction "EP_49") (pintype "passive"))
      (node (ref "U1_2") (pin "5") (pinfunction "VSSA_PLL_5") (pintype "passive"))
      (node (ref "U1_2") (pin "8") (pinfunction "VSS_PLL_8") (pintype "passive"))
      (node (ref "U1_3") (pin "12") (pinfunction "DVSS_12") (pintype "passive"))
      (node (ref "U1_3") (pin "23") (pinfunction "OVSS1_23") (pintype "passive"))
      (node (ref "U1_3") (pin "27") (pinfunction "DVSS_27") (pintype "passive"))
      (node (ref "U1_3") (pin "38") (pinfunction "OVSS0_38") (pintype "passive"))
      (node (ref "U1_3") (pin "49") (pinfunction "EP_49") (pintype "passive"))
      (node (ref "U1_3") (pin "5") (pinfunction "VSSA_PLL_5") (pintype "passive"))
      (node (ref "U1_3") (pin "8") (pinfunction "VSS_PLL_8") (pintype "passive"))
      (node (ref "U1_4") (pin "12") (pinfunction "DVSS_12") (pintype "passive"))
      (node (ref "U1_4") (pin "23") (pinfunction "OVSS1_23") (pintype "passive"))
      (node (ref "U1_4") (pin "27") (pinfunction "DVSS_27") (pintype "passive"))
      (node (ref "U1_4") (pin "38") (pinfunction "OVSS0_38") (pintype "passive"))
      (node (ref "U1_4") (pin "49") (pinfunction "EP_49") (pintype "passive"))
      (node (ref "U1_4") (pin "5") (pinfunction "VSSA_PLL_5") (pintype "passive"))
      (node (ref "U1_4") (pin "8") (pinfunction "VSS_PLL_8") (pintype "passive"))
      (node (ref "U1_5") (pin "12") (pinfunction "DVSS_12") (pintype "passive"))
      (node (ref "U1_5") (pin "23") (pinfunction "OVSS1_23") (pintype "passive"))
      (node (ref "U1_5") (pin "27") (pinfunction "DVSS_27") (pintype "passive"))
      (node (ref "U1_5") (pin "38") (pinfunction "OVSS0_38") (pintype "passive"))
      (node (ref "U1_5") (pin "49") (pinfunction "EP_49") (pintype "passive"))
      (node (ref "U1_5") (pin "5") (pinfunction "VSSA_PLL_5") (pintype "passive"))
      (node (ref "U1_5") (pin "8") (pinfunction "VSS_PLL_8") (pintype "passive"))
      (node (ref "U1_6") (pin "12") (pinfunction "DVSS_12") (pintype "passive"))
      (node (ref "U1_6") (pin "23") (pinfunction "OVSS1_23") (pintype "passive"))
      (node (ref "U1_6") (pin "27") (pinfunction "DVSS_27") (pintype "passive"))
      (node (ref "U1_6") (pin "38") (pinfunction "OVSS0_38") (pintype "passive"))
      (node (ref "U1_6") (pin "49") (pinfunction "EP_49") (pintype "passive"))
      (node (ref "U1_6") (pin "5") (pinfunction "VSSA_PLL_5") (pintype "passive"))
      (node (ref "U1_6") (pin "8") (pinfunction "VSS_PLL_8") (pintype "passive"))
      (node (ref "U1_7") (pin "12") (pinfunction "DVSS_12") (pintype "passive"))
      (node (ref "U1_7") (pin "23") (pinfunction "OVSS1_23") (pintype "passive"))
      (node (ref "U1_7") (pin "27") (pinfunction "DVSS_27") (pintype "passive"))
      (node (ref "U1_7") (pin "38") (pinfunction "OVSS0_38") (pintype "passive"))
      (node (ref "U1_7") (pin "49") (pinfunction "EP_49") (pintype "passive"))
      (node (ref "U1_7") (pin "5") (pinfunction "VSSA_PLL_5") (pintype "passive"))
      (node (ref "U1_7") (pin "8") (pinfunction "VSS_PLL_8") (pintype "passive"))
      (node (ref "U1_8") (pin "12") (pinfunction "DVSS_12") (pintype "passive"))
      (node (ref "U1_8") (pin "23") (pinfunction "OVSS1_23") (pintype "passive"))
      (node (ref "U1_8") (pin "27") (pinfunction "DVSS_27") (pintype "passive"))
      (node (ref "U1_8") (pin "38") (pinfunction "OVSS0_38") (pintype "passive"))
      (node (ref "U1_8") (pin "49") (pinfunction "EP_49") (pintype "passive"))
      (node (ref "U1_8") (pin "5") (pinfunction "VSSA_PLL_5") (pintype "passive"))
      (node (ref "U1_8") (pin "8") (pinfunction "VSS_PLL_8") (pintype "passive"))
      (node (ref "U1_9") (pin "12") (pinfunction "DVSS_12") (pintype "passive"))
      (node (ref "U1_9") (pin "23") (pinfunction "OVSS1_23") (pintype "passive"))
      (node (ref "U1_9") (pin "27") (pinfunction "DVSS_27") (pintype "passive"))
      (node (ref "U1_9") (pin "38") (pinfunction "OVSS0_38") (pintype "passive"))
      (node (ref "U1_9") (pin "49") (pinfunction "EP_49") (pintype "passive"))
      (node (ref "U1_9") (pin "5") (pinfunction "VSSA_PLL_5") (pintype "passive"))
      (node (ref "U1_9") (pin "8") (pinfunction "VSS_PLL_8") (pintype "passive"))
      (node (ref "U2") (pin "2") (pinfunction "1A_2") (pintype "passive"))
      (node (ref "U2") (pin "3") (pinfunction "GND_3") (pintype "passive"))
      (node (ref "U25") (pin "4") (pinfunction "GND_4") (pintype "passive"))
      (node (ref "U25") (pin "9") (pinfunction "EP_9") (pintype "passive"))
      (node (ref "U3") (pin "3") (pinfunction "1B_3") (pintype "passive"))
      (node (ref "U3") (pin "7") (pinfunction "GND_7") (pintype "passive"))
      (node (ref "U30") (pin "4") (pinfunction "GND_4") (pintype "passive"))
      (node (ref "U30") (pin "9") (pinfunction "EP_9") (pintype "passive"))
      (node (ref "U6") (pin "2") (pinfunction "GND_2") (pintype "passive"))
    )
    (net (code "128") (name "Net-(C209-Pad1)") (class "Default")
      (node (ref "C209") (pin "1") (pinfunction "1_1") (pintype "passive"))
      (node (ref "R36") (pin "1") (pinfunction "1_1") (pintype "passive"))
      (node (ref "R37") (pin "2") (pinfunction "2_2") (pintype "passive"))
    )
    (net (code "129") (name "unconnected-(J3-Pad4)") (class "Default")
      (node (ref "J3") (pin "4") (pinfunction "4_4") (pintype "passive"))
    )
    (net (code "130") (name "unconnected-(U1-AN4{slash}C1IN2-{slash}USBOEN{slash}RPI36{slash}RB4-Pad12)") (class "Default")
      (node (ref "U1") (pin "12") (pinfunction "AN4/C1IN2-/USBOEN/RPI36/RB4_12") (pintype "passive"))
    )
    (net (code "131") (name "unconnected-(U1-AN5{slash}C1IN1+{slash}VBUSON{slash}VBUSST{slash}RPI37{slash}RB5-Pad11)") (class "Default")
      (node (ref "U1") (pin "11") (pinfunction "AN5/C1IN1+/VBUSON/VBUSST/RPI37/RB5_11") (pintype "passive"))
    )
    (net (code "132") (name "unconnected-(U1-AN8{slash}PMA6{slash}RPI40{slash}RB8-Pad21)") (class "Default")
      (node (ref "U1") (pin "21") (pinfunction "AN8/PMA6/RPI40/RB8_21") (pintype "passive"))
    )
    (net (code "133") (name "unconnected-(U1-AN9{slash}PMA7{slash}{slash}RPI41{slash}RB9-Pad22)") (class "Default")
      (node (ref "U1") (pin "22") (pinfunction "AN9/PMA7//RPI41/RB9_22") (pintype "passive"))
    )
    (net (code "134") (name "unconnected-(U1-C1IN1-{slash}SDI2{slash}PMA4{slash}RPI119{slash}RG7-Pad5)") (class "Default")
      (node (ref "U1") (pin "5") (pinfunction "C1IN1-/SDI2/PMA4/RPI119/RG7_5") (pintype "passive"))
    )
    (net (code "135") (name "unconnected-(U1-C1IN3-{slash}SCK2{slash}PMA5{slash}RP118{slash}RG6-Pad4)") (class "Default")
      (node (ref "U1") (pin "4") (pinfunction "C1IN3-/SCK2/PMA5/RP118/RG6_4") (pintype "passive"))
    )
    (net (code "136") (name "unconnected-(U1-C2IN1-{slash}PMA2{slash}RPI121{slash}RG9-Pad8)") (class "Default")
      (node (ref "U1") (pin "8") (pinfunction "C2IN1-/PMA2/RPI121/RG9_8") (pintype "passive"))
    )
    (net (code "137") (name "unconnected-(U1-C2IN3-{slash}SDO2{slash}PMA3{slash}RP120{slash}RG8-Pad6)") (class "Default")
      (node (ref "U1") (pin "6") (pinfunction "C2IN3-/SDO2/PMA3/RP120/RG8_6") (pintype "passive"))
    )
    (net (code "138") (name "unconnected-(U1-TDO{slash}AN11{slash}PMA12{slash}RPI43{slash}RB11-Pad24)") (class "Default")
      (node (ref "U1") (pin "24") (pinfunction "TDO/AN11/PMA12/RPI43/RB11_24") (pintype "passive"))
    )
    (net (code "139") (name "unconnected-(U1-TMS{slash}AN10{slash}CVREF{slash}PMA13{slash}RPI42{slash}RB10-Pad23)") (class "Default")
      (node (ref "U1") (pin "23") (pinfunction "TMS/AN10/CVREF/PMA13/RPI42/RB10_23") (pintype "passive"))
    )
    (net (code "140") (name "unconnected-(U1-USBID{slash}RP99{slash}RF3-Pad33)") (class "Default")
      (node (ref "U1") (pin "33") (pinfunction "USBID/RP99/RF3_33") (pintype "passive"))
    )
    (net (code "141") (name "unconnected-(U3-2A-Pad5)") (class "Default")
      (node (ref "U3") (pin "5") (pinfunction "2A_5") (pintype "passive"))
    )
    (net (code "142") (name "unconnected-(U3-2B-Pad6)") (class "Default")
      (node (ref "U3") (pin "6") (pinfunction "2B_6") (pintype "passive"))
    )
    (net (code "143") (name "unconnected-(U3-2Y-Pad4)") (class "Default")
      (node (ref "U3") (pin "4") (pinfunction "2Y_4") (pintype "passive"))
    )
    (net (code "144") (name "unconnected-(U3-3A-Pad8)") (class "Default")
      (node (ref "U3") (pin "8") (pinfunction "3A_8") (pintype "passive"))
    )
    (net (code "145") (name "unconnected-(U3-3B-Pad9)") (class "Default")
      (node (ref "U3") (pin "9") (pinfunction "3B_9") (pintype "passive"))
    )
    (net (code "146") (name "unconnected-(U3-3Y-Pad10)") (class "Default")
      (node (ref "U3") (pin "10") (pinfunction "3Y_10") (pintype "passive"))
    )
    (net (code "147") (name "unconnected-(U3-4A-Pad11)") (class "Default")
      (node (ref "U3") (pin "11") (pinfunction "4A_11") (pintype "passive"))
    )
    (net (code "148") (name "unconnected-(U3-4B-Pad12)") (class "Default")
      (node (ref "U3") (pin "12") (pinfunction "4B_12") (pintype "passive"))
    )
    (net (code "149") (name "unconnected-(U3-4Y-Pad13)") (class "Default")
      (node (ref "U3") (pin "13") (pinfunction "4Y_13") (pintype "passive"))
    )
    (net (code "150") (name "unconnected-(U6-NC-Pad4)") (class "Default")
      (node (ref "U6") (pin "4") (pinfunction "NC_4") (pintype "passive"))
    )
    (net (code "151") (name "unconnected-(U19-GND-Pad2)") (class "Default")
      (node (ref "U19") (pin "2") (pinfunction "GND_2") (pintype "passive"))
    )
    (net (code "152") (name "unconnected-(U19-GND-Pad3)") (class "Default")
      (node (ref "U19") (pin "3") (pinfunction "GND_3") (pintype "passive"))
    )
    (net (code "153") (name "unconnected-(U19-N.C.-Pad4)") (class "Default")
      (node (ref "U19") (pin "4") (pinfunction "N.C._4") (pintype "passive"))
    )
  )
)
